# quark_foc_driver.net
KiCad netlist of a schematic drawn in Altium Designer
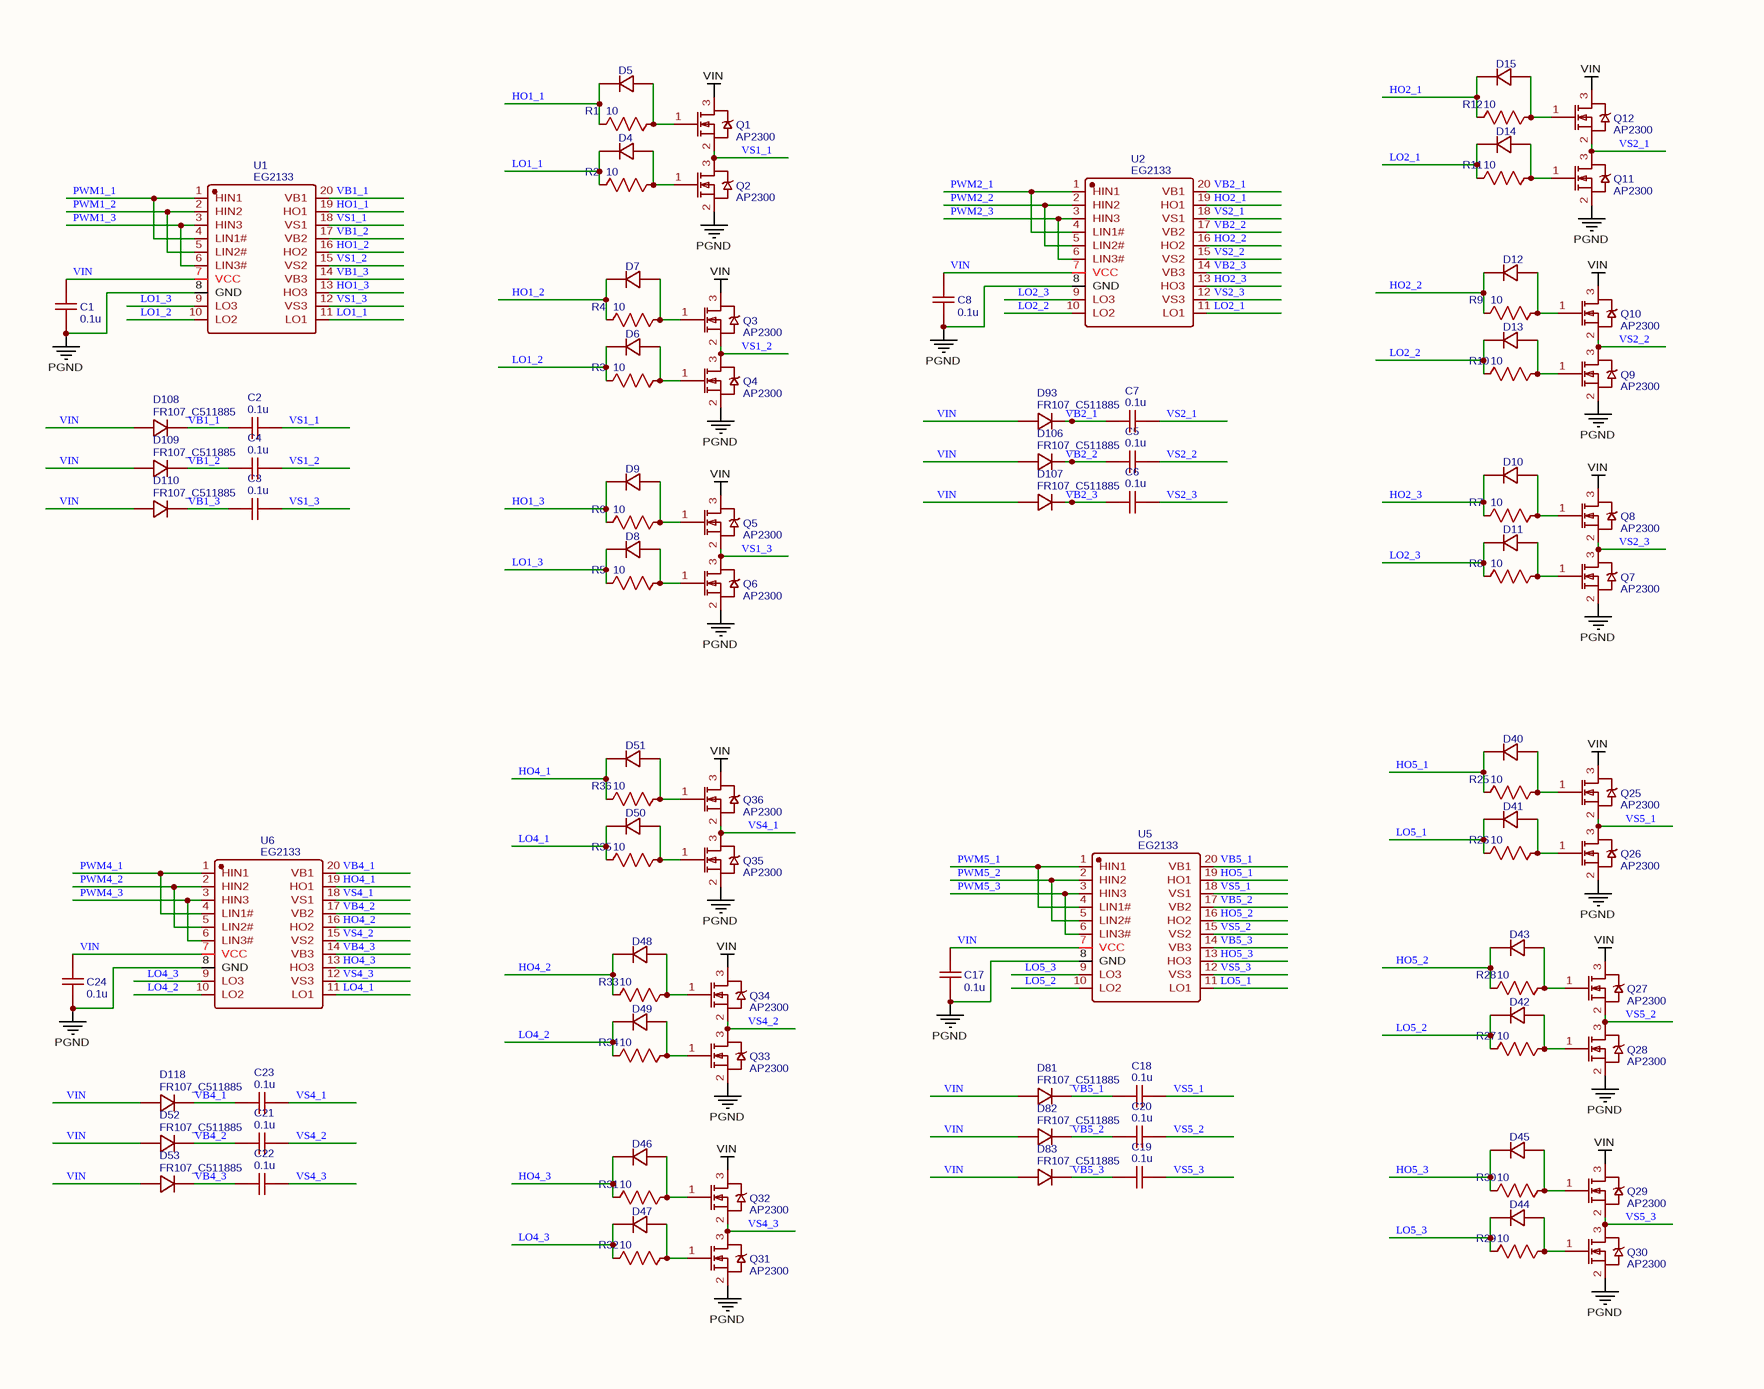
[diagram p0: quark_foc_driver.schdoc, top left]
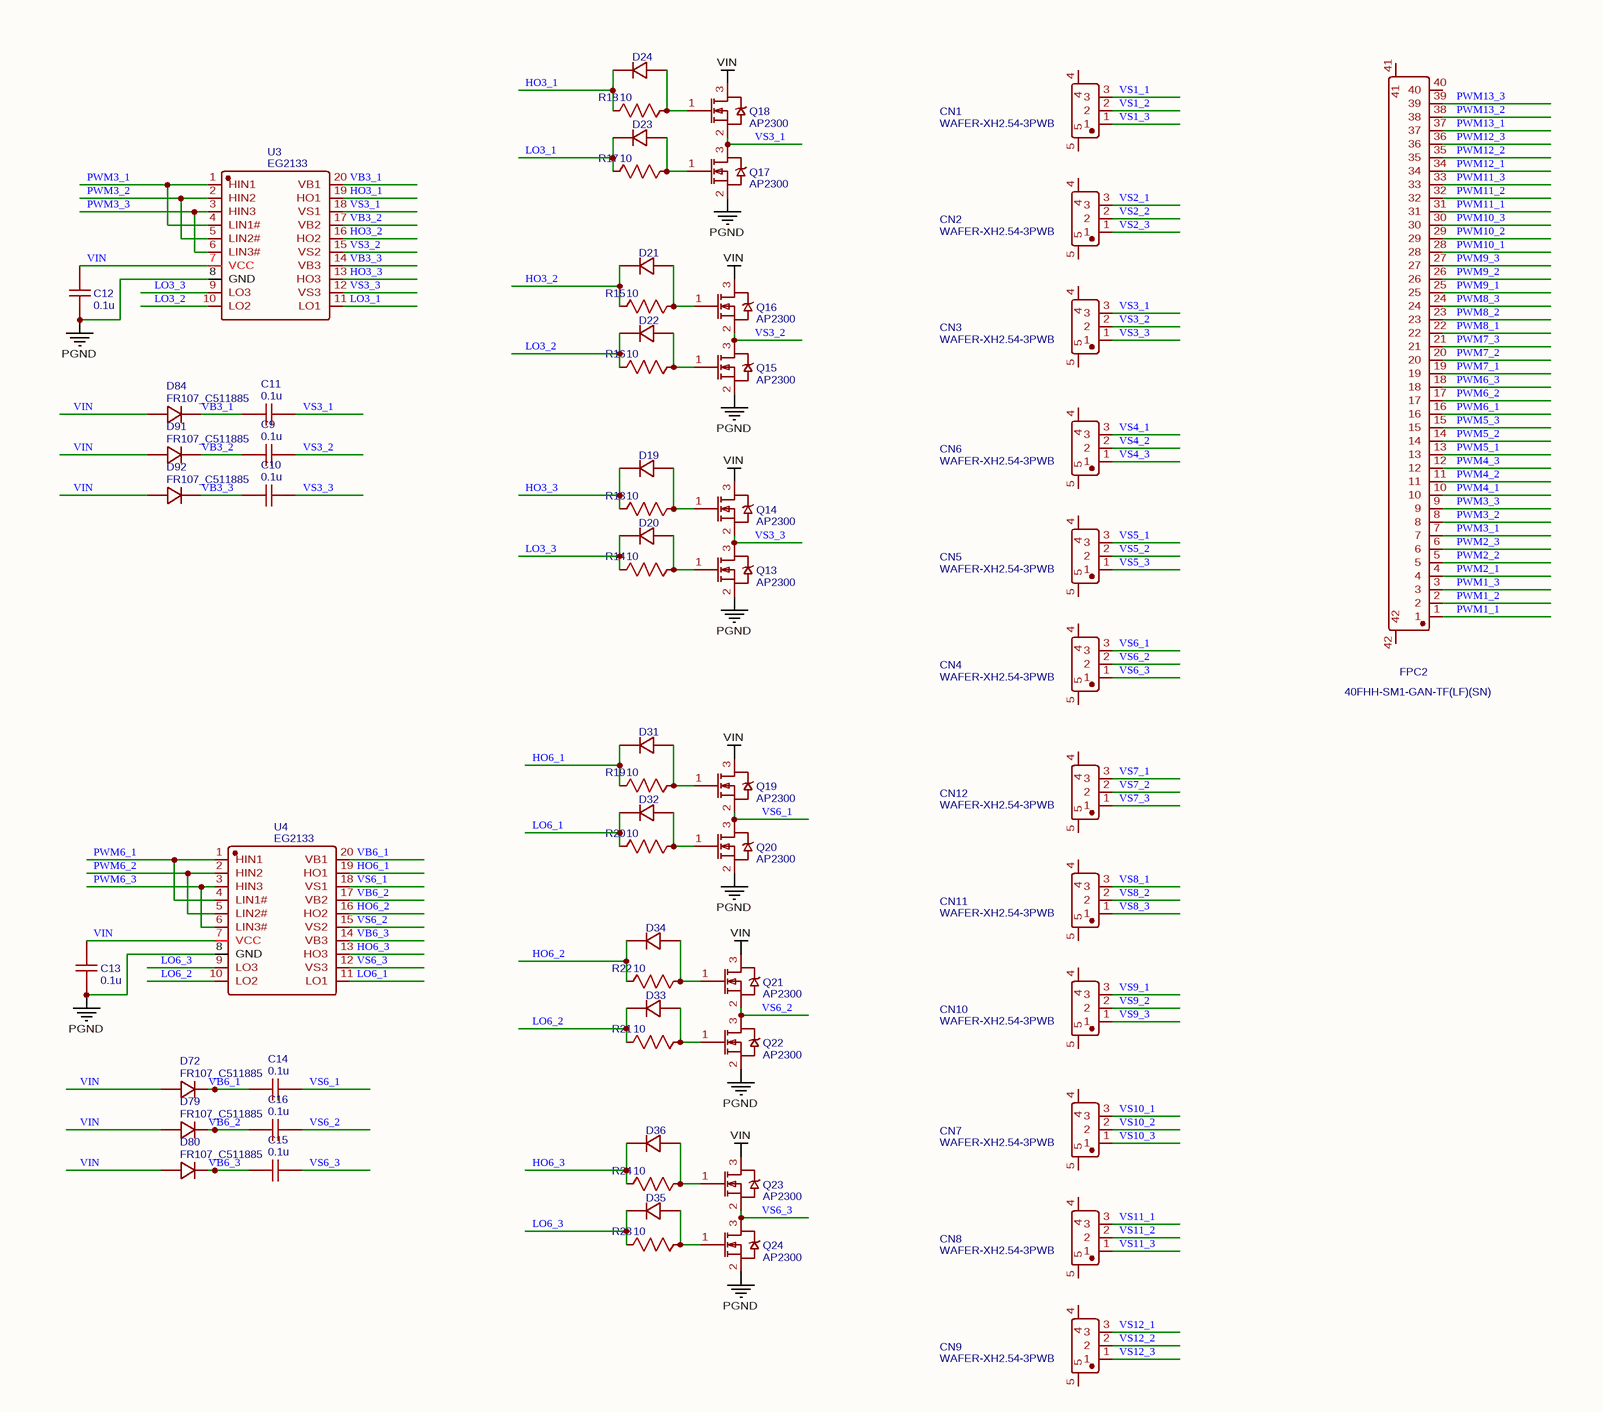
[diagram p1: quark_foc_driver.schdoc, top right]
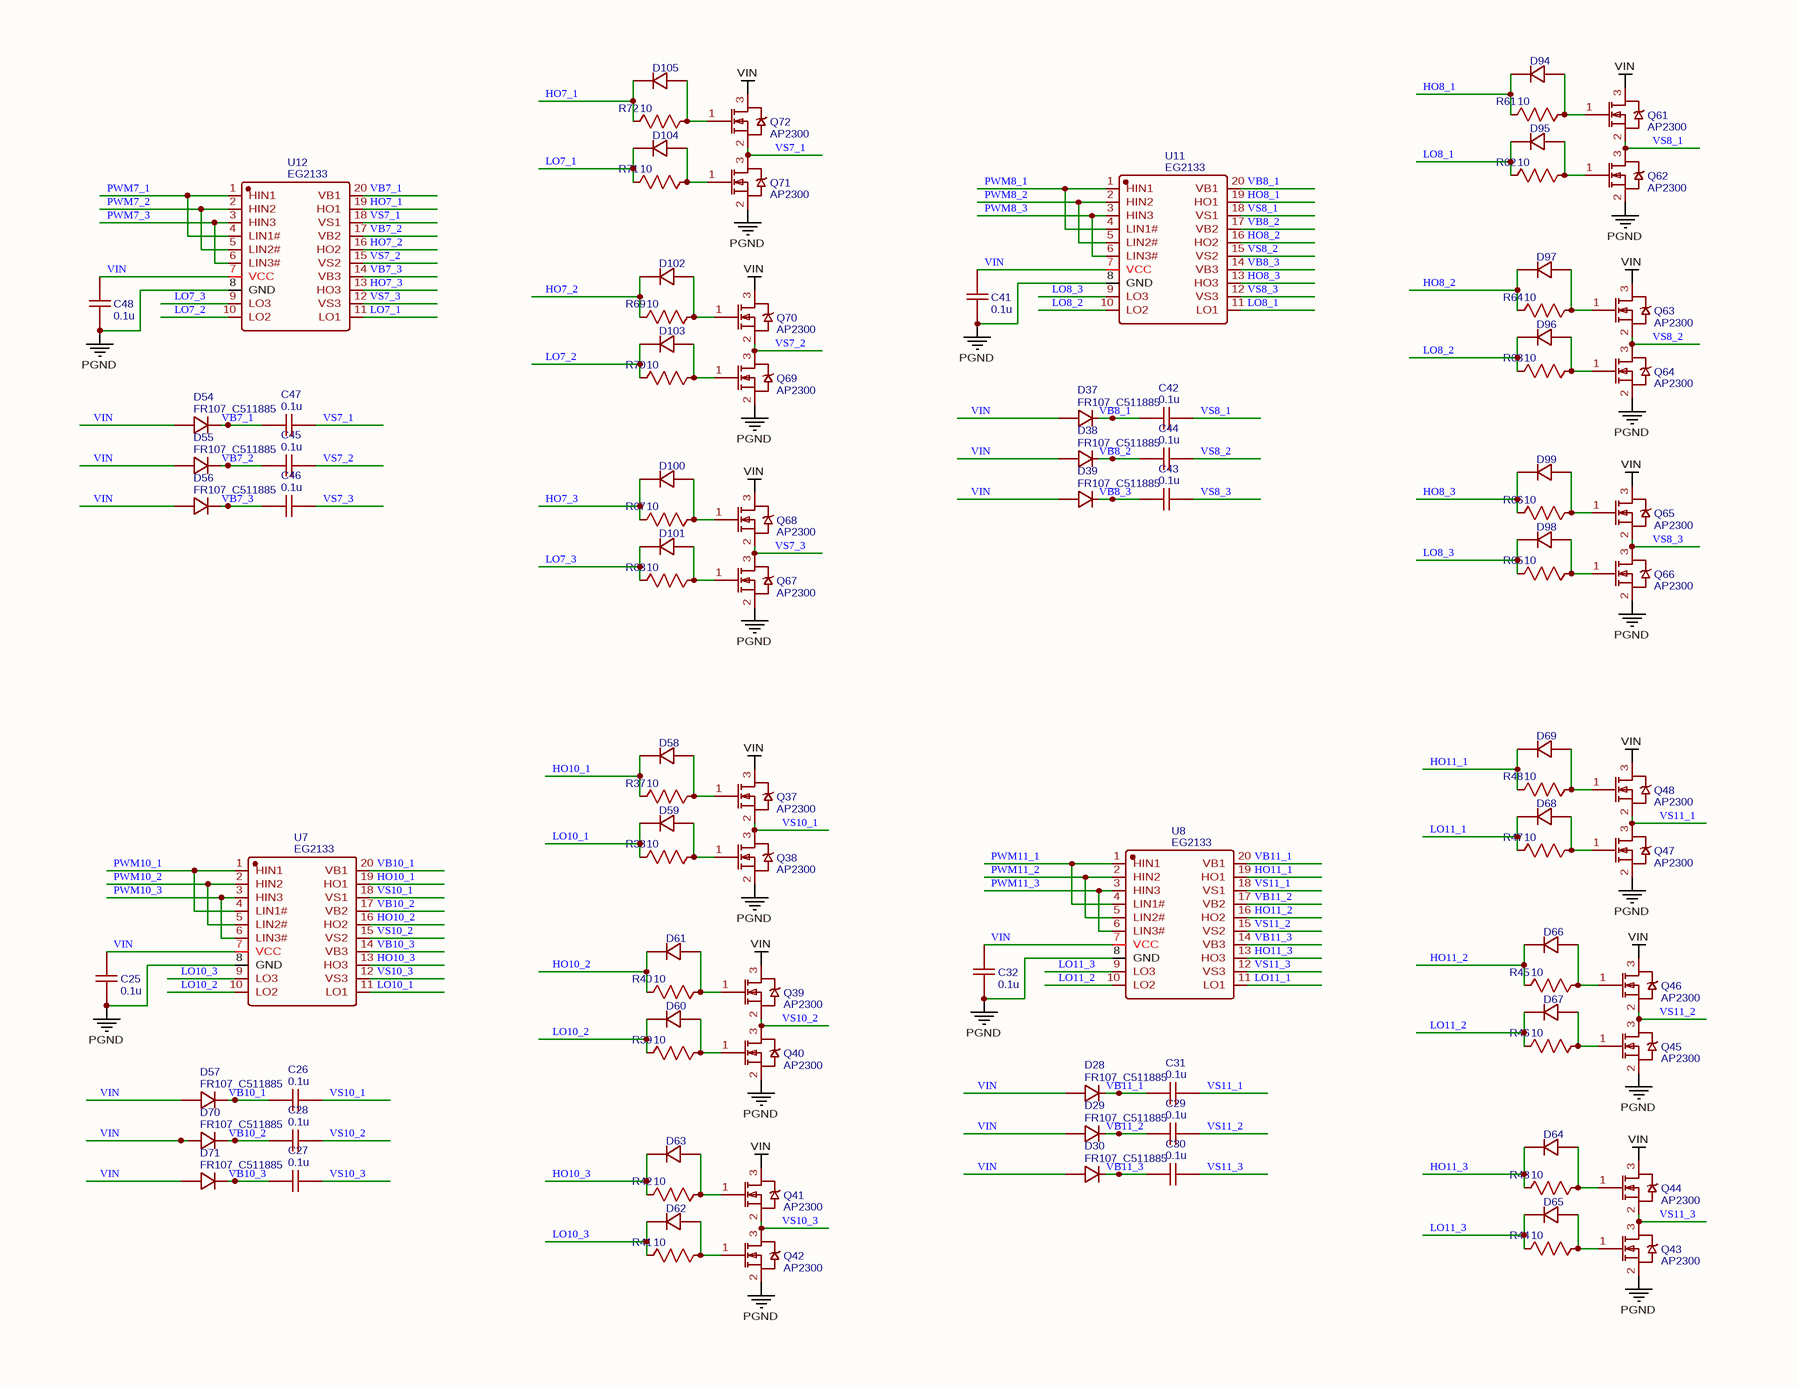
[diagram p2: quark_foc_driver.schdoc, bottom left]
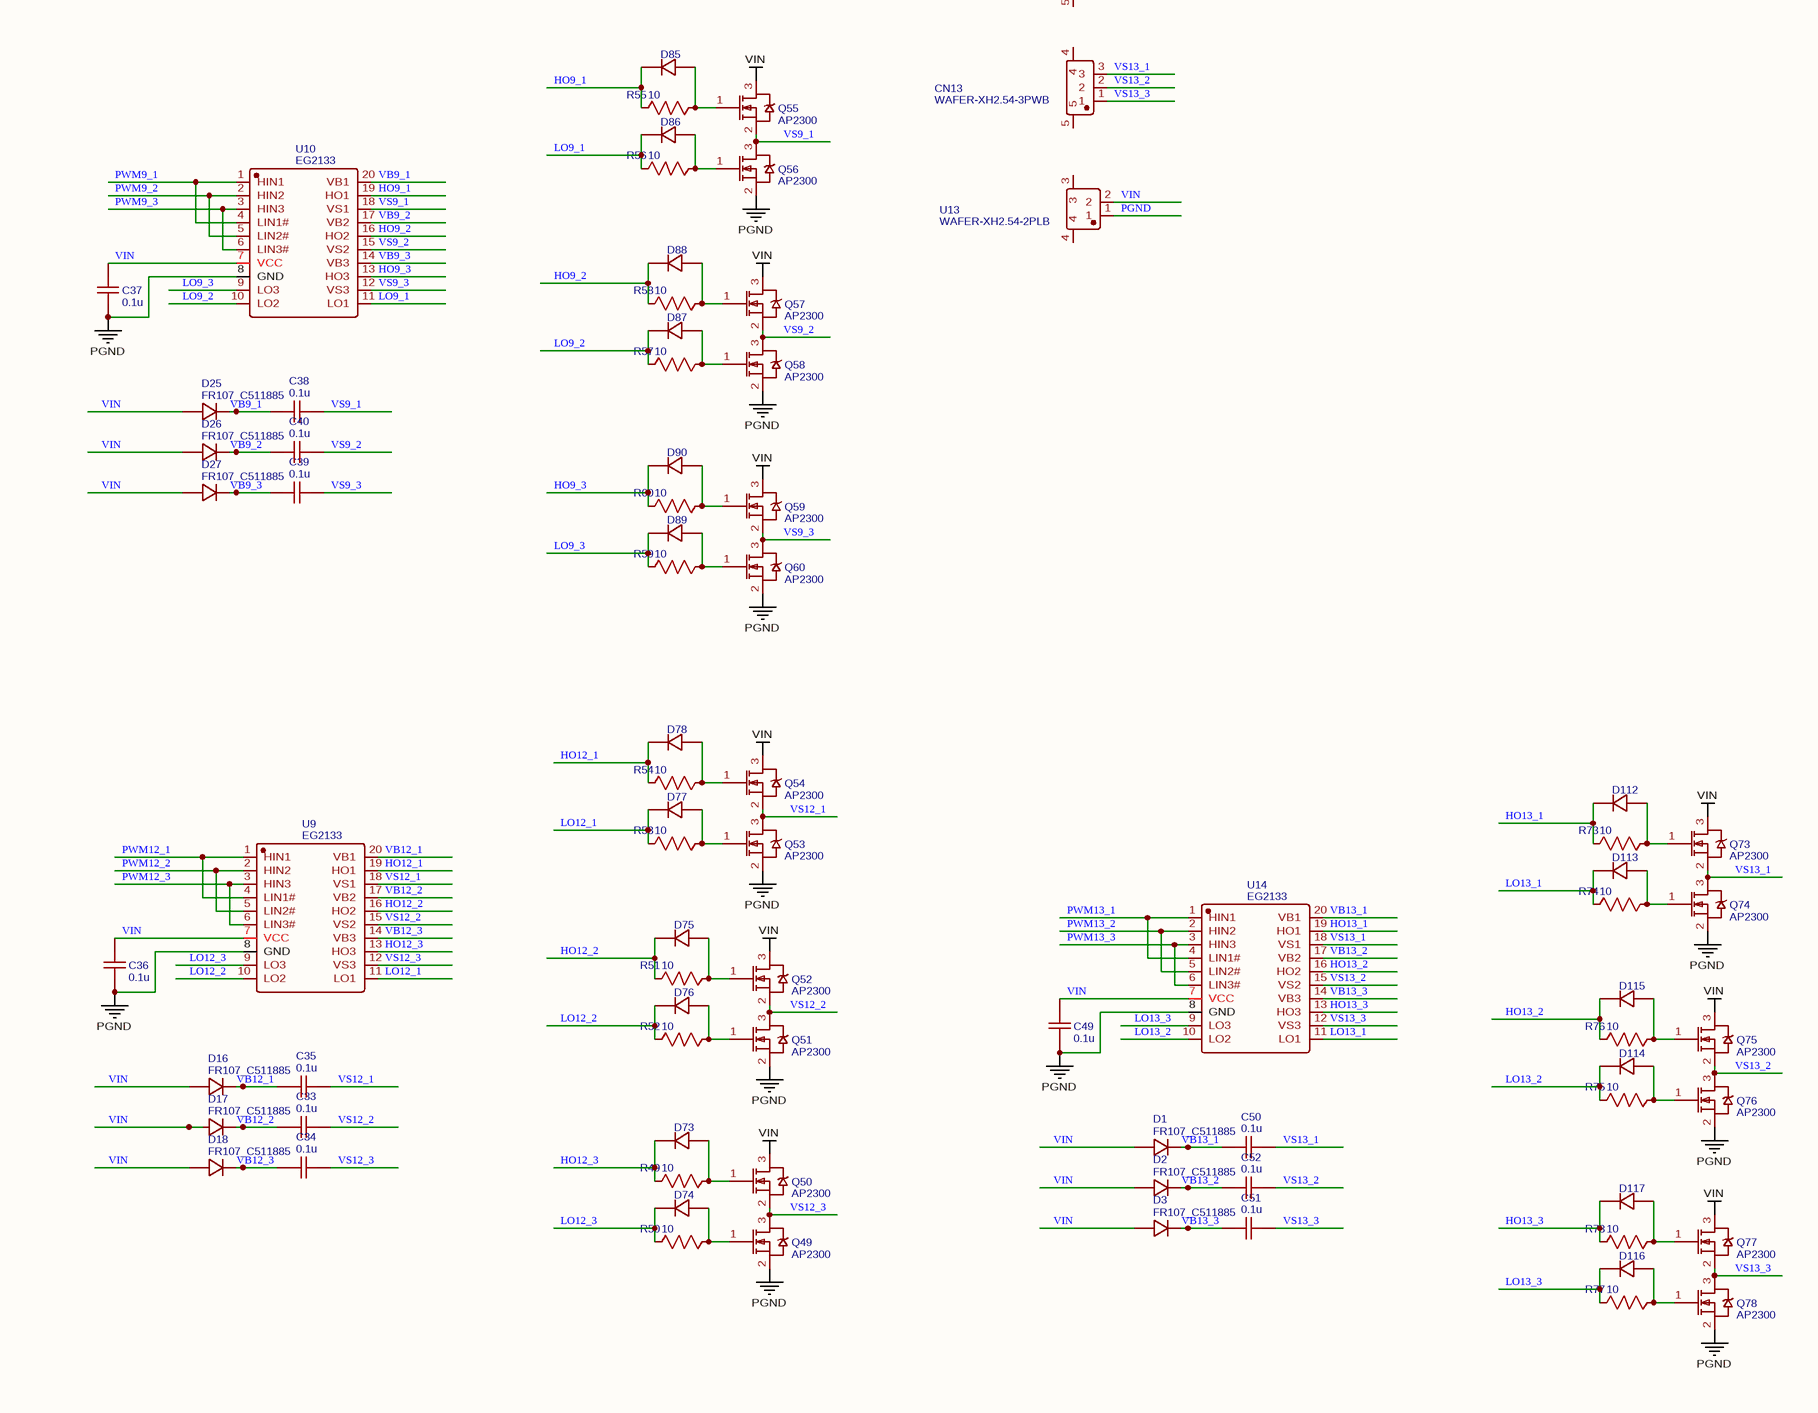
[diagram p3: quark_foc_driver.schdoc, bottom right]

(export (version "E")
  (design (tool "Eeschema 10.0.6"))
  (components
    (comp (ref "C1")
      (value "0.1u")
      (footprint "C0603")
      (fields (field (name "CONTRIBUTOR") "LCEDA_Lib"))
      (libsource (lib "altium-import") (part "root_1_0.1u_"))
    )
    (comp (ref "C2")
      (value "0.1u")
      (footprint "C0603")
      (fields (field (name "CONTRIBUTOR") "LCEDA_Lib"))
      (libsource (lib "altium-import") (part "root_0_0.1u_"))
    )
    (comp (ref "C3")
      (value "0.1u")
      (footprint "C0603")
      (fields (field (name "CONTRIBUTOR") "LCEDA_Lib"))
      (libsource (lib "altium-import") (part "root_0_0.1u_"))
    )
    (comp (ref "C4")
      (value "0.1u")
      (footprint "C0603")
      (fields (field (name "CONTRIBUTOR") "LCEDA_Lib"))
      (libsource (lib "altium-import") (part "root_2_0.1u_"))
    )
    (comp (ref "C5")
      (value "0.1u")
      (footprint "C0603")
      (fields (field (name "CONTRIBUTOR") "LCEDA_Lib"))
      (libsource (lib "altium-import") (part "root_2_0.1u_"))
    )
    (comp (ref "C6")
      (value "0.1u")
      (footprint "C0603")
      (fields (field (name "CONTRIBUTOR") "LCEDA_Lib"))
      (libsource (lib "altium-import") (part "root_0_0.1u_"))
    )
    (comp (ref "C7")
      (value "0.1u")
      (footprint "C0603")
      (fields (field (name "CONTRIBUTOR") "LCEDA_Lib"))
      (libsource (lib "altium-import") (part "root_0_0.1u_"))
    )
    (comp (ref "C8")
      (value "0.1u")
      (footprint "C0603")
      (fields (field (name "CONTRIBUTOR") "LCEDA_Lib"))
      (libsource (lib "altium-import") (part "root_1_0.1u_"))
    )
    (comp (ref "C9")
      (value "0.1u")
      (footprint "C0603")
      (fields (field (name "CONTRIBUTOR") "LCEDA_Lib"))
      (libsource (lib "altium-import") (part "root_2_0.1u_"))
    )
    (comp (ref "C10")
      (value "0.1u")
      (footprint "C0603")
      (fields (field (name "CONTRIBUTOR") "LCEDA_Lib"))
      (libsource (lib "altium-import") (part "root_0_0.1u_"))
    )
    (comp (ref "C11")
      (value "0.1u")
      (footprint "C0603")
      (fields (field (name "CONTRIBUTOR") "LCEDA_Lib"))
      (libsource (lib "altium-import") (part "root_0_0.1u_"))
    )
    (comp (ref "C12")
      (value "0.1u")
      (footprint "C0603")
      (fields (field (name "CONTRIBUTOR") "LCEDA_Lib"))
      (libsource (lib "altium-import") (part "root_1_0.1u_"))
    )
    (comp (ref "C13")
      (value "0.1u")
      (footprint "C0603")
      (fields (field (name "CONTRIBUTOR") "LCEDA_Lib"))
      (libsource (lib "altium-import") (part "root_1_0.1u_"))
    )
    (comp (ref "C14")
      (value "0.1u")
      (footprint "C0603")
      (fields (field (name "CONTRIBUTOR") "LCEDA_Lib"))
      (libsource (lib "altium-import") (part "root_0_0.1u_"))
    )
    (comp (ref "C15")
      (value "0.1u")
      (footprint "C0603")
      (fields (field (name "CONTRIBUTOR") "LCEDA_Lib"))
      (libsource (lib "altium-import") (part "root_0_0.1u_"))
    )
    (comp (ref "C16")
      (value "0.1u")
      (footprint "C0603")
      (fields (field (name "CONTRIBUTOR") "LCEDA_Lib"))
      (libsource (lib "altium-import") (part "root_2_0.1u_"))
    )
    (comp (ref "C17")
      (value "0.1u")
      (footprint "C0603")
      (fields (field (name "CONTRIBUTOR") "LCEDA_Lib"))
      (libsource (lib "altium-import") (part "root_1_0.1u_"))
    )
    (comp (ref "C18")
      (value "0.1u")
      (footprint "C0603")
      (fields (field (name "CONTRIBUTOR") "LCEDA_Lib"))
      (libsource (lib "altium-import") (part "root_0_0.1u_"))
    )
    (comp (ref "C19")
      (value "0.1u")
      (footprint "C0603")
      (fields (field (name "CONTRIBUTOR") "LCEDA_Lib"))
      (libsource (lib "altium-import") (part "root_0_0.1u_"))
    )
    (comp (ref "C20")
      (value "0.1u")
      (footprint "C0603")
      (fields (field (name "CONTRIBUTOR") "LCEDA_Lib"))
      (libsource (lib "altium-import") (part "root_2_0.1u_"))
    )
    (comp (ref "C21")
      (value "0.1u")
      (footprint "C0603")
      (fields (field (name "CONTRIBUTOR") "LCEDA_Lib"))
      (libsource (lib "altium-import") (part "root_2_0.1u_"))
    )
    (comp (ref "C22")
      (value "0.1u")
      (footprint "C0603")
      (fields (field (name "CONTRIBUTOR") "LCEDA_Lib"))
      (libsource (lib "altium-import") (part "root_0_0.1u_"))
    )
    (comp (ref "C23")
      (value "0.1u")
      (footprint "C0603")
      (fields (field (name "CONTRIBUTOR") "LCEDA_Lib"))
      (libsource (lib "altium-import") (part "root_0_0.1u_"))
    )
    (comp (ref "C24")
      (value "0.1u")
      (footprint "C0603")
      (fields (field (name "CONTRIBUTOR") "LCEDA_Lib"))
      (libsource (lib "altium-import") (part "root_1_0.1u_"))
    )
    (comp (ref "C25")
      (value "0.1u")
      (footprint "C0603")
      (fields (field (name "CONTRIBUTOR") "LCEDA_Lib"))
      (libsource (lib "altium-import") (part "root_1_0.1u_"))
    )
    (comp (ref "C26")
      (value "0.1u")
      (footprint "C0603")
      (fields (field (name "CONTRIBUTOR") "LCEDA_Lib"))
      (libsource (lib "altium-import") (part "root_0_0.1u_"))
    )
    (comp (ref "C27")
      (value "0.1u")
      (footprint "C0603")
      (fields (field (name "CONTRIBUTOR") "LCEDA_Lib"))
      (libsource (lib "altium-import") (part "root_0_0.1u_"))
    )
    (comp (ref "C28")
      (value "0.1u")
      (footprint "C0603")
      (fields (field (name "CONTRIBUTOR") "LCEDA_Lib"))
      (libsource (lib "altium-import") (part "root_2_0.1u_"))
    )
    (comp (ref "C29")
      (value "0.1u")
      (footprint "C0603")
      (fields (field (name "CONTRIBUTOR") "LCEDA_Lib"))
      (libsource (lib "altium-import") (part "root_2_0.1u_"))
    )
    (comp (ref "C30")
      (value "0.1u")
      (footprint "C0603")
      (fields (field (name "CONTRIBUTOR") "LCEDA_Lib"))
      (libsource (lib "altium-import") (part "root_0_0.1u_"))
    )
    (comp (ref "C31")
      (value "0.1u")
      (footprint "C0603")
      (fields (field (name "CONTRIBUTOR") "LCEDA_Lib"))
      (libsource (lib "altium-import") (part "root_0_0.1u_"))
    )
    (comp (ref "C32")
      (value "0.1u")
      (footprint "C0603")
      (fields (field (name "CONTRIBUTOR") "LCEDA_Lib"))
      (libsource (lib "altium-import") (part "root_1_0.1u_"))
    )
    (comp (ref "C33")
      (value "0.1u")
      (footprint "C0603")
      (fields (field (name "CONTRIBUTOR") "LCEDA_Lib"))
      (libsource (lib "altium-import") (part "root_2_0.1u_"))
    )
    (comp (ref "C34")
      (value "0.1u")
      (footprint "C0603")
      (fields (field (name "CONTRIBUTOR") "LCEDA_Lib"))
      (libsource (lib "altium-import") (part "root_0_0.1u_"))
    )
    (comp (ref "C35")
      (value "0.1u")
      (footprint "C0603")
      (fields (field (name "CONTRIBUTOR") "LCEDA_Lib"))
      (libsource (lib "altium-import") (part "root_0_0.1u_"))
    )
    (comp (ref "C36")
      (value "0.1u")
      (footprint "C0603")
      (fields (field (name "CONTRIBUTOR") "LCEDA_Lib"))
      (libsource (lib "altium-import") (part "root_1_0.1u_"))
    )
    (comp (ref "C37")
      (value "0.1u")
      (footprint "C0603")
      (fields (field (name "CONTRIBUTOR") "LCEDA_Lib"))
      (libsource (lib "altium-import") (part "root_1_0.1u_"))
    )
    (comp (ref "C38")
      (value "0.1u")
      (footprint "C0603")
      (fields (field (name "CONTRIBUTOR") "LCEDA_Lib"))
      (libsource (lib "altium-import") (part "root_0_0.1u_"))
    )
    (comp (ref "C39")
      (value "0.1u")
      (footprint "C0603")
      (fields (field (name "CONTRIBUTOR") "LCEDA_Lib"))
      (libsource (lib "altium-import") (part "root_0_0.1u_"))
    )
    (comp (ref "C40")
      (value "0.1u")
      (footprint "C0603")
      (fields (field (name "CONTRIBUTOR") "LCEDA_Lib"))
      (libsource (lib "altium-import") (part "root_2_0.1u_"))
    )
    (comp (ref "C41")
      (value "0.1u")
      (footprint "C0603")
      (fields (field (name "CONTRIBUTOR") "LCEDA_Lib"))
      (libsource (lib "altium-import") (part "root_1_0.1u_"))
    )
    (comp (ref "C42")
      (value "0.1u")
      (footprint "C0603")
      (fields (field (name "CONTRIBUTOR") "LCEDA_Lib"))
      (libsource (lib "altium-import") (part "root_0_0.1u_"))
    )
    (comp (ref "C43")
      (value "0.1u")
      (footprint "C0603")
      (fields (field (name "CONTRIBUTOR") "LCEDA_Lib"))
      (libsource (lib "altium-import") (part "root_0_0.1u_"))
    )
    (comp (ref "C44")
      (value "0.1u")
      (footprint "C0603")
      (fields (field (name "CONTRIBUTOR") "LCEDA_Lib"))
      (libsource (lib "altium-import") (part "root_2_0.1u_"))
    )
    (comp (ref "C45")
      (value "0.1u")
      (footprint "C0603")
      (fields (field (name "CONTRIBUTOR") "LCEDA_Lib"))
      (libsource (lib "altium-import") (part "root_2_0.1u_"))
    )
    (comp (ref "C46")
      (value "0.1u")
      (footprint "C0603")
      (fields (field (name "CONTRIBUTOR") "LCEDA_Lib"))
      (libsource (lib "altium-import") (part "root_0_0.1u_"))
    )
    (comp (ref "C47")
      (value "0.1u")
      (footprint "C0603")
      (fields (field (name "CONTRIBUTOR") "LCEDA_Lib"))
      (libsource (lib "altium-import") (part "root_0_0.1u_"))
    )
    (comp (ref "C48")
      (value "0.1u")
      (footprint "C0603")
      (fields (field (name "CONTRIBUTOR") "LCEDA_Lib"))
      (libsource (lib "altium-import") (part "root_1_0.1u_"))
    )
    (comp (ref "C49")
      (value "0.1u")
      (footprint "C0603")
      (fields (field (name "CONTRIBUTOR") "LCEDA_Lib"))
      (libsource (lib "altium-import") (part "root_1_0.1u_"))
    )
    (comp (ref "C50")
      (value "0.1u")
      (footprint "C0603")
      (fields (field (name "CONTRIBUTOR") "LCEDA_Lib"))
      (libsource (lib "altium-import") (part "root_0_0.1u_"))
    )
    (comp (ref "C51")
      (value "0.1u")
      (footprint "C0603")
      (fields (field (name "CONTRIBUTOR") "LCEDA_Lib"))
      (libsource (lib "altium-import") (part "root_0_0.1u_"))
    )
    (comp (ref "C52")
      (value "0.1u")
      (footprint "C0603")
      (fields (field (name "CONTRIBUTOR") "LCEDA_Lib"))
      (libsource (lib "altium-import") (part "root_2_0.1u_"))
    )
    (comp (ref "CN1")
      (value "WAFER-XH2.54-3PWB")
      (footprint "CONN-SMD_3P-P2.50_XUNPU_WAFER-XH2.54-3PWB")
      (fields (field (name "BOM_SUPPLIER PART") "C3029477") (field (name "CONTRIBUTOR") "lcsc"))
      (libsource (lib "altium-import") (part "root_2_WAFER-XH2.54-3PWB_"))
    )
    (comp (ref "CN2")
      (value "WAFER-XH2.54-3PWB")
      (footprint "CONN-SMD_3P-P2.50_XUNPU_WAFER-XH2.54-3PWB")
      (fields (field (name "BOM_SUPPLIER PART") "C3029477") (field (name "CONTRIBUTOR") "lcsc"))
      (libsource (lib "altium-import") (part "root_2_WAFER-XH2.54-3PWB_"))
    )
    (comp (ref "CN3")
      (value "WAFER-XH2.54-3PWB")
      (footprint "CONN-SMD_3P-P2.50_XUNPU_WAFER-XH2.54-3PWB")
      (fields (field (name "BOM_SUPPLIER PART") "C3029477") (field (name "CONTRIBUTOR") "lcsc"))
      (libsource (lib "altium-import") (part "root_2_WAFER-XH2.54-3PWB_"))
    )
    (comp (ref "CN4")
      (value "WAFER-XH2.54-3PWB")
      (footprint "CONN-SMD_3P-P2.50_XUNPU_WAFER-XH2.54-3PWB")
      (fields (field (name "BOM_SUPPLIER PART") "C3029477") (field (name "CONTRIBUTOR") "lcsc"))
      (libsource (lib "altium-import") (part "root_2_WAFER-XH2.54-3PWB_"))
    )
    (comp (ref "CN5")
      (value "WAFER-XH2.54-3PWB")
      (footprint "CONN-SMD_3P-P2.50_XUNPU_WAFER-XH2.54-3PWB")
      (fields (field (name "BOM_SUPPLIER PART") "C3029477") (field (name "CONTRIBUTOR") "lcsc"))
      (libsource (lib "altium-import") (part "root_2_WAFER-XH2.54-3PWB_"))
    )
    (comp (ref "CN6")
      (value "WAFER-XH2.54-3PWB")
      (footprint "CONN-SMD_3P-P2.50_XUNPU_WAFER-XH2.54-3PWB")
      (fields (field (name "BOM_SUPPLIER PART") "C3029477") (field (name "CONTRIBUTOR") "lcsc"))
      (libsource (lib "altium-import") (part "root_2_WAFER-XH2.54-3PWB_"))
    )
    (comp (ref "CN7")
      (value "WAFER-XH2.54-3PWB")
      (footprint "CONN-SMD_3P-P2.50_XUNPU_WAFER-XH2.54-3PWB")
      (fields (field (name "BOM_SUPPLIER PART") "C3029477") (field (name "CONTRIBUTOR") "lcsc"))
      (libsource (lib "altium-import") (part "root_2_WAFER-XH2.54-3PWB_"))
    )
    (comp (ref "CN8")
      (value "WAFER-XH2.54-3PWB")
      (footprint "CONN-SMD_3P-P2.50_XUNPU_WAFER-XH2.54-3PWB")
      (fields (field (name "BOM_SUPPLIER PART") "C3029477") (field (name "CONTRIBUTOR") "lcsc"))
      (libsource (lib "altium-import") (part "root_2_WAFER-XH2.54-3PWB_"))
    )
    (comp (ref "CN9")
      (value "WAFER-XH2.54-3PWB")
      (footprint "CONN-SMD_3P-P2.50_XUNPU_WAFER-XH2.54-3PWB")
      (fields (field (name "BOM_SUPPLIER PART") "C3029477") (field (name "CONTRIBUTOR") "lcsc"))
      (libsource (lib "altium-import") (part "root_2_WAFER-XH2.54-3PWB_"))
    )
    (comp (ref "CN10")
      (value "WAFER-XH2.54-3PWB")
      (footprint "CONN-SMD_3P-P2.50_XUNPU_WAFER-XH2.54-3PWB")
      (fields (field (name "BOM_SUPPLIER PART") "C3029477") (field (name "CONTRIBUTOR") "lcsc"))
      (libsource (lib "altium-import") (part "root_2_WAFER-XH2.54-3PWB_"))
    )
    (comp (ref "CN11")
      (value "WAFER-XH2.54-3PWB")
      (footprint "CONN-SMD_3P-P2.50_XUNPU_WAFER-XH2.54-3PWB")
      (fields (field (name "BOM_SUPPLIER PART") "C3029477") (field (name "CONTRIBUTOR") "lcsc"))
      (libsource (lib "altium-import") (part "root_2_WAFER-XH2.54-3PWB_"))
    )
    (comp (ref "CN12")
      (value "WAFER-XH2.54-3PWB")
      (footprint "CONN-SMD_3P-P2.50_XUNPU_WAFER-XH2.54-3PWB")
      (fields (field (name "BOM_SUPPLIER PART") "C3029477") (field (name "CONTRIBUTOR") "lcsc"))
      (libsource (lib "altium-import") (part "root_2_WAFER-XH2.54-3PWB_"))
    )
    (comp (ref "CN13")
      (value "WAFER-XH2.54-3PWB")
      (footprint "CONN-SMD_3P-P2.50_XUNPU_WAFER-XH2.54-3PWB")
      (fields (field (name "BOM_SUPPLIER PART") "C3029477") (field (name "CONTRIBUTOR") "lcsc"))
      (libsource (lib "altium-import") (part "root_2_WAFER-XH2.54-3PWB_"))
    )
    (comp (ref "D1")
      (value "FR107_C511885")
      (footprint "SOD-123_L2.8-W1.8-LS3.7-RD")
      (fields
        (field (name "BOM_SUPPLIER PART") "C511885")
        (field (name "BOM_MANUFACTURER PART") "FR107")
        (field (name "CONTRIBUTOR") "LCSC")
      )
      (libsource (lib "altium-import") (part "root_2_FR107_C511885_"))
    )
    (comp (ref "D2")
      (value "FR107_C511885")
      (footprint "SOD-123_L2.8-W1.8-LS3.7-RD")
      (fields
        (field (name "BOM_SUPPLIER PART") "C511885")
        (field (name "BOM_MANUFACTURER PART") "FR107")
        (field (name "CONTRIBUTOR") "LCSC")
      )
      (libsource (lib "altium-import") (part "root_2_FR107_C511885_"))
    )
    (comp (ref "D3")
      (value "FR107_C511885")
      (footprint "SOD-123_L2.8-W1.8-LS3.7-RD")
      (fields
        (field (name "BOM_SUPPLIER PART") "C511885")
        (field (name "BOM_MANUFACTURER PART") "FR107")
        (field (name "CONTRIBUTOR") "LCSC")
      )
      (libsource (lib "altium-import") (part "root_2_FR107_C511885_"))
    )
    (comp (ref "D4")
      (value "1N4148W_C176288")
      (footprint "SOD-123_L2.8-W1.8-LS3.7-RD")
      (fields
        (field (name "BOM_SUPPLIER PART") "C176288")
        (field (name "BOM_MANUFACTURER PART") "1N4148W")
        (field (name "CONTRIBUTOR") "LCSC")
      )
      (libsource (lib "altium-import") (part "root_0_1N4148W_C176288_"))
    )
    (comp (ref "D5")
      (value "1N4148W_C176288")
      (footprint "SOD-123_L2.8-W1.8-LS3.7-RD")
      (fields
        (field (name "BOM_SUPPLIER PART") "C176288")
        (field (name "BOM_MANUFACTURER PART") "1N4148W")
        (field (name "CONTRIBUTOR") "LCSC")
      )
      (libsource (lib "altium-import") (part "root_0_1N4148W_C176288_"))
    )
    (comp (ref "D6")
      (value "1N4148W_C176288")
      (footprint "SOD-123_L2.8-W1.8-LS3.7-RD")
      (fields
        (field (name "BOM_SUPPLIER PART") "C176288")
        (field (name "BOM_MANUFACTURER PART") "1N4148W")
        (field (name "CONTRIBUTOR") "LCSC")
      )
      (libsource (lib "altium-import") (part "root_0_1N4148W_C176288_"))
    )
    (comp (ref "D7")
      (value "1N4148W_C176288")
      (footprint "SOD-123_L2.8-W1.8-LS3.7-RD")
      (fields
        (field (name "BOM_SUPPLIER PART") "C176288")
        (field (name "BOM_MANUFACTURER PART") "1N4148W")
        (field (name "CONTRIBUTOR") "LCSC")
      )
      (libsource (lib "altium-import") (part "root_0_1N4148W_C176288_"))
    )
    (comp (ref "D8")
      (value "1N4148W_C176288")
      (footprint "SOD-123_L2.8-W1.8-LS3.7-RD")
      (fields
        (field (name "BOM_SUPPLIER PART") "C176288")
        (field (name "BOM_MANUFACTURER PART") "1N4148W")
        (field (name "CONTRIBUTOR") "LCSC")
      )
      (libsource (lib "altium-import") (part "root_0_1N4148W_C176288_"))
    )
    (comp (ref "D9")
      (value "1N4148W_C176288")
      (footprint "SOD-123_L2.8-W1.8-LS3.7-RD")
      (fields
        (field (name "BOM_SUPPLIER PART") "C176288")
        (field (name "BOM_MANUFACTURER PART") "1N4148W")
        (field (name "CONTRIBUTOR") "LCSC")
      )
      (libsource (lib "altium-import") (part "root_0_1N4148W_C176288_"))
    )
    (comp (ref "D10")
      (value "1N4148W_C176288")
      (footprint "SOD-123_L2.8-W1.8-LS3.7-RD")
      (fields
        (field (name "BOM_SUPPLIER PART") "C176288")
        (field (name "BOM_MANUFACTURER PART") "1N4148W")
        (field (name "CONTRIBUTOR") "LCSC")
      )
      (libsource (lib "altium-import") (part "root_0_1N4148W_C176288_"))
    )
    (comp (ref "D11")
      (value "1N4148W_C176288")
      (footprint "SOD-123_L2.8-W1.8-LS3.7-RD")
      (fields
        (field (name "BOM_SUPPLIER PART") "C176288")
        (field (name "BOM_MANUFACTURER PART") "1N4148W")
        (field (name "CONTRIBUTOR") "LCSC")
      )
      (libsource (lib "altium-import") (part "root_0_1N4148W_C176288_"))
    )
    (comp (ref "D12")
      (value "1N4148W_C176288")
      (footprint "SOD-123_L2.8-W1.8-LS3.7-RD")
      (fields
        (field (name "BOM_SUPPLIER PART") "C176288")
        (field (name "BOM_MANUFACTURER PART") "1N4148W")
        (field (name "CONTRIBUTOR") "LCSC")
      )
      (libsource (lib "altium-import") (part "root_0_1N4148W_C176288_"))
    )
    (comp (ref "D13")
      (value "1N4148W_C176288")
      (footprint "SOD-123_L2.8-W1.8-LS3.7-RD")
      (fields
        (field (name "BOM_SUPPLIER PART") "C176288")
        (field (name "BOM_MANUFACTURER PART") "1N4148W")
        (field (name "CONTRIBUTOR") "LCSC")
      )
      (libsource (lib "altium-import") (part "root_0_1N4148W_C176288_"))
    )
    (comp (ref "D14")
      (value "1N4148W_C176288")
      (footprint "SOD-123_L2.8-W1.8-LS3.7-RD")
      (fields
        (field (name "BOM_SUPPLIER PART") "C176288")
        (field (name "BOM_MANUFACTURER PART") "1N4148W")
        (field (name "CONTRIBUTOR") "LCSC")
      )
      (libsource (lib "altium-import") (part "root_0_1N4148W_C176288_"))
    )
    (comp (ref "D15")
      (value "1N4148W_C176288")
      (footprint "SOD-123_L2.8-W1.8-LS3.7-RD")
      (fields
        (field (name "BOM_SUPPLIER PART") "C176288")
        (field (name "BOM_MANUFACTURER PART") "1N4148W")
        (field (name "CONTRIBUTOR") "LCSC")
      )
      (libsource (lib "altium-import") (part "root_0_1N4148W_C176288_"))
    )
    (comp (ref "D16")
      (value "FR107_C511885")
      (footprint "SOD-123_L2.8-W1.8-LS3.7-RD")
      (fields
        (field (name "BOM_SUPPLIER PART") "C511885")
        (field (name "BOM_MANUFACTURER PART") "FR107")
        (field (name "CONTRIBUTOR") "LCSC")
      )
      (libsource (lib "altium-import") (part "root_2_FR107_C511885_"))
    )
    (comp (ref "D17")
      (value "FR107_C511885")
      (footprint "SOD-123_L2.8-W1.8-LS3.7-RD")
      (fields
        (field (name "BOM_SUPPLIER PART") "C511885")
        (field (name "BOM_MANUFACTURER PART") "FR107")
        (field (name "CONTRIBUTOR") "LCSC")
      )
      (libsource (lib "altium-import") (part "root_2_FR107_C511885_"))
    )
    (comp (ref "D18")
      (value "FR107_C511885")
      (footprint "SOD-123_L2.8-W1.8-LS3.7-RD")
      (fields
        (field (name "BOM_SUPPLIER PART") "C511885")
        (field (name "BOM_MANUFACTURER PART") "FR107")
        (field (name "CONTRIBUTOR") "LCSC")
      )
      (libsource (lib "altium-import") (part "root_2_FR107_C511885_"))
    )
    (comp (ref "D19")
      (value "1N4148W_C176288")
      (footprint "SOD-123_L2.8-W1.8-LS3.7-RD")
      (fields
        (field (name "BOM_SUPPLIER PART") "C176288")
        (field (name "BOM_MANUFACTURER PART") "1N4148W")
        (field (name "CONTRIBUTOR") "LCSC")
      )
      (libsource (lib "altium-import") (part "root_0_1N4148W_C176288_"))
    )
    (comp (ref "D20")
      (value "1N4148W_C176288")
      (footprint "SOD-123_L2.8-W1.8-LS3.7-RD")
      (fields
        (field (name "BOM_SUPPLIER PART") "C176288")
        (field (name "BOM_MANUFACTURER PART") "1N4148W")
        (field (name "CONTRIBUTOR") "LCSC")
      )
      (libsource (lib "altium-import") (part "root_0_1N4148W_C176288_"))
    )
    (comp (ref "D21")
      (value "1N4148W_C176288")
      (footprint "SOD-123_L2.8-W1.8-LS3.7-RD")
      (fields
        (field (name "BOM_SUPPLIER PART") "C176288")
        (field (name "BOM_MANUFACTURER PART") "1N4148W")
        (field (name "CONTRIBUTOR") "LCSC")
      )
      (libsource (lib "altium-import") (part "root_0_1N4148W_C176288_"))
    )
    (comp (ref "D22")
      (value "1N4148W_C176288")
      (footprint "SOD-123_L2.8-W1.8-LS3.7-RD")
      (fields
        (field (name "BOM_SUPPLIER PART") "C176288")
        (field (name "BOM_MANUFACTURER PART") "1N4148W")
        (field (name "CONTRIBUTOR") "LCSC")
      )
      (libsource (lib "altium-import") (part "root_0_1N4148W_C176288_"))
    )
    (comp (ref "D23")
      (value "1N4148W_C176288")
      (footprint "SOD-123_L2.8-W1.8-LS3.7-RD")
      (fields
        (field (name "BOM_SUPPLIER PART") "C176288")
        (field (name "BOM_MANUFACTURER PART") "1N4148W")
        (field (name "CONTRIBUTOR") "LCSC")
      )
      (libsource (lib "altium-import") (part "root_0_1N4148W_C176288_"))
    )
    (comp (ref "D24")
      (value "1N4148W_C176288")
      (footprint "SOD-123_L2.8-W1.8-LS3.7-RD")
      (fields
        (field (name "BOM_SUPPLIER PART") "C176288")
        (field (name "BOM_MANUFACTURER PART") "1N4148W")
        (field (name "CONTRIBUTOR") "LCSC")
      )
      (libsource (lib "altium-import") (part "root_0_1N4148W_C176288_"))
    )
    (comp (ref "D25")
      (value "FR107_C511885")
      (footprint "SOD-123_L2.8-W1.8-LS3.7-RD")
      (fields
        (field (name "BOM_SUPPLIER PART") "C511885")
        (field (name "BOM_MANUFACTURER PART") "FR107")
        (field (name "CONTRIBUTOR") "LCSC")
      )
      (libsource (lib "altium-import") (part "root_2_FR107_C511885_"))
    )
    (comp (ref "D26")
      (value "FR107_C511885")
      (footprint "SOD-123_L2.8-W1.8-LS3.7-RD")
      (fields
        (field (name "BOM_SUPPLIER PART") "C511885")
        (field (name "BOM_MANUFACTURER PART") "FR107")
        (field (name "CONTRIBUTOR") "LCSC")
      )
      (libsource (lib "altium-import") (part "root_2_FR107_C511885_"))
    )
    (comp (ref "D27")
      (value "FR107_C511885")
      (footprint "SOD-123_L2.8-W1.8-LS3.7-RD")
      (fields
        (field (name "BOM_SUPPLIER PART") "C511885")
        (field (name "BOM_MANUFACTURER PART") "FR107")
        (field (name "CONTRIBUTOR") "LCSC")
      )
      (libsource (lib "altium-import") (part "root_2_FR107_C511885_"))
    )
    (comp (ref "D28")
      (value "FR107_C511885")
      (footprint "SOD-123_L2.8-W1.8-LS3.7-RD")
      (fields
        (field (name "BOM_SUPPLIER PART") "C511885")
        (field (name "BOM_MANUFACTURER PART") "FR107")
        (field (name "CONTRIBUTOR") "LCSC")
      )
      (libsource (lib "altium-import") (part "root_2_FR107_C511885_"))
    )
    (comp (ref "D29")
      (value "FR107_C511885")
      (footprint "SOD-123_L2.8-W1.8-LS3.7-RD")
      (fields
        (field (name "BOM_SUPPLIER PART") "C511885")
        (field (name "BOM_MANUFACTURER PART") "FR107")
        (field (name "CONTRIBUTOR") "LCSC")
      )
      (libsource (lib "altium-import") (part "root_2_FR107_C511885_"))
    )
    (comp (ref "D30")
      (value "FR107_C511885")
      (footprint "SOD-123_L2.8-W1.8-LS3.7-RD")
      (fields
        (field (name "BOM_SUPPLIER PART") "C511885")
        (field (name "BOM_MANUFACTURER PART") "FR107")
        (field (name "CONTRIBUTOR") "LCSC")
      )
      (libsource (lib "altium-import") (part "root_2_FR107_C511885_"))
    )
    (comp (ref "D31")
      (value "1N4148W_C176288")
      (footprint "SOD-123_L2.8-W1.8-LS3.7-RD")
      (fields
        (field (name "BOM_SUPPLIER PART") "C176288")
        (field (name "BOM_MANUFACTURER PART") "1N4148W")
        (field (name "CONTRIBUTOR") "LCSC")
      )
      (libsource (lib "altium-import") (part "root_0_1N4148W_C176288_"))
    )
    (comp (ref "D32")
      (value "1N4148W_C176288")
      (footprint "SOD-123_L2.8-W1.8-LS3.7-RD")
      (fields
        (field (name "BOM_SUPPLIER PART") "C176288")
        (field (name "BOM_MANUFACTURER PART") "1N4148W")
        (field (name "CONTRIBUTOR") "LCSC")
      )
      (libsource (lib "altium-import") (part "root_0_1N4148W_C176288_"))
    )
    (comp (ref "D33")
      (value "1N4148W_C176288")
      (footprint "SOD-123_L2.8-W1.8-LS3.7-RD")
      (fields
        (field (name "BOM_SUPPLIER PART") "C176288")
        (field (name "BOM_MANUFACTURER PART") "1N4148W")
        (field (name "CONTRIBUTOR") "LCSC")
      )
      (libsource (lib "altium-import") (part "root_0_1N4148W_C176288_"))
    )
    (comp (ref "D34")
      (value "1N4148W_C176288")
      (footprint "SOD-123_L2.8-W1.8-LS3.7-RD")
      (fields
        (field (name "BOM_SUPPLIER PART") "C176288")
        (field (name "BOM_MANUFACTURER PART") "1N4148W")
        (field (name "CONTRIBUTOR") "LCSC")
      )
      (libsource (lib "altium-import") (part "root_0_1N4148W_C176288_"))
    )
    (comp (ref "D35")
      (value "1N4148W_C176288")
      (footprint "SOD-123_L2.8-W1.8-LS3.7-RD")
      (fields
        (field (name "BOM_SUPPLIER PART") "C176288")
        (field (name "BOM_MANUFACTURER PART") "1N4148W")
        (field (name "CONTRIBUTOR") "LCSC")
      )
      (libsource (lib "altium-import") (part "root_0_1N4148W_C176288_"))
    )
    (comp (ref "D36")
      (value "1N4148W_C176288")
      (footprint "SOD-123_L2.8-W1.8-LS3.7-RD")
      (fields
        (field (name "BOM_SUPPLIER PART") "C176288")
        (field (name "BOM_MANUFACTURER PART") "1N4148W")
        (field (name "CONTRIBUTOR") "LCSC")
      )
      (libsource (lib "altium-import") (part "root_0_1N4148W_C176288_"))
    )
    (comp (ref "D37")
      (value "FR107_C511885")
      (footprint "SOD-123_L2.8-W1.8-LS3.7-RD")
      (fields
        (field (name "BOM_SUPPLIER PART") "C511885")
        (field (name "BOM_MANUFACTURER PART") "FR107")
        (field (name "CONTRIBUTOR") "LCSC")
      )
      (libsource (lib "altium-import") (part "root_2_FR107_C511885_"))
    )
    (comp (ref "D38")
      (value "FR107_C511885")
      (footprint "SOD-123_L2.8-W1.8-LS3.7-RD")
      (fields
        (field (name "BOM_SUPPLIER PART") "C511885")
        (field (name "BOM_MANUFACTURER PART") "FR107")
        (field (name "CONTRIBUTOR") "LCSC")
      )
      (libsource (lib "altium-import") (part "root_2_FR107_C511885_"))
    )
    (comp (ref "D39")
      (value "FR107_C511885")
      (footprint "SOD-123_L2.8-W1.8-LS3.7-RD")
      (fields
        (field (name "BOM_SUPPLIER PART") "C511885")
        (field (name "BOM_MANUFACTURER PART") "FR107")
        (field (name "CONTRIBUTOR") "LCSC")
      )
      (libsource (lib "altium-import") (part "root_2_FR107_C511885_"))
    )
    (comp (ref "D40")
      (value "1N4148W_C176288")
      (footprint "SOD-123_L2.8-W1.8-LS3.7-RD")
      (fields
        (field (name "BOM_SUPPLIER PART") "C176288")
        (field (name "BOM_MANUFACTURER PART") "1N4148W")
        (field (name "CONTRIBUTOR") "LCSC")
      )
      (libsource (lib "altium-import") (part "root_0_1N4148W_C176288_"))
    )
    (comp (ref "D41")
      (value "1N4148W_C176288")
      (footprint "SOD-123_L2.8-W1.8-LS3.7-RD")
      (fields
        (field (name "BOM_SUPPLIER PART") "C176288")
        (field (name "BOM_MANUFACTURER PART") "1N4148W")
        (field (name "CONTRIBUTOR") "LCSC")
      )
      (libsource (lib "altium-import") (part "root_0_1N4148W_C176288_"))
    )
    (comp (ref "D42")
      (value "1N4148W_C176288")
      (footprint "SOD-123_L2.8-W1.8-LS3.7-RD")
      (fields
        (field (name "BOM_SUPPLIER PART") "C176288")
        (field (name "BOM_MANUFACTURER PART") "1N4148W")
        (field (name "CONTRIBUTOR") "LCSC")
      )
      (libsource (lib "altium-import") (part "root_0_1N4148W_C176288_"))
    )
    (comp (ref "D43")
      (value "1N4148W_C176288")
      (footprint "SOD-123_L2.8-W1.8-LS3.7-RD")
      (fields
        (field (name "BOM_SUPPLIER PART") "C176288")
        (field (name "BOM_MANUFACTURER PART") "1N4148W")
        (field (name "CONTRIBUTOR") "LCSC")
      )
      (libsource (lib "altium-import") (part "root_0_1N4148W_C176288_"))
    )
    (comp (ref "D44")
      (value "1N4148W_C176288")
      (footprint "SOD-123_L2.8-W1.8-LS3.7-RD")
      (fields
        (field (name "BOM_SUPPLIER PART") "C176288")
        (field (name "BOM_MANUFACTURER PART") "1N4148W")
        (field (name "CONTRIBUTOR") "LCSC")
      )
      (libsource (lib "altium-import") (part "root_0_1N4148W_C176288_"))
    )
    (comp (ref "D45")
      (value "1N4148W_C176288")
      (footprint "SOD-123_L2.8-W1.8-LS3.7-RD")
      (fields
        (field (name "BOM_SUPPLIER PART") "C176288")
        (field (name "BOM_MANUFACTURER PART") "1N4148W")
        (field (name "CONTRIBUTOR") "LCSC")
      )
      (libsource (lib "altium-import") (part "root_0_1N4148W_C176288_"))
    )
    (comp (ref "D46")
      (value "1N4148W_C176288")
      (footprint "SOD-123_L2.8-W1.8-LS3.7-RD")
      (fields
        (field (name "BOM_SUPPLIER PART") "C176288")
        (field (name "BOM_MANUFACTURER PART") "1N4148W")
        (field (name "CONTRIBUTOR") "LCSC")
      )
      (libsource (lib "altium-import") (part "root_0_1N4148W_C176288_"))
    )
    (comp (ref "D47")
      (value "1N4148W_C176288")
      (footprint "SOD-123_L2.8-W1.8-LS3.7-RD")
      (fields
        (field (name "BOM_SUPPLIER PART") "C176288")
        (field (name "BOM_MANUFACTURER PART") "1N4148W")
        (field (name "CONTRIBUTOR") "LCSC")
      )
      (libsource (lib "altium-import") (part "root_0_1N4148W_C176288_"))
    )
    (comp (ref "D48")
      (value "1N4148W_C176288")
      (footprint "SOD-123_L2.8-W1.8-LS3.7-RD")
      (fields
        (field (name "BOM_SUPPLIER PART") "C176288")
        (field (name "BOM_MANUFACTURER PART") "1N4148W")
        (field (name "CONTRIBUTOR") "LCSC")
      )
      (libsource (lib "altium-import") (part "root_0_1N4148W_C176288_"))
    )
    (comp (ref "D49")
      (value "1N4148W_C176288")
      (footprint "SOD-123_L2.8-W1.8-LS3.7-RD")
      (fields
        (field (name "BOM_SUPPLIER PART") "C176288")
        (field (name "BOM_MANUFACTURER PART") "1N4148W")
        (field (name "CONTRIBUTOR") "LCSC")
      )
      (libsource (lib "altium-import") (part "root_0_1N4148W_C176288_"))
    )
    (comp (ref "D50")
      (value "1N4148W_C176288")
      (footprint "SOD-123_L2.8-W1.8-LS3.7-RD")
      (fields
        (field (name "BOM_SUPPLIER PART") "C176288")
        (field (name "BOM_MANUFACTURER PART") "1N4148W")
        (field (name "CONTRIBUTOR") "LCSC")
      )
      (libsource (lib "altium-import") (part "root_0_1N4148W_C176288_"))
    )
    (comp (ref "D51")
      (value "1N4148W_C176288")
      (footprint "SOD-123_L2.8-W1.8-LS3.7-RD")
      (fields
        (field (name "BOM_SUPPLIER PART") "C176288")
        (field (name "BOM_MANUFACTURER PART") "1N4148W")
        (field (name "CONTRIBUTOR") "LCSC")
      )
      (libsource (lib "altium-import") (part "root_0_1N4148W_C176288_"))
    )
    (comp (ref "D52")
      (value "FR107_C511885")
      (footprint "SOD-123_L2.8-W1.8-LS3.7-RD")
      (fields
        (field (name "BOM_SUPPLIER PART") "C511885")
        (field (name "BOM_MANUFACTURER PART") "FR107")
        (field (name "CONTRIBUTOR") "LCSC")
      )
      (libsource (lib "altium-import") (part "root_2_FR107_C511885_"))
    )
    (comp (ref "D53")
      (value "FR107_C511885")
      (footprint "SOD-123_L2.8-W1.8-LS3.7-RD")
      (fields
        (field (name "BOM_SUPPLIER PART") "C511885")
        (field (name "BOM_MANUFACTURER PART") "FR107")
        (field (name "CONTRIBUTOR") "LCSC")
      )
      (libsource (lib "altium-import") (part "root_2_FR107_C511885_"))
    )
    (comp (ref "D54")
      (value "FR107_C511885")
      (footprint "SOD-123_L2.8-W1.8-LS3.7-RD")
      (fields
        (field (name "BOM_SUPPLIER PART") "C511885")
        (field (name "BOM_MANUFACTURER PART") "FR107")
        (field (name "CONTRIBUTOR") "LCSC")
      )
      (libsource (lib "altium-import") (part "root_2_FR107_C511885_"))
    )
    (comp (ref "D55")
      (value "FR107_C511885")
      (footprint "SOD-123_L2.8-W1.8-LS3.7-RD")
      (fields
        (field (name "BOM_SUPPLIER PART") "C511885")
        (field (name "BOM_MANUFACTURER PART") "FR107")
        (field (name "CONTRIBUTOR") "LCSC")
      )
      (libsource (lib "altium-import") (part "root_2_FR107_C511885_"))
    )
    (comp (ref "D56")
      (value "FR107_C511885")
      (footprint "SOD-123_L2.8-W1.8-LS3.7-RD")
      (fields
        (field (name "BOM_SUPPLIER PART") "C511885")
        (field (name "BOM_MANUFACTURER PART") "FR107")
        (field (name "CONTRIBUTOR") "LCSC")
      )
      (libsource (lib "altium-import") (part "root_2_FR107_C511885_"))
    )
    (comp (ref "D57")
      (value "FR107_C511885")
      (footprint "SOD-123_L2.8-W1.8-LS3.7-RD")
      (fields
        (field (name "BOM_SUPPLIER PART") "C511885")
        (field (name "BOM_MANUFACTURER PART") "FR107")
        (field (name "CONTRIBUTOR") "LCSC")
      )
      (libsource (lib "altium-import") (part "root_2_FR107_C511885_"))
    )
    (comp (ref "D58")
      (value "1N4148W_C176288")
      (footprint "SOD-123_L2.8-W1.8-LS3.7-RD")
      (fields
        (field (name "BOM_SUPPLIER PART") "C176288")
        (field (name "BOM_MANUFACTURER PART") "1N4148W")
        (field (name "CONTRIBUTOR") "LCSC")
      )
      (libsource (lib "altium-import") (part "root_0_1N4148W_C176288_"))
    )
    (comp (ref "D59")
      (value "1N4148W_C176288")
      (footprint "SOD-123_L2.8-W1.8-LS3.7-RD")
      (fields
        (field (name "BOM_SUPPLIER PART") "C176288")
        (field (name "BOM_MANUFACTURER PART") "1N4148W")
        (field (name "CONTRIBUTOR") "LCSC")
      )
      (libsource (lib "altium-import") (part "root_0_1N4148W_C176288_"))
    )
    (comp (ref "D60")
      (value "1N4148W_C176288")
      (footprint "SOD-123_L2.8-W1.8-LS3.7-RD")
      (fields
        (field (name "BOM_SUPPLIER PART") "C176288")
        (field (name "BOM_MANUFACTURER PART") "1N4148W")
        (field (name "CONTRIBUTOR") "LCSC")
      )
      (libsource (lib "altium-import") (part "root_0_1N4148W_C176288_"))
    )
    (comp (ref "D61")
      (value "1N4148W_C176288")
      (footprint "SOD-123_L2.8-W1.8-LS3.7-RD")
      (fields
        (field (name "BOM_SUPPLIER PART") "C176288")
        (field (name "BOM_MANUFACTURER PART") "1N4148W")
        (field (name "CONTRIBUTOR") "LCSC")
      )
      (libsource (lib "altium-import") (part "root_0_1N4148W_C176288_"))
    )
    (comp (ref "D62")
      (value "1N4148W_C176288")
      (footprint "SOD-123_L2.8-W1.8-LS3.7-RD")
      (fields
        (field (name "BOM_SUPPLIER PART") "C176288")
        (field (name "BOM_MANUFACTURER PART") "1N4148W")
        (field (name "CONTRIBUTOR") "LCSC")
      )
      (libsource (lib "altium-import") (part "root_0_1N4148W_C176288_"))
    )
    (comp (ref "D63")
      (value "1N4148W_C176288")
      (footprint "SOD-123_L2.8-W1.8-LS3.7-RD")
      (fields
        (field (name "BOM_SUPPLIER PART") "C176288")
        (field (name "BOM_MANUFACTURER PART") "1N4148W")
        (field (name "CONTRIBUTOR") "LCSC")
      )
      (libsource (lib "altium-import") (part "root_0_1N4148W_C176288_"))
    )
    (comp (ref "D64")
      (value "1N4148W_C176288")
      (footprint "SOD-123_L2.8-W1.8-LS3.7-RD")
      (fields
        (field (name "BOM_SUPPLIER PART") "C176288")
        (field (name "BOM_MANUFACTURER PART") "1N4148W")
        (field (name "CONTRIBUTOR") "LCSC")
      )
      (libsource (lib "altium-import") (part "root_0_1N4148W_C176288_"))
    )
    (comp (ref "D65")
      (value "1N4148W_C176288")
      (footprint "SOD-123_L2.8-W1.8-LS3.7-RD")
      (fields
        (field (name "BOM_SUPPLIER PART") "C176288")
        (field (name "BOM_MANUFACTURER PART") "1N4148W")
        (field (name "CONTRIBUTOR") "LCSC")
      )
      (libsource (lib "altium-import") (part "root_0_1N4148W_C176288_"))
    )
    (comp (ref "D66")
      (value "1N4148W_C176288")
      (footprint "SOD-123_L2.8-W1.8-LS3.7-RD")
      (fields
        (field (name "BOM_SUPPLIER PART") "C176288")
        (field (name "BOM_MANUFACTURER PART") "1N4148W")
        (field (name "CONTRIBUTOR") "LCSC")
      )
      (libsource (lib "altium-import") (part "root_0_1N4148W_C176288_"))
    )
    (comp (ref "D67")
      (value "1N4148W_C176288")
      (footprint "SOD-123_L2.8-W1.8-LS3.7-RD")
      (fields
        (field (name "BOM_SUPPLIER PART") "C176288")
        (field (name "BOM_MANUFACTURER PART") "1N4148W")
        (field (name "CONTRIBUTOR") "LCSC")
      )
      (libsource (lib "altium-import") (part "root_0_1N4148W_C176288_"))
    )
    (comp (ref "D68")
      (value "1N4148W_C176288")
      (footprint "SOD-123_L2.8-W1.8-LS3.7-RD")
      (fields
        (field (name "BOM_SUPPLIER PART") "C176288")
        (field (name "BOM_MANUFACTURER PART") "1N4148W")
        (field (name "CONTRIBUTOR") "LCSC")
      )
      (libsource (lib "altium-import") (part "root_0_1N4148W_C176288_"))
    )
    (comp (ref "D69")
      (value "1N4148W_C176288")
      (footprint "SOD-123_L2.8-W1.8-LS3.7-RD")
      (fields
        (field (name "BOM_SUPPLIER PART") "C176288")
        (field (name "BOM_MANUFACTURER PART") "1N4148W")
        (field (name "CONTRIBUTOR") "LCSC")
      )
      (libsource (lib "altium-import") (part "root_0_1N4148W_C176288_"))
    )
    (comp (ref "D70")
      (value "FR107_C511885")
      (footprint "SOD-123_L2.8-W1.8-LS3.7-RD")
      (fields
        (field (name "BOM_SUPPLIER PART") "C511885")
        (field (name "BOM_MANUFACTURER PART") "FR107")
        (field (name "CONTRIBUTOR") "LCSC")
      )
      (libsource (lib "altium-import") (part "root_2_FR107_C511885_"))
    )
    (comp (ref "D71")
      (value "FR107_C511885")
      (footprint "SOD-123_L2.8-W1.8-LS3.7-RD")
      (fields
        (field (name "BOM_SUPPLIER PART") "C511885")
        (field (name "BOM_MANUFACTURER PART") "FR107")
        (field (name "CONTRIBUTOR") "LCSC")
      )
      (libsource (lib "altium-import") (part "root_2_FR107_C511885_"))
    )
    (comp (ref "D72")
      (value "FR107_C511885")
      (footprint "SOD-123_L2.8-W1.8-LS3.7-RD")
      (fields
        (field (name "BOM_SUPPLIER PART") "C511885")
        (field (name "BOM_MANUFACTURER PART") "FR107")
        (field (name "CONTRIBUTOR") "LCSC")
      )
      (libsource (lib "altium-import") (part "root_2_FR107_C511885_"))
    )
    (comp (ref "D73")
      (value "1N4148W_C176288")
      (footprint "SOD-123_L2.8-W1.8-LS3.7-RD")
      (fields
        (field (name "BOM_SUPPLIER PART") "C176288")
        (field (name "BOM_MANUFACTURER PART") "1N4148W")
        (field (name "CONTRIBUTOR") "LCSC")
      )
      (libsource (lib "altium-import") (part "root_0_1N4148W_C176288_"))
    )
    (comp (ref "D74")
      (value "1N4148W_C176288")
      (footprint "SOD-123_L2.8-W1.8-LS3.7-RD")
      (fields
        (field (name "BOM_SUPPLIER PART") "C176288")
        (field (name "BOM_MANUFACTURER PART") "1N4148W")
        (field (name "CONTRIBUTOR") "LCSC")
      )
      (libsource (lib "altium-import") (part "root_0_1N4148W_C176288_"))
    )
    (comp (ref "D75")
      (value "1N4148W_C176288")
      (footprint "SOD-123_L2.8-W1.8-LS3.7-RD")
      (fields
        (field (name "BOM_SUPPLIER PART") "C176288")
        (field (name "BOM_MANUFACTURER PART") "1N4148W")
        (field (name "CONTRIBUTOR") "LCSC")
      )
      (libsource (lib "altium-import") (part "root_0_1N4148W_C176288_"))
    )
    (comp (ref "D76")
      (value "1N4148W_C176288")
      (footprint "SOD-123_L2.8-W1.8-LS3.7-RD")
      (fields
        (field (name "BOM_SUPPLIER PART") "C176288")
        (field (name "BOM_MANUFACTURER PART") "1N4148W")
        (field (name "CONTRIBUTOR") "LCSC")
      )
      (libsource (lib "altium-import") (part "root_0_1N4148W_C176288_"))
    )
    (comp (ref "D77")
      (value "1N4148W_C176288")
      (footprint "SOD-123_L2.8-W1.8-LS3.7-RD")
      (fields
        (field (name "BOM_SUPPLIER PART") "C176288")
        (field (name "BOM_MANUFACTURER PART") "1N4148W")
        (field (name "CONTRIBUTOR") "LCSC")
      )
      (libsource (lib "altium-import") (part "root_0_1N4148W_C176288_"))
    )
    (comp (ref "D78")
      (value "1N4148W_C176288")
      (footprint "SOD-123_L2.8-W1.8-LS3.7-RD")
      (fields
        (field (name "BOM_SUPPLIER PART") "C176288")
        (field (name "BOM_MANUFACTURER PART") "1N4148W")
        (field (name "CONTRIBUTOR") "LCSC")
      )
      (libsource (lib "altium-import") (part "root_0_1N4148W_C176288_"))
    )
    (comp (ref "D79")
      (value "FR107_C511885")
      (footprint "SOD-123_L2.8-W1.8-LS3.7-RD")
      (fields
        (field (name "BOM_SUPPLIER PART") "C511885")
        (field (name "BOM_MANUFACTURER PART") "FR107")
        (field (name "CONTRIBUTOR") "LCSC")
      )
      (libsource (lib "altium-import") (part "root_2_FR107_C511885_"))
    )
    (comp (ref "D80")
      (value "FR107_C511885")
      (footprint "SOD-123_L2.8-W1.8-LS3.7-RD")
      (fields
        (field (name "BOM_SUPPLIER PART") "C511885")
        (field (name "BOM_MANUFACTURER PART") "FR107")
        (field (name "CONTRIBUTOR") "LCSC")
      )
      (libsource (lib "altium-import") (part "root_2_FR107_C511885_"))
    )
    (comp (ref "D81")
      (value "FR107_C511885")
      (footprint "SOD-123_L2.8-W1.8-LS3.7-RD")
      (fields
        (field (name "BOM_SUPPLIER PART") "C511885")
        (field (name "BOM_MANUFACTURER PART") "FR107")
        (field (name "CONTRIBUTOR") "LCSC")
      )
      (libsource (lib "altium-import") (part "root_2_FR107_C511885_"))
    )
    (comp (ref "D82")
      (value "FR107_C511885")
      (footprint "SOD-123_L2.8-W1.8-LS3.7-RD")
      (fields
        (field (name "BOM_SUPPLIER PART") "C511885")
        (field (name "BOM_MANUFACTURER PART") "FR107")
        (field (name "CONTRIBUTOR") "LCSC")
      )
      (libsource (lib "altium-import") (part "root_2_FR107_C511885_"))
    )
    (comp (ref "D83")
      (value "FR107_C511885")
      (footprint "SOD-123_L2.8-W1.8-LS3.7-RD")
      (fields
        (field (name "BOM_SUPPLIER PART") "C511885")
        (field (name "BOM_MANUFACTURER PART") "FR107")
        (field (name "CONTRIBUTOR") "LCSC")
      )
      (libsource (lib "altium-import") (part "root_2_FR107_C511885_"))
    )
    (comp (ref "D84")
      (value "FR107_C511885")
      (footprint "SOD-123_L2.8-W1.8-LS3.7-RD")
      (fields
        (field (name "BOM_SUPPLIER PART") "C511885")
        (field (name "BOM_MANUFACTURER PART") "FR107")
        (field (name "CONTRIBUTOR") "LCSC")
      )
      (libsource (lib "altium-import") (part "root_2_FR107_C511885_"))
    )
    (comp (ref "D85")
      (value "1N4148W_C176288")
      (footprint "SOD-123_L2.8-W1.8-LS3.7-RD")
      (fields
        (field (name "BOM_SUPPLIER PART") "C176288")
        (field (name "BOM_MANUFACTURER PART") "1N4148W")
        (field (name "CONTRIBUTOR") "LCSC")
      )
      (libsource (lib "altium-import") (part "root_0_1N4148W_C176288_"))
    )
    (comp (ref "D86")
      (value "1N4148W_C176288")
      (footprint "SOD-123_L2.8-W1.8-LS3.7-RD")
      (fields
        (field (name "BOM_SUPPLIER PART") "C176288")
        (field (name "BOM_MANUFACTURER PART") "1N4148W")
        (field (name "CONTRIBUTOR") "LCSC")
      )
      (libsource (lib "altium-import") (part "root_0_1N4148W_C176288_"))
    )
    (comp (ref "D87")
      (value "1N4148W_C176288")
      (footprint "SOD-123_L2.8-W1.8-LS3.7-RD")
      (fields
        (field (name "BOM_SUPPLIER PART") "C176288")
        (field (name "BOM_MANUFACTURER PART") "1N4148W")
        (field (name "CONTRIBUTOR") "LCSC")
      )
      (libsource (lib "altium-import") (part "root_0_1N4148W_C176288_"))
    )
    (comp (ref "D88")
      (value "1N4148W_C176288")
      (footprint "SOD-123_L2.8-W1.8-LS3.7-RD")
      (fields
        (field (name "BOM_SUPPLIER PART") "C176288")
        (field (name "BOM_MANUFACTURER PART") "1N4148W")
        (field (name "CONTRIBUTOR") "LCSC")
      )
      (libsource (lib "altium-import") (part "root_0_1N4148W_C176288_"))
    )
    (comp (ref "D89")
      (value "1N4148W_C176288")
      (footprint "SOD-123_L2.8-W1.8-LS3.7-RD")
      (fields
        (field (name "BOM_SUPPLIER PART") "C176288")
        (field (name "BOM_MANUFACTURER PART") "1N4148W")
        (field (name "CONTRIBUTOR") "LCSC")
      )
      (libsource (lib "altium-import") (part "root_0_1N4148W_C176288_"))
    )
    (comp (ref "D90")
      (value "1N4148W_C176288")
      (footprint "SOD-123_L2.8-W1.8-LS3.7-RD")
      (fields
        (field (name "BOM_SUPPLIER PART") "C176288")
        (field (name "BOM_MANUFACTURER PART") "1N4148W")
        (field (name "CONTRIBUTOR") "LCSC")
      )
      (libsource (lib "altium-import") (part "root_0_1N4148W_C176288_"))
    )
    (comp (ref "D91")
      (value "FR107_C511885")
      (footprint "SOD-123_L2.8-W1.8-LS3.7-RD")
      (fields
        (field (name "BOM_SUPPLIER PART") "C511885")
        (field (name "BOM_MANUFACTURER PART") "FR107")
        (field (name "CONTRIBUTOR") "LCSC")
      )
      (libsource (lib "altium-import") (part "root_2_FR107_C511885_"))
    )
    (comp (ref "D92")
      (value "FR107_C511885")
      (footprint "SOD-123_L2.8-W1.8-LS3.7-RD")
      (fields
        (field (name "BOM_SUPPLIER PART") "C511885")
        (field (name "BOM_MANUFACTURER PART") "FR107")
        (field (name "CONTRIBUTOR") "LCSC")
      )
      (libsource (lib "altium-import") (part "root_2_FR107_C511885_"))
    )
    (comp (ref "D93")
      (value "FR107_C511885")
      (footprint "SOD-123_L2.8-W1.8-LS3.7-RD")
      (fields
        (field (name "BOM_SUPPLIER PART") "C511885")
        (field (name "BOM_MANUFACTURER PART") "FR107")
        (field (name "CONTRIBUTOR") "LCSC")
      )
      (libsource (lib "altium-import") (part "root_2_FR107_C511885_"))
    )
    (comp (ref "D94")
      (value "1N4148W_C176288")
      (footprint "SOD-123_L2.8-W1.8-LS3.7-RD")
      (fields
        (field (name "BOM_SUPPLIER PART") "C176288")
        (field (name "BOM_MANUFACTURER PART") "1N4148W")
        (field (name "CONTRIBUTOR") "LCSC")
      )
      (libsource (lib "altium-import") (part "root_0_1N4148W_C176288_"))
    )
    (comp (ref "D95")
      (value "1N4148W_C176288")
      (footprint "SOD-123_L2.8-W1.8-LS3.7-RD")
      (fields
        (field (name "BOM_SUPPLIER PART") "C176288")
        (field (name "BOM_MANUFACTURER PART") "1N4148W")
        (field (name "CONTRIBUTOR") "LCSC")
      )
      (libsource (lib "altium-import") (part "root_0_1N4148W_C176288_"))
    )
    (comp (ref "D96")
      (value "1N4148W_C176288")
      (footprint "SOD-123_L2.8-W1.8-LS3.7-RD")
      (fields
        (field (name "BOM_SUPPLIER PART") "C176288")
        (field (name "BOM_MANUFACTURER PART") "1N4148W")
        (field (name "CONTRIBUTOR") "LCSC")
      )
      (libsource (lib "altium-import") (part "root_0_1N4148W_C176288_"))
    )
    (comp (ref "D97")
      (value "1N4148W_C176288")
      (footprint "SOD-123_L2.8-W1.8-LS3.7-RD")
      (fields
        (field (name "BOM_SUPPLIER PART") "C176288")
        (field (name "BOM_MANUFACTURER PART") "1N4148W")
        (field (name "CONTRIBUTOR") "LCSC")
      )
      (libsource (lib "altium-import") (part "root_0_1N4148W_C176288_"))
    )
    (comp (ref "D98")
      (value "1N4148W_C176288")
      (footprint "SOD-123_L2.8-W1.8-LS3.7-RD")
      (fields
        (field (name "BOM_SUPPLIER PART") "C176288")
        (field (name "BOM_MANUFACTURER PART") "1N4148W")
        (field (name "CONTRIBUTOR") "LCSC")
      )
      (libsource (lib "altium-import") (part "root_0_1N4148W_C176288_"))
    )
    (comp (ref "D99")
      (value "1N4148W_C176288")
      (footprint "SOD-123_L2.8-W1.8-LS3.7-RD")
      (fields
        (field (name "BOM_SUPPLIER PART") "C176288")
        (field (name "BOM_MANUFACTURER PART") "1N4148W")
        (field (name "CONTRIBUTOR") "LCSC")
      )
      (libsource (lib "altium-import") (part "root_0_1N4148W_C176288_"))
    )
    (comp (ref "D100")
      (value "1N4148W_C176288")
      (footprint "SOD-123_L2.8-W1.8-LS3.7-RD")
      (fields
        (field (name "BOM_SUPPLIER PART") "C176288")
        (field (name "BOM_MANUFACTURER PART") "1N4148W")
        (field (name "CONTRIBUTOR") "LCSC")
      )
      (libsource (lib "altium-import") (part "root_0_1N4148W_C176288_"))
    )
    (comp (ref "D101")
      (value "1N4148W_C176288")
      (footprint "SOD-123_L2.8-W1.8-LS3.7-RD")
      (fields
        (field (name "BOM_SUPPLIER PART") "C176288")
        (field (name "BOM_MANUFACTURER PART") "1N4148W")
        (field (name "CONTRIBUTOR") "LCSC")
      )
      (libsource (lib "altium-import") (part "root_0_1N4148W_C176288_"))
    )
    (comp (ref "D102")
      (value "1N4148W_C176288")
      (footprint "SOD-123_L2.8-W1.8-LS3.7-RD")
      (fields
        (field (name "BOM_SUPPLIER PART") "C176288")
        (field (name "BOM_MANUFACTURER PART") "1N4148W")
        (field (name "CONTRIBUTOR") "LCSC")
      )
      (libsource (lib "altium-import") (part "root_0_1N4148W_C176288_"))
    )
    (comp (ref "D103")
      (value "1N4148W_C176288")
      (footprint "SOD-123_L2.8-W1.8-LS3.7-RD")
      (fields
        (field (name "BOM_SUPPLIER PART") "C176288")
        (field (name "BOM_MANUFACTURER PART") "1N4148W")
        (field (name "CONTRIBUTOR") "LCSC")
      )
      (libsource (lib "altium-import") (part "root_0_1N4148W_C176288_"))
    )
    (comp (ref "D104")
      (value "1N4148W_C176288")
      (footprint "SOD-123_L2.8-W1.8-LS3.7-RD")
      (fields
        (field (name "BOM_SUPPLIER PART") "C176288")
        (field (name "BOM_MANUFACTURER PART") "1N4148W")
        (field (name "CONTRIBUTOR") "LCSC")
      )
      (libsource (lib "altium-import") (part "root_0_1N4148W_C176288_"))
    )
    (comp (ref "D105")
      (value "1N4148W_C176288")
      (footprint "SOD-123_L2.8-W1.8-LS3.7-RD")
      (fields
        (field (name "BOM_SUPPLIER PART") "C176288")
        (field (name "BOM_MANUFACTURER PART") "1N4148W")
        (field (name "CONTRIBUTOR") "LCSC")
      )
      (libsource (lib "altium-import") (part "root_0_1N4148W_C176288_"))
    )
    (comp (ref "D106")
      (value "FR107_C511885")
      (footprint "SOD-123_L2.8-W1.8-LS3.7-RD")
      (fields
        (field (name "BOM_SUPPLIER PART") "C511885")
        (field (name "BOM_MANUFACTURER PART") "FR107")
        (field (name "CONTRIBUTOR") "LCSC")
      )
      (libsource (lib "altium-import") (part "root_2_FR107_C511885_"))
    )
    (comp (ref "D107")
      (value "FR107_C511885")
      (footprint "SOD-123_L2.8-W1.8-LS3.7-RD")
      (fields
        (field (name "BOM_SUPPLIER PART") "C511885")
        (field (name "BOM_MANUFACTURER PART") "FR107")
        (field (name "CONTRIBUTOR") "LCSC")
      )
      (libsource (lib "altium-import") (part "root_2_FR107_C511885_"))
    )
    (comp (ref "D108")
      (value "FR107_C511885")
      (footprint "SOD-123_L2.8-W1.8-LS3.7-RD")
      (fields
        (field (name "BOM_SUPPLIER PART") "C511885")
        (field (name "BOM_MANUFACTURER PART") "FR107")
        (field (name "CONTRIBUTOR") "LCSC")
      )
      (libsource (lib "altium-import") (part "root_2_FR107_C511885_"))
    )
    (comp (ref "D109")
      (value "FR107_C511885")
      (footprint "SOD-123_L2.8-W1.8-LS3.7-RD")
      (fields
        (field (name "BOM_SUPPLIER PART") "C511885")
        (field (name "BOM_MANUFACTURER PART") "FR107")
        (field (name "CONTRIBUTOR") "LCSC")
      )
      (libsource (lib "altium-import") (part "root_2_FR107_C511885_"))
    )
    (comp (ref "D110")
      (value "FR107_C511885")
      (footprint "SOD-123_L2.8-W1.8-LS3.7-RD")
      (fields
        (field (name "BOM_SUPPLIER PART") "C511885")
        (field (name "BOM_MANUFACTURER PART") "FR107")
        (field (name "CONTRIBUTOR") "LCSC")
      )
      (libsource (lib "altium-import") (part "root_2_FR107_C511885_"))
    )
    (comp (ref "D112")
      (value "1N4148W_C176288")
      (footprint "SOD-123_L2.8-W1.8-LS3.7-RD")
      (fields
        (field (name "BOM_SUPPLIER PART") "C176288")
        (field (name "BOM_MANUFACTURER PART") "1N4148W")
        (field (name "CONTRIBUTOR") "LCSC")
      )
      (libsource (lib "altium-import") (part "root_0_1N4148W_C176288_"))
    )
    (comp (ref "D113")
      (value "1N4148W_C176288")
      (footprint "SOD-123_L2.8-W1.8-LS3.7-RD")
      (fields
        (field (name "BOM_SUPPLIER PART") "C176288")
        (field (name "BOM_MANUFACTURER PART") "1N4148W")
        (field (name "CONTRIBUTOR") "LCSC")
      )
      (libsource (lib "altium-import") (part "root_0_1N4148W_C176288_"))
    )
    (comp (ref "D114")
      (value "1N4148W_C176288")
      (footprint "SOD-123_L2.8-W1.8-LS3.7-RD")
      (fields
        (field (name "BOM_SUPPLIER PART") "C176288")
        (field (name "BOM_MANUFACTURER PART") "1N4148W")
        (field (name "CONTRIBUTOR") "LCSC")
      )
      (libsource (lib "altium-import") (part "root_0_1N4148W_C176288_"))
    )
    (comp (ref "D115")
      (value "1N4148W_C176288")
      (footprint "SOD-123_L2.8-W1.8-LS3.7-RD")
      (fields
        (field (name "BOM_SUPPLIER PART") "C176288")
        (field (name "BOM_MANUFACTURER PART") "1N4148W")
        (field (name "CONTRIBUTOR") "LCSC")
      )
      (libsource (lib "altium-import") (part "root_0_1N4148W_C176288_"))
    )
    (comp (ref "D116")
      (value "1N4148W_C176288")
      (footprint "SOD-123_L2.8-W1.8-LS3.7-RD")
      (fields
        (field (name "BOM_SUPPLIER PART") "C176288")
        (field (name "BOM_MANUFACTURER PART") "1N4148W")
        (field (name "CONTRIBUTOR") "LCSC")
      )
      (libsource (lib "altium-import") (part "root_0_1N4148W_C176288_"))
    )
    (comp (ref "D117")
      (value "1N4148W_C176288")
      (footprint "SOD-123_L2.8-W1.8-LS3.7-RD")
      (fields
        (field (name "BOM_SUPPLIER PART") "C176288")
        (field (name "BOM_MANUFACTURER PART") "1N4148W")
        (field (name "CONTRIBUTOR") "LCSC")
      )
      (libsource (lib "altium-import") (part "root_0_1N4148W_C176288_"))
    )
    (comp (ref "D118")
      (value "FR107_C511885")
      (footprint "SOD-123_L2.8-W1.8-LS3.7-RD")
      (fields
        (field (name "BOM_SUPPLIER PART") "C511885")
        (field (name "BOM_MANUFACTURER PART") "FR107")
        (field (name "CONTRIBUTOR") "LCSC")
      )
      (libsource (lib "altium-import") (part "root_2_FR107_C511885_"))
    )
    (comp (ref "FPC2")
      (value "40FHH-SM1-GAN-TF(LF)(SN)")
      (footprint "FPC-SMD_JST_40FHH-SM1-GAN-TF")
      (fields (field (name "BOM_SUPPLIER PART") "C593938") (field (name "CONTRIBUTOR") "LCSC"))
      (libsource (lib "altium-import") (part "root_2_40FHH-SM1-GAN-TF(LF)(SN)_"))
    )
    (comp (ref "Q1")
      (value "AP2300")
      (footprint "SOT-23-3_L2.9-W1.3-P0.95-LS2.4-BR")
      (fields (field (name "BOM_SUPPLIER PART") "C360338") (field (name "CONTRIBUTOR") "LCSC"))
      (libsource (lib "altium-import") (part "root_0_AP2300_"))
    )
    (comp (ref "Q2")
      (value "AP2300")
      (footprint "SOT-23-3_L2.9-W1.3-P0.95-LS2.4-BR")
      (fields (field (name "BOM_SUPPLIER PART") "C360338") (field (name "CONTRIBUTOR") "LCSC"))
      (libsource (lib "altium-import") (part "root_0_AP2300_"))
    )
    (comp (ref "Q3")
      (value "AP2300")
      (footprint "SOT-23-3_L2.9-W1.3-P0.95-LS2.4-BR")
      (fields (field (name "BOM_SUPPLIER PART") "C360338") (field (name "CONTRIBUTOR") "LCSC"))
      (libsource (lib "altium-import") (part "root_0_AP2300_"))
    )
    (comp (ref "Q4")
      (value "AP2300")
      (footprint "SOT-23-3_L2.9-W1.3-P0.95-LS2.4-BR")
      (fields (field (name "BOM_SUPPLIER PART") "C360338") (field (name "CONTRIBUTOR") "LCSC"))
      (libsource (lib "altium-import") (part "root_0_AP2300_"))
    )
    (comp (ref "Q5")
      (value "AP2300")
      (footprint "SOT-23-3_L2.9-W1.3-P0.95-LS2.4-BR")
      (fields (field (name "BOM_SUPPLIER PART") "C360338") (field (name "CONTRIBUTOR") "LCSC"))
      (libsource (lib "altium-import") (part "root_0_AP2300_"))
    )
    (comp (ref "Q6")
      (value "AP2300")
      (footprint "SOT-23-3_L2.9-W1.3-P0.95-LS2.4-BR")
      (fields (field (name "BOM_SUPPLIER PART") "C360338") (field (name "CONTRIBUTOR") "LCSC"))
      (libsource (lib "altium-import") (part "root_0_AP2300_"))
    )
    (comp (ref "Q7")
      (value "AP2300")
      (footprint "SOT-23-3_L2.9-W1.3-P0.95-LS2.4-BR")
      (fields (field (name "BOM_SUPPLIER PART") "C360338") (field (name "CONTRIBUTOR") "LCSC"))
      (libsource (lib "altium-import") (part "root_0_AP2300_"))
    )
    (comp (ref "Q8")
      (value "AP2300")
      (footprint "SOT-23-3_L2.9-W1.3-P0.95-LS2.4-BR")
      (fields (field (name "BOM_SUPPLIER PART") "C360338") (field (name "CONTRIBUTOR") "LCSC"))
      (libsource (lib "altium-import") (part "root_0_AP2300_"))
    )
    (comp (ref "Q9")
      (value "AP2300")
      (footprint "SOT-23-3_L2.9-W1.3-P0.95-LS2.4-BR")
      (fields (field (name "BOM_SUPPLIER PART") "C360338") (field (name "CONTRIBUTOR") "LCSC"))
      (libsource (lib "altium-import") (part "root_0_AP2300_"))
    )
    (comp (ref "Q10")
      (value "AP2300")
      (footprint "SOT-23-3_L2.9-W1.3-P0.95-LS2.4-BR")
      (fields (field (name "BOM_SUPPLIER PART") "C360338") (field (name "CONTRIBUTOR") "LCSC"))
      (libsource (lib "altium-import") (part "root_0_AP2300_"))
    )
    (comp (ref "Q11")
      (value "AP2300")
      (footprint "SOT-23-3_L2.9-W1.3-P0.95-LS2.4-BR")
      (fields (field (name "BOM_SUPPLIER PART") "C360338") (field (name "CONTRIBUTOR") "LCSC"))
      (libsource (lib "altium-import") (part "root_0_AP2300_"))
    )
    (comp (ref "Q12")
      (value "AP2300")
      (footprint "SOT-23-3_L2.9-W1.3-P0.95-LS2.4-BR")
      (fields (field (name "BOM_SUPPLIER PART") "C360338") (field (name "CONTRIBUTOR") "LCSC"))
      (libsource (lib "altium-import") (part "root_0_AP2300_"))
    )
    (comp (ref "Q13")
      (value "AP2300")
      (footprint "SOT-23-3_L2.9-W1.3-P0.95-LS2.4-BR")
      (fields (field (name "BOM_SUPPLIER PART") "C360338") (field (name "CONTRIBUTOR") "LCSC"))
      (libsource (lib "altium-import") (part "root_0_AP2300_"))
    )
    (comp (ref "Q14")
      (value "AP2300")
      (footprint "SOT-23-3_L2.9-W1.3-P0.95-LS2.4-BR")
      (fields (field (name "BOM_SUPPLIER PART") "C360338") (field (name "CONTRIBUTOR") "LCSC"))
      (libsource (lib "altium-import") (part "root_0_AP2300_"))
    )
    (comp (ref "Q15")
      (value "AP2300")
      (footprint "SOT-23-3_L2.9-W1.3-P0.95-LS2.4-BR")
      (fields (field (name "BOM_SUPPLIER PART") "C360338") (field (name "CONTRIBUTOR") "LCSC"))
      (libsource (lib "altium-import") (part "root_0_AP2300_"))
    )
    (comp (ref "Q16")
      (value "AP2300")
      (footprint "SOT-23-3_L2.9-W1.3-P0.95-LS2.4-BR")
      (fields (field (name "BOM_SUPPLIER PART") "C360338") (field (name "CONTRIBUTOR") "LCSC"))
      (libsource (lib "altium-import") (part "root_0_AP2300_"))
    )
    (comp (ref "Q17")
      (value "AP2300")
      (footprint "SOT-23-3_L2.9-W1.3-P0.95-LS2.4-BR")
      (fields (field (name "BOM_SUPPLIER PART") "C360338") (field (name "CONTRIBUTOR") "LCSC"))
      (libsource (lib "altium-import") (part "root_0_AP2300_"))
    )
    (comp (ref "Q18")
      (value "AP2300")
      (footprint "SOT-23-3_L2.9-W1.3-P0.95-LS2.4-BR")
      (fields (field (name "BOM_SUPPLIER PART") "C360338") (field (name "CONTRIBUTOR") "LCSC"))
      (libsource (lib "altium-import") (part "root_0_AP2300_"))
    )
    (comp (ref "Q19")
      (value "AP2300")
      (footprint "SOT-23-3_L2.9-W1.3-P0.95-LS2.4-BR")
      (fields (field (name "BOM_SUPPLIER PART") "C360338") (field (name "CONTRIBUTOR") "LCSC"))
      (libsource (lib "altium-import") (part "root_0_AP2300_"))
    )
    (comp (ref "Q20")
      (value "AP2300")
      (footprint "SOT-23-3_L2.9-W1.3-P0.95-LS2.4-BR")
      (fields (field (name "BOM_SUPPLIER PART") "C360338") (field (name "CONTRIBUTOR") "LCSC"))
      (libsource (lib "altium-import") (part "root_0_AP2300_"))
    )
    (comp (ref "Q21")
      (value "AP2300")
      (footprint "SOT-23-3_L2.9-W1.3-P0.95-LS2.4-BR")
      (fields (field (name "BOM_SUPPLIER PART") "C360338") (field (name "CONTRIBUTOR") "LCSC"))
      (libsource (lib "altium-import") (part "root_0_AP2300_"))
    )
    (comp (ref "Q22")
      (value "AP2300")
      (footprint "SOT-23-3_L2.9-W1.3-P0.95-LS2.4-BR")
      (fields (field (name "BOM_SUPPLIER PART") "C360338") (field (name "CONTRIBUTOR") "LCSC"))
      (libsource (lib "altium-import") (part "root_0_AP2300_"))
    )
    (comp (ref "Q23")
      (value "AP2300")
      (footprint "SOT-23-3_L2.9-W1.3-P0.95-LS2.4-BR")
      (fields (field (name "BOM_SUPPLIER PART") "C360338") (field (name "CONTRIBUTOR") "LCSC"))
      (libsource (lib "altium-import") (part "root_0_AP2300_"))
    )
    (comp (ref "Q24")
      (value "AP2300")
      (footprint "SOT-23-3_L2.9-W1.3-P0.95-LS2.4-BR")
      (fields (field (name "BOM_SUPPLIER PART") "C360338") (field (name "CONTRIBUTOR") "LCSC"))
      (libsource (lib "altium-import") (part "root_0_AP2300_"))
    )
    (comp (ref "Q25")
      (value "AP2300")
      (footprint "SOT-23-3_L2.9-W1.3-P0.95-LS2.4-BR")
      (fields (field (name "BOM_SUPPLIER PART") "C360338") (field (name "CONTRIBUTOR") "LCSC"))
      (libsource (lib "altium-import") (part "root_0_AP2300_"))
    )
    (comp (ref "Q26")
      (value "AP2300")
      (footprint "SOT-23-3_L2.9-W1.3-P0.95-LS2.4-BR")
      (fields (field (name "BOM_SUPPLIER PART") "C360338") (field (name "CONTRIBUTOR") "LCSC"))
      (libsource (lib "altium-import") (part "root_0_AP2300_"))
    )
    (comp (ref "Q27")
      (value "AP2300")
      (footprint "SOT-23-3_L2.9-W1.3-P0.95-LS2.4-BR")
      (fields (field (name "BOM_SUPPLIER PART") "C360338") (field (name "CONTRIBUTOR") "LCSC"))
      (libsource (lib "altium-import") (part "root_0_AP2300_"))
    )
    (comp (ref "Q28")
      (value "AP2300")
      (footprint "SOT-23-3_L2.9-W1.3-P0.95-LS2.4-BR")
      (fields (field (name "BOM_SUPPLIER PART") "C360338") (field (name "CONTRIBUTOR") "LCSC"))
      (libsource (lib "altium-import") (part "root_0_AP2300_"))
    )
    (comp (ref "Q29")
      (value "AP2300")
      (footprint "SOT-23-3_L2.9-W1.3-P0.95-LS2.4-BR")
      (fields (field (name "BOM_SUPPLIER PART") "C360338") (field (name "CONTRIBUTOR") "LCSC"))
      (libsource (lib "altium-import") (part "root_0_AP2300_"))
    )
    (comp (ref "Q30")
      (value "AP2300")
      (footprint "SOT-23-3_L2.9-W1.3-P0.95-LS2.4-BR")
      (fields (field (name "BOM_SUPPLIER PART") "C360338") (field (name "CONTRIBUTOR") "LCSC"))
      (libsource (lib "altium-import") (part "root_0_AP2300_"))
    )
    (comp (ref "Q31")
      (value "AP2300")
      (footprint "SOT-23-3_L2.9-W1.3-P0.95-LS2.4-BR")
      (fields (field (name "BOM_SUPPLIER PART") "C360338") (field (name "CONTRIBUTOR") "LCSC"))
      (libsource (lib "altium-import") (part "root_0_AP2300_"))
    )
    (comp (ref "Q32")
      (value "AP2300")
      (footprint "SOT-23-3_L2.9-W1.3-P0.95-LS2.4-BR")
      (fields (field (name "BOM_SUPPLIER PART") "C360338") (field (name "CONTRIBUTOR") "LCSC"))
      (libsource (lib "altium-import") (part "root_0_AP2300_"))
    )
    (comp (ref "Q33")
      (value "AP2300")
      (footprint "SOT-23-3_L2.9-W1.3-P0.95-LS2.4-BR")
      (fields (field (name "BOM_SUPPLIER PART") "C360338") (field (name "CONTRIBUTOR") "LCSC"))
      (libsource (lib "altium-import") (part "root_0_AP2300_"))
    )
    (comp (ref "Q34")
      (value "AP2300")
      (footprint "SOT-23-3_L2.9-W1.3-P0.95-LS2.4-BR")
      (fields (field (name "BOM_SUPPLIER PART") "C360338") (field (name "CONTRIBUTOR") "LCSC"))
      (libsource (lib "altium-import") (part "root_0_AP2300_"))
    )
    (comp (ref "Q35")
      (value "AP2300")
      (footprint "SOT-23-3_L2.9-W1.3-P0.95-LS2.4-BR")
      (fields (field (name "BOM_SUPPLIER PART") "C360338") (field (name "CONTRIBUTOR") "LCSC"))
      (libsource (lib "altium-import") (part "root_0_AP2300_"))
    )
    (comp (ref "Q36")
      (value "AP2300")
      (footprint "SOT-23-3_L2.9-W1.3-P0.95-LS2.4-BR")
      (fields (field (name "BOM_SUPPLIER PART") "C360338") (field (name "CONTRIBUTOR") "LCSC"))
      (libsource (lib "altium-import") (part "root_0_AP2300_"))
    )
    (comp (ref "Q37")
      (value "AP2300")
      (footprint "SOT-23-3_L2.9-W1.3-P0.95-LS2.4-BR")
      (fields (field (name "BOM_SUPPLIER PART") "C360338") (field (name "CONTRIBUTOR") "LCSC"))
      (libsource (lib "altium-import") (part "root_0_AP2300_"))
    )
    (comp (ref "Q38")
      (value "AP2300")
      (footprint "SOT-23-3_L2.9-W1.3-P0.95-LS2.4-BR")
      (fields (field (name "BOM_SUPPLIER PART") "C360338") (field (name "CONTRIBUTOR") "LCSC"))
      (libsource (lib "altium-import") (part "root_0_AP2300_"))
    )
    (comp (ref "Q39")
      (value "AP2300")
      (footprint "SOT-23-3_L2.9-W1.3-P0.95-LS2.4-BR")
      (fields (field (name "BOM_SUPPLIER PART") "C360338") (field (name "CONTRIBUTOR") "LCSC"))
      (libsource (lib "altium-import") (part "root_0_AP2300_"))
    )
    (comp (ref "Q40")
      (value "AP2300")
      (footprint "SOT-23-3_L2.9-W1.3-P0.95-LS2.4-BR")
      (fields (field (name "BOM_SUPPLIER PART") "C360338") (field (name "CONTRIBUTOR") "LCSC"))
      (libsource (lib "altium-import") (part "root_0_AP2300_"))
    )
    (comp (ref "Q41")
      (value "AP2300")
      (footprint "SOT-23-3_L2.9-W1.3-P0.95-LS2.4-BR")
      (fields (field (name "BOM_SUPPLIER PART") "C360338") (field (name "CONTRIBUTOR") "LCSC"))
      (libsource (lib "altium-import") (part "root_0_AP2300_"))
    )
    (comp (ref "Q42")
      (value "AP2300")
      (footprint "SOT-23-3_L2.9-W1.3-P0.95-LS2.4-BR")
      (fields (field (name "BOM_SUPPLIER PART") "C360338") (field (name "CONTRIBUTOR") "LCSC"))
      (libsource (lib "altium-import") (part "root_0_AP2300_"))
    )
    (comp (ref "Q43")
      (value "AP2300")
      (footprint "SOT-23-3_L2.9-W1.3-P0.95-LS2.4-BR")
      (fields (field (name "BOM_SUPPLIER PART") "C360338") (field (name "CONTRIBUTOR") "LCSC"))
      (libsource (lib "altium-import") (part "root_0_AP2300_"))
    )
    (comp (ref "Q44")
      (value "AP2300")
      (footprint "SOT-23-3_L2.9-W1.3-P0.95-LS2.4-BR")
      (fields (field (name "BOM_SUPPLIER PART") "C360338") (field (name "CONTRIBUTOR") "LCSC"))
      (libsource (lib "altium-import") (part "root_0_AP2300_"))
    )
    (comp (ref "Q45")
      (value "AP2300")
      (footprint "SOT-23-3_L2.9-W1.3-P0.95-LS2.4-BR")
      (fields (field (name "BOM_SUPPLIER PART") "C360338") (field (name "CONTRIBUTOR") "LCSC"))
      (libsource (lib "altium-import") (part "root_0_AP2300_"))
    )
    (comp (ref "Q46")
      (value "AP2300")
      (footprint "SOT-23-3_L2.9-W1.3-P0.95-LS2.4-BR")
      (fields (field (name "BOM_SUPPLIER PART") "C360338") (field (name "CONTRIBUTOR") "LCSC"))
      (libsource (lib "altium-import") (part "root_0_AP2300_"))
    )
    (comp (ref "Q47")
      (value "AP2300")
      (footprint "SOT-23-3_L2.9-W1.3-P0.95-LS2.4-BR")
      (fields (field (name "BOM_SUPPLIER PART") "C360338") (field (name "CONTRIBUTOR") "LCSC"))
      (libsource (lib "altium-import") (part "root_0_AP2300_"))
    )
    (comp (ref "Q48")
      (value "AP2300")
      (footprint "SOT-23-3_L2.9-W1.3-P0.95-LS2.4-BR")
      (fields (field (name "BOM_SUPPLIER PART") "C360338") (field (name "CONTRIBUTOR") "LCSC"))
      (libsource (lib "altium-import") (part "root_0_AP2300_"))
    )
    (comp (ref "Q49")
      (value "AP2300")
      (footprint "SOT-23-3_L2.9-W1.3-P0.95-LS2.4-BR")
      (fields (field (name "BOM_SUPPLIER PART") "C360338") (field (name "CONTRIBUTOR") "LCSC"))
      (libsource (lib "altium-import") (part "root_0_AP2300_"))
    )
    (comp (ref "Q50")
      (value "AP2300")
      (footprint "SOT-23-3_L2.9-W1.3-P0.95-LS2.4-BR")
      (fields (field (name "BOM_SUPPLIER PART") "C360338") (field (name "CONTRIBUTOR") "LCSC"))
      (libsource (lib "altium-import") (part "root_0_AP2300_"))
    )
    (comp (ref "Q51")
      (value "AP2300")
      (footprint "SOT-23-3_L2.9-W1.3-P0.95-LS2.4-BR")
      (fields (field (name "BOM_SUPPLIER PART") "C360338") (field (name "CONTRIBUTOR") "LCSC"))
      (libsource (lib "altium-import") (part "root_0_AP2300_"))
    )
    (comp (ref "Q52")
      (value "AP2300")
      (footprint "SOT-23-3_L2.9-W1.3-P0.95-LS2.4-BR")
      (fields (field (name "BOM_SUPPLIER PART") "C360338") (field (name "CONTRIBUTOR") "LCSC"))
      (libsource (lib "altium-import") (part "root_0_AP2300_"))
    )
    (comp (ref "Q53")
      (value "AP2300")
      (footprint "SOT-23-3_L2.9-W1.3-P0.95-LS2.4-BR")
      (fields (field (name "BOM_SUPPLIER PART") "C360338") (field (name "CONTRIBUTOR") "LCSC"))
      (libsource (lib "altium-import") (part "root_0_AP2300_"))
    )
    (comp (ref "Q54")
      (value "AP2300")
      (footprint "SOT-23-3_L2.9-W1.3-P0.95-LS2.4-BR")
      (fields (field (name "BOM_SUPPLIER PART") "C360338") (field (name "CONTRIBUTOR") "LCSC"))
      (libsource (lib "altium-import") (part "root_0_AP2300_"))
    )
    (comp (ref "Q55")
      (value "AP2300")
      (footprint "SOT-23-3_L2.9-W1.3-P0.95-LS2.4-BR")
      (fields (field (name "BOM_SUPPLIER PART") "C360338") (field (name "CONTRIBUTOR") "LCSC"))
      (libsource (lib "altium-import") (part "root_0_AP2300_"))
    )
    (comp (ref "Q56")
      (value "AP2300")
      (footprint "SOT-23-3_L2.9-W1.3-P0.95-LS2.4-BR")
      (fields (field (name "BOM_SUPPLIER PART") "C360338") (field (name "CONTRIBUTOR") "LCSC"))
      (libsource (lib "altium-import") (part "root_0_AP2300_"))
    )
    (comp (ref "Q57")
      (value "AP2300")
      (footprint "SOT-23-3_L2.9-W1.3-P0.95-LS2.4-BR")
      (fields (field (name "BOM_SUPPLIER PART") "C360338") (field (name "CONTRIBUTOR") "LCSC"))
      (libsource (lib "altium-import") (part "root_0_AP2300_"))
    )
    (comp (ref "Q58")
      (value "AP2300")
      (footprint "SOT-23-3_L2.9-W1.3-P0.95-LS2.4-BR")
      (fields (field (name "BOM_SUPPLIER PART") "C360338") (field (name "CONTRIBUTOR") "LCSC"))
      (libsource (lib "altium-import") (part "root_0_AP2300_"))
    )
    (comp (ref "Q59")
      (value "AP2300")
      (footprint "SOT-23-3_L2.9-W1.3-P0.95-LS2.4-BR")
      (fields (field (name "BOM_SUPPLIER PART") "C360338") (field (name "CONTRIBUTOR") "LCSC"))
      (libsource (lib "altium-import") (part "root_0_AP2300_"))
    )
    (comp (ref "Q60")
      (value "AP2300")
      (footprint "SOT-23-3_L2.9-W1.3-P0.95-LS2.4-BR")
      (fields (field (name "BOM_SUPPLIER PART") "C360338") (field (name "CONTRIBUTOR") "LCSC"))
      (libsource (lib "altium-import") (part "root_0_AP2300_"))
    )
    (comp (ref "Q61")
      (value "AP2300")
      (footprint "SOT-23-3_L2.9-W1.3-P0.95-LS2.4-BR")
      (fields (field (name "BOM_SUPPLIER PART") "C360338") (field (name "CONTRIBUTOR") "LCSC"))
      (libsource (lib "altium-import") (part "root_0_AP2300_"))
    )
    (comp (ref "Q62")
      (value "AP2300")
      (footprint "SOT-23-3_L2.9-W1.3-P0.95-LS2.4-BR")
      (fields (field (name "BOM_SUPPLIER PART") "C360338") (field (name "CONTRIBUTOR") "LCSC"))
      (libsource (lib "altium-import") (part "root_0_AP2300_"))
    )
    (comp (ref "Q63")
      (value "AP2300")
      (footprint "SOT-23-3_L2.9-W1.3-P0.95-LS2.4-BR")
      (fields (field (name "BOM_SUPPLIER PART") "C360338") (field (name "CONTRIBUTOR") "LCSC"))
      (libsource (lib "altium-import") (part "root_0_AP2300_"))
    )
    (comp (ref "Q64")
      (value "AP2300")
      (footprint "SOT-23-3_L2.9-W1.3-P0.95-LS2.4-BR")
      (fields (field (name "BOM_SUPPLIER PART") "C360338") (field (name "CONTRIBUTOR") "LCSC"))
      (libsource (lib "altium-import") (part "root_0_AP2300_"))
    )
    (comp (ref "Q65")
      (value "AP2300")
      (footprint "SOT-23-3_L2.9-W1.3-P0.95-LS2.4-BR")
      (fields (field (name "BOM_SUPPLIER PART") "C360338") (field (name "CONTRIBUTOR") "LCSC"))
      (libsource (lib "altium-import") (part "root_0_AP2300_"))
    )
    (comp (ref "Q66")
      (value "AP2300")
      (footprint "SOT-23-3_L2.9-W1.3-P0.95-LS2.4-BR")
      (fields (field (name "BOM_SUPPLIER PART") "C360338") (field (name "CONTRIBUTOR") "LCSC"))
      (libsource (lib "altium-import") (part "root_0_AP2300_"))
    )
    (comp (ref "Q67")
      (value "AP2300")
      (footprint "SOT-23-3_L2.9-W1.3-P0.95-LS2.4-BR")
      (fields (field (name "BOM_SUPPLIER PART") "C360338") (field (name "CONTRIBUTOR") "LCSC"))
      (libsource (lib "altium-import") (part "root_0_AP2300_"))
    )
    (comp (ref "Q68")
      (value "AP2300")
      (footprint "SOT-23-3_L2.9-W1.3-P0.95-LS2.4-BR")
      (fields (field (name "BOM_SUPPLIER PART") "C360338") (field (name "CONTRIBUTOR") "LCSC"))
      (libsource (lib "altium-import") (part "root_0_AP2300_"))
    )
    (comp (ref "Q69")
      (value "AP2300")
      (footprint "SOT-23-3_L2.9-W1.3-P0.95-LS2.4-BR")
      (fields (field (name "BOM_SUPPLIER PART") "C360338") (field (name "CONTRIBUTOR") "LCSC"))
      (libsource (lib "altium-import") (part "root_0_AP2300_"))
    )
    (comp (ref "Q70")
      (value "AP2300")
      (footprint "SOT-23-3_L2.9-W1.3-P0.95-LS2.4-BR")
      (fields (field (name "BOM_SUPPLIER PART") "C360338") (field (name "CONTRIBUTOR") "LCSC"))
      (libsource (lib "altium-import") (part "root_0_AP2300_"))
    )
    (comp (ref "Q71")
      (value "AP2300")
      (footprint "SOT-23-3_L2.9-W1.3-P0.95-LS2.4-BR")
      (fields (field (name "BOM_SUPPLIER PART") "C360338") (field (name "CONTRIBUTOR") "LCSC"))
      (libsource (lib "altium-import") (part "root_0_AP2300_"))
    )
    (comp (ref "Q72")
      (value "AP2300")
      (footprint "SOT-23-3_L2.9-W1.3-P0.95-LS2.4-BR")
      (fields (field (name "BOM_SUPPLIER PART") "C360338") (field (name "CONTRIBUTOR") "LCSC"))
      (libsource (lib "altium-import") (part "root_0_AP2300_"))
    )
    (comp (ref "Q73")
      (value "AP2300")
      (footprint "SOT-23-3_L2.9-W1.3-P0.95-LS2.4-BR")
      (fields (field (name "BOM_SUPPLIER PART") "C360338") (field (name "CONTRIBUTOR") "LCSC"))
      (libsource (lib "altium-import") (part "root_0_AP2300_"))
    )
    (comp (ref "Q74")
      (value "AP2300")
      (footprint "SOT-23-3_L2.9-W1.3-P0.95-LS2.4-BR")
      (fields (field (name "BOM_SUPPLIER PART") "C360338") (field (name "CONTRIBUTOR") "LCSC"))
      (libsource (lib "altium-import") (part "root_0_AP2300_"))
    )
    (comp (ref "Q75")
      (value "AP2300")
      (footprint "SOT-23-3_L2.9-W1.3-P0.95-LS2.4-BR")
      (fields (field (name "BOM_SUPPLIER PART") "C360338") (field (name "CONTRIBUTOR") "LCSC"))
      (libsource (lib "altium-import") (part "root_0_AP2300_"))
    )
    (comp (ref "Q76")
      (value "AP2300")
      (footprint "SOT-23-3_L2.9-W1.3-P0.95-LS2.4-BR")
      (fields (field (name "BOM_SUPPLIER PART") "C360338") (field (name "CONTRIBUTOR") "LCSC"))
      (libsource (lib "altium-import") (part "root_0_AP2300_"))
    )
    (comp (ref "Q77")
      (value "AP2300")
      (footprint "SOT-23-3_L2.9-W1.3-P0.95-LS2.4-BR")
      (fields (field (name "BOM_SUPPLIER PART") "C360338") (field (name "CONTRIBUTOR") "LCSC"))
      (libsource (lib "altium-import") (part "root_0_AP2300_"))
    )
    (comp (ref "Q78")
      (value "AP2300")
      (footprint "SOT-23-3_L2.9-W1.3-P0.95-LS2.4-BR")
      (fields (field (name "BOM_SUPPLIER PART") "C360338") (field (name "CONTRIBUTOR") "LCSC"))
      (libsource (lib "altium-import") (part "root_0_AP2300_"))
    )
    (comp (ref "R1")
      (value "10")
      (footprint "R0402")
      (fields (field (name "CONTRIBUTOR") "LCEDA_Lib"))
      (libsource (lib "altium-import") (part "root_0_10_"))
    )
    (comp (ref "R2")
      (value "10")
      (footprint "R0402")
      (fields (field (name "CONTRIBUTOR") "LCEDA_Lib"))
      (libsource (lib "altium-import") (part "root_0_10_"))
    )
    (comp (ref "R3")
      (value "10")
      (footprint "R0402")
      (fields (field (name "CONTRIBUTOR") "LCEDA_Lib"))
      (libsource (lib "altium-import") (part "root_0_10_"))
    )
    (comp (ref "R4")
      (value "10")
      (footprint "R0402")
      (fields (field (name "CONTRIBUTOR") "LCEDA_Lib"))
      (libsource (lib "altium-import") (part "root_0_10_"))
    )
    (comp (ref "R5")
      (value "10")
      (footprint "R0402")
      (fields (field (name "CONTRIBUTOR") "LCEDA_Lib"))
      (libsource (lib "altium-import") (part "root_0_10_"))
    )
    (comp (ref "R6")
      (value "10")
      (footprint "R0402")
      (fields (field (name "CONTRIBUTOR") "LCEDA_Lib"))
      (libsource (lib "altium-import") (part "root_0_10_"))
    )
    (comp (ref "R7")
      (value "10")
      (footprint "R0402")
      (fields (field (name "CONTRIBUTOR") "LCEDA_Lib"))
      (libsource (lib "altium-import") (part "root_0_10_"))
    )
    (comp (ref "R8")
      (value "10")
      (footprint "R0402")
      (fields (field (name "CONTRIBUTOR") "LCEDA_Lib"))
      (libsource (lib "altium-import") (part "root_0_10_"))
    )
    (comp (ref "R9")
      (value "10")
      (footprint "R0402")
      (fields (field (name "CONTRIBUTOR") "LCEDA_Lib"))
      (libsource (lib "altium-import") (part "root_0_10_"))
    )
    (comp (ref "R10")
      (value "10")
      (footprint "R0402")
      (fields (field (name "CONTRIBUTOR") "LCEDA_Lib"))
      (libsource (lib "altium-import") (part "root_0_10_"))
    )
    (comp (ref "R11")
      (value "10")
      (footprint "R0402")
      (fields (field (name "CONTRIBUTOR") "LCEDA_Lib"))
      (libsource (lib "altium-import") (part "root_0_10_"))
    )
    (comp (ref "R12")
      (value "10")
      (footprint "R0402")
      (fields (field (name "CONTRIBUTOR") "LCEDA_Lib"))
      (libsource (lib "altium-import") (part "root_0_10_"))
    )
    (comp (ref "R13")
      (value "10")
      (footprint "R0402")
      (fields (field (name "CONTRIBUTOR") "LCEDA_Lib"))
      (libsource (lib "altium-import") (part "root_0_10_"))
    )
    (comp (ref "R14")
      (value "10")
      (footprint "R0402")
      (fields (field (name "CONTRIBUTOR") "LCEDA_Lib"))
      (libsource (lib "altium-import") (part "root_0_10_"))
    )
    (comp (ref "R15")
      (value "10")
      (footprint "R0402")
      (fields (field (name "CONTRIBUTOR") "LCEDA_Lib"))
      (libsource (lib "altium-import") (part "root_0_10_"))
    )
    (comp (ref "R16")
      (value "10")
      (footprint "R0402")
      (fields (field (name "CONTRIBUTOR") "LCEDA_Lib"))
      (libsource (lib "altium-import") (part "root_0_10_"))
    )
    (comp (ref "R17")
      (value "10")
      (footprint "R0402")
      (fields (field (name "CONTRIBUTOR") "LCEDA_Lib"))
      (libsource (lib "altium-import") (part "root_0_10_"))
    )
    (comp (ref "R18")
      (value "10")
      (footprint "R0402")
      (fields (field (name "CONTRIBUTOR") "LCEDA_Lib"))
      (libsource (lib "altium-import") (part "root_0_10_"))
    )
    (comp (ref "R19")
      (value "10")
      (footprint "R0402")
      (fields (field (name "CONTRIBUTOR") "LCEDA_Lib"))
      (libsource (lib "altium-import") (part "root_0_10_"))
    )
    (comp (ref "R20")
      (value "10")
      (footprint "R0402")
      (fields (field (name "CONTRIBUTOR") "LCEDA_Lib"))
      (libsource (lib "altium-import") (part "root_0_10_"))
    )
    (comp (ref "R21")
      (value "10")
      (footprint "R0402")
      (fields (field (name "CONTRIBUTOR") "LCEDA_Lib"))
      (libsource (lib "altium-import") (part "root_0_10_"))
    )
    (comp (ref "R22")
      (value "10")
      (footprint "R0402")
      (fields (field (name "CONTRIBUTOR") "LCEDA_Lib"))
      (libsource (lib "altium-import") (part "root_0_10_"))
    )
    (comp (ref "R23")
      (value "10")
      (footprint "R0402")
      (fields (field (name "CONTRIBUTOR") "LCEDA_Lib"))
      (libsource (lib "altium-import") (part "root_0_10_"))
    )
    (comp (ref "R24")
      (value "10")
      (footprint "R0402")
      (fields (field (name "CONTRIBUTOR") "LCEDA_Lib"))
      (libsource (lib "altium-import") (part "root_0_10_"))
    )
    (comp (ref "R25")
      (value "10")
      (footprint "R0402")
      (fields (field (name "CONTRIBUTOR") "LCEDA_Lib"))
      (libsource (lib "altium-import") (part "root_0_10_"))
    )
    (comp (ref "R26")
      (value "10")
      (footprint "R0402")
      (fields (field (name "CONTRIBUTOR") "LCEDA_Lib"))
      (libsource (lib "altium-import") (part "root_0_10_"))
    )
    (comp (ref "R27")
      (value "10")
      (footprint "R0402")
      (fields (field (name "CONTRIBUTOR") "LCEDA_Lib"))
      (libsource (lib "altium-import") (part "root_0_10_"))
    )
    (comp (ref "R28")
      (value "10")
      (footprint "R0402")
      (fields (field (name "CONTRIBUTOR") "LCEDA_Lib"))
      (libsource (lib "altium-import") (part "root_0_10_"))
    )
    (comp (ref "R29")
      (value "10")
      (footprint "R0402")
      (fields (field (name "CONTRIBUTOR") "LCEDA_Lib"))
      (libsource (lib "altium-import") (part "root_0_10_"))
    )
    (comp (ref "R30")
      (value "10")
      (footprint "R0402")
      (fields (field (name "CONTRIBUTOR") "LCEDA_Lib"))
      (libsource (lib "altium-import") (part "root_0_10_"))
    )
    (comp (ref "R31")
      (value "10")
      (footprint "R0402")
      (fields (field (name "CONTRIBUTOR") "LCEDA_Lib"))
      (libsource (lib "altium-import") (part "root_0_10_"))
    )
    (comp (ref "R32")
      (value "10")
      (footprint "R0402")
      (fields (field (name "CONTRIBUTOR") "LCEDA_Lib"))
      (libsource (lib "altium-import") (part "root_0_10_"))
    )
    (comp (ref "R33")
      (value "10")
      (footprint "R0402")
      (fields (field (name "CONTRIBUTOR") "LCEDA_Lib"))
      (libsource (lib "altium-import") (part "root_0_10_"))
    )
    (comp (ref "R34")
      (value "10")
      (footprint "R0402")
      (fields (field (name "CONTRIBUTOR") "LCEDA_Lib"))
      (libsource (lib "altium-import") (part "root_0_10_"))
    )
    (comp (ref "R35")
      (value "10")
      (footprint "R0402")
      (fields (field (name "CONTRIBUTOR") "LCEDA_Lib"))
      (libsource (lib "altium-import") (part "root_0_10_"))
    )
    (comp (ref "R36")
      (value "10")
      (footprint "R0402")
      (fields (field (name "CONTRIBUTOR") "LCEDA_Lib"))
      (libsource (lib "altium-import") (part "root_0_10_"))
    )
    (comp (ref "R37")
      (value "10")
      (footprint "R0402")
      (fields (field (name "CONTRIBUTOR") "LCEDA_Lib"))
      (libsource (lib "altium-import") (part "root_0_10_"))
    )
    (comp (ref "R38")
      (value "10")
      (footprint "R0402")
      (fields (field (name "CONTRIBUTOR") "LCEDA_Lib"))
      (libsource (lib "altium-import") (part "root_0_10_"))
    )
    (comp (ref "R39")
      (value "10")
      (footprint "R0402")
      (fields (field (name "CONTRIBUTOR") "LCEDA_Lib"))
      (libsource (lib "altium-import") (part "root_0_10_"))
    )
    (comp (ref "R40")
      (value "10")
      (footprint "R0402")
      (fields (field (name "CONTRIBUTOR") "LCEDA_Lib"))
      (libsource (lib "altium-import") (part "root_0_10_"))
    )
    (comp (ref "R41")
      (value "10")
      (footprint "R0402")
      (fields (field (name "CONTRIBUTOR") "LCEDA_Lib"))
      (libsource (lib "altium-import") (part "root_0_10_"))
    )
    (comp (ref "R42")
      (value "10")
      (footprint "R0402")
      (fields (field (name "CONTRIBUTOR") "LCEDA_Lib"))
      (libsource (lib "altium-import") (part "root_0_10_"))
    )
    (comp (ref "R43")
      (value "10")
      (footprint "R0402")
      (fields (field (name "CONTRIBUTOR") "LCEDA_Lib"))
      (libsource (lib "altium-import") (part "root_0_10_"))
    )
    (comp (ref "R44")
      (value "10")
      (footprint "R0402")
      (fields (field (name "CONTRIBUTOR") "LCEDA_Lib"))
      (libsource (lib "altium-import") (part "root_0_10_"))
    )
    (comp (ref "R45")
      (value "10")
      (footprint "R0402")
      (fields (field (name "CONTRIBUTOR") "LCEDA_Lib"))
      (libsource (lib "altium-import") (part "root_0_10_"))
    )
    (comp (ref "R46")
      (value "10")
      (footprint "R0402")
      (fields (field (name "CONTRIBUTOR") "LCEDA_Lib"))
      (libsource (lib "altium-import") (part "root_0_10_"))
    )
    (comp (ref "R47")
      (value "10")
      (footprint "R0402")
      (fields (field (name "CONTRIBUTOR") "LCEDA_Lib"))
      (libsource (lib "altium-import") (part "root_0_10_"))
    )
    (comp (ref "R48")
      (value "10")
      (footprint "R0402")
      (fields (field (name "CONTRIBUTOR") "LCEDA_Lib"))
      (libsource (lib "altium-import") (part "root_0_10_"))
    )
    (comp (ref "R49")
      (value "10")
      (footprint "R0402")
      (fields (field (name "CONTRIBUTOR") "LCEDA_Lib"))
      (libsource (lib "altium-import") (part "root_0_10_"))
    )
    (comp (ref "R50")
      (value "10")
      (footprint "R0402")
      (fields (field (name "CONTRIBUTOR") "LCEDA_Lib"))
      (libsource (lib "altium-import") (part "root_0_10_"))
    )
    (comp (ref "R51")
      (value "10")
      (footprint "R0402")
      (fields (field (name "CONTRIBUTOR") "LCEDA_Lib"))
      (libsource (lib "altium-import") (part "root_0_10_"))
    )
    (comp (ref "R52")
      (value "10")
      (footprint "R0402")
      (fields (field (name "CONTRIBUTOR") "LCEDA_Lib"))
      (libsource (lib "altium-import") (part "root_0_10_"))
    )
    (comp (ref "R53")
      (value "10")
      (footprint "R0402")
      (fields (field (name "CONTRIBUTOR") "LCEDA_Lib"))
      (libsource (lib "altium-import") (part "root_0_10_"))
    )
    (comp (ref "R54")
      (value "10")
      (footprint "R0402")
      (fields (field (name "CONTRIBUTOR") "LCEDA_Lib"))
      (libsource (lib "altium-import") (part "root_0_10_"))
    )
    (comp (ref "R55")
      (value "10")
      (footprint "R0402")
      (fields (field (name "CONTRIBUTOR") "LCEDA_Lib"))
      (libsource (lib "altium-import") (part "root_0_10_"))
    )
    (comp (ref "R56")
      (value "10")
      (footprint "R0402")
      (fields (field (name "CONTRIBUTOR") "LCEDA_Lib"))
      (libsource (lib "altium-import") (part "root_0_10_"))
    )
    (comp (ref "R57")
      (value "10")
      (footprint "R0402")
      (fields (field (name "CONTRIBUTOR") "LCEDA_Lib"))
      (libsource (lib "altium-import") (part "root_0_10_"))
    )
    (comp (ref "R58")
      (value "10")
      (footprint "R0402")
      (fields (field (name "CONTRIBUTOR") "LCEDA_Lib"))
      (libsource (lib "altium-import") (part "root_0_10_"))
    )
    (comp (ref "R59")
      (value "10")
      (footprint "R0402")
      (fields (field (name "CONTRIBUTOR") "LCEDA_Lib"))
      (libsource (lib "altium-import") (part "root_0_10_"))
    )
    (comp (ref "R60")
      (value "10")
      (footprint "R0402")
      (fields (field (name "CONTRIBUTOR") "LCEDA_Lib"))
      (libsource (lib "altium-import") (part "root_0_10_"))
    )
    (comp (ref "R61")
      (value "10")
      (footprint "R0402")
      (fields (field (name "CONTRIBUTOR") "LCEDA_Lib"))
      (libsource (lib "altium-import") (part "root_0_10_"))
    )
    (comp (ref "R62")
      (value "10")
      (footprint "R0402")
      (fields (field (name "CONTRIBUTOR") "LCEDA_Lib"))
      (libsource (lib "altium-import") (part "root_0_10_"))
    )
    (comp (ref "R63")
      (value "10")
      (footprint "R0402")
      (fields (field (name "CONTRIBUTOR") "LCEDA_Lib"))
      (libsource (lib "altium-import") (part "root_0_10_"))
    )
    (comp (ref "R64")
      (value "10")
      (footprint "R0402")
      (fields (field (name "CONTRIBUTOR") "LCEDA_Lib"))
      (libsource (lib "altium-import") (part "root_0_10_"))
    )
    (comp (ref "R65")
      (value "10")
      (footprint "R0402")
      (fields (field (name "CONTRIBUTOR") "LCEDA_Lib"))
      (libsource (lib "altium-import") (part "root_0_10_"))
    )
    (comp (ref "R66")
      (value "10")
      (footprint "R0402")
      (fields (field (name "CONTRIBUTOR") "LCEDA_Lib"))
      (libsource (lib "altium-import") (part "root_0_10_"))
    )
    (comp (ref "R67")
      (value "10")
      (footprint "R0402")
      (fields (field (name "CONTRIBUTOR") "LCEDA_Lib"))
      (libsource (lib "altium-import") (part "root_0_10_"))
    )
    (comp (ref "R68")
      (value "10")
      (footprint "R0402")
      (fields (field (name "CONTRIBUTOR") "LCEDA_Lib"))
      (libsource (lib "altium-import") (part "root_0_10_"))
    )
    (comp (ref "R69")
      (value "10")
      (footprint "R0402")
      (fields (field (name "CONTRIBUTOR") "LCEDA_Lib"))
      (libsource (lib "altium-import") (part "root_0_10_"))
    )
    (comp (ref "R70")
      (value "10")
      (footprint "R0402")
      (fields (field (name "CONTRIBUTOR") "LCEDA_Lib"))
      (libsource (lib "altium-import") (part "root_0_10_"))
    )
    (comp (ref "R71")
      (value "10")
      (footprint "R0402")
      (fields (field (name "CONTRIBUTOR") "LCEDA_Lib"))
      (libsource (lib "altium-import") (part "root_0_10_"))
    )
    (comp (ref "R72")
      (value "10")
      (footprint "R0402")
      (fields (field (name "CONTRIBUTOR") "LCEDA_Lib"))
      (libsource (lib "altium-import") (part "root_0_10_"))
    )
    (comp (ref "R73")
      (value "10")
      (footprint "R0402")
      (fields (field (name "CONTRIBUTOR") "LCEDA_Lib"))
      (libsource (lib "altium-import") (part "root_0_10_"))
    )
    (comp (ref "R74")
      (value "10")
      (footprint "R0402")
      (fields (field (name "CONTRIBUTOR") "LCEDA_Lib"))
      (libsource (lib "altium-import") (part "root_0_10_"))
    )
    (comp (ref "R75")
      (value "10")
      (footprint "R0402")
      (fields (field (name "CONTRIBUTOR") "LCEDA_Lib"))
      (libsource (lib "altium-import") (part "root_0_10_"))
    )
    (comp (ref "R76")
      (value "10")
      (footprint "R0402")
      (fields (field (name "CONTRIBUTOR") "LCEDA_Lib"))
      (libsource (lib "altium-import") (part "root_0_10_"))
    )
    (comp (ref "R77")
      (value "10")
      (footprint "R0402")
      (fields (field (name "CONTRIBUTOR") "LCEDA_Lib"))
      (libsource (lib "altium-import") (part "root_0_10_"))
    )
    (comp (ref "R78")
      (value "10")
      (footprint "R0402")
      (fields (field (name "CONTRIBUTOR") "LCEDA_Lib"))
      (libsource (lib "altium-import") (part "root_0_10_"))
    )
    (comp (ref "U1")
      (value "EG2133")
      (footprint "TSSOP-20_L6.5-W4.4-P0.65-LS6.4-BL")
      (fields (field (name "BOM_SUPPLIER PART") "C190343") (field (name "CONTRIBUTOR") "LCSC"))
      (libsource (lib "altium-import") (part "root_0_EG2133_"))
    )
    (comp (ref "U2")
      (value "EG2133")
      (footprint "TSSOP-20_L6.5-W4.4-P0.65-LS6.4-BL")
      (fields (field (name "BOM_SUPPLIER PART") "C190343") (field (name "CONTRIBUTOR") "LCSC"))
      (libsource (lib "altium-import") (part "root_0_EG2133_"))
    )
    (comp (ref "U3")
      (value "EG2133")
      (footprint "TSSOP-20_L6.5-W4.4-P0.65-LS6.4-BL")
      (fields (field (name "BOM_SUPPLIER PART") "C190343") (field (name "CONTRIBUTOR") "LCSC"))
      (libsource (lib "altium-import") (part "root_0_EG2133_"))
    )
    (comp (ref "U4")
      (value "EG2133")
      (footprint "TSSOP-20_L6.5-W4.4-P0.65-LS6.4-BL")
      (fields (field (name "BOM_SUPPLIER PART") "C190343") (field (name "CONTRIBUTOR") "LCSC"))
      (libsource (lib "altium-import") (part "root_0_EG2133_"))
    )
    (comp (ref "U5")
      (value "EG2133")
      (footprint "TSSOP-20_L6.5-W4.4-P0.65-LS6.4-BL")
      (fields (field (name "BOM_SUPPLIER PART") "C190343") (field (name "CONTRIBUTOR") "LCSC"))
      (libsource (lib "altium-import") (part "root_0_EG2133_"))
    )
    (comp (ref "U6")
      (value "EG2133")
      (footprint "TSSOP-20_L6.5-W4.4-P0.65-LS6.4-BL")
      (fields (field (name "BOM_SUPPLIER PART") "C190343") (field (name "CONTRIBUTOR") "LCSC"))
      (libsource (lib "altium-import") (part "root_0_EG2133_"))
    )
    (comp (ref "U7")
      (value "EG2133")
      (footprint "TSSOP-20_L6.5-W4.4-P0.65-LS6.4-BL")
      (fields (field (name "BOM_SUPPLIER PART") "C190343") (field (name "CONTRIBUTOR") "LCSC"))
      (libsource (lib "altium-import") (part "root_0_EG2133_"))
    )
    (comp (ref "U8")
      (value "EG2133")
      (footprint "TSSOP-20_L6.5-W4.4-P0.65-LS6.4-BL")
      (fields (field (name "BOM_SUPPLIER PART") "C190343") (field (name "CONTRIBUTOR") "LCSC"))
      (libsource (lib "altium-import") (part "root_0_EG2133_"))
    )
    (comp (ref "U9")
      (value "EG2133")
      (footprint "TSSOP-20_L6.5-W4.4-P0.65-LS6.4-BL")
      (fields (field (name "BOM_SUPPLIER PART") "C190343") (field (name "CONTRIBUTOR") "LCSC"))
      (libsource (lib "altium-import") (part "root_0_EG2133_"))
    )
    (comp (ref "U10")
      (value "EG2133")
      (footprint "TSSOP-20_L6.5-W4.4-P0.65-LS6.4-BL")
      (fields (field (name "BOM_SUPPLIER PART") "C190343") (field (name "CONTRIBUTOR") "LCSC"))
      (libsource (lib "altium-import") (part "root_0_EG2133_"))
    )
    (comp (ref "U11")
      (value "EG2133")
      (footprint "TSSOP-20_L6.5-W4.4-P0.65-LS6.4-BL")
      (fields (field (name "BOM_SUPPLIER PART") "C190343") (field (name "CONTRIBUTOR") "LCSC"))
      (libsource (lib "altium-import") (part "root_0_EG2133_"))
    )
    (comp (ref "U12")
      (value "EG2133")
      (footprint "TSSOP-20_L6.5-W4.4-P0.65-LS6.4-BL")
      (fields (field (name "BOM_SUPPLIER PART") "C190343") (field (name "CONTRIBUTOR") "LCSC"))
      (libsource (lib "altium-import") (part "root_0_EG2133_"))
    )
    (comp (ref "U13")
      (value "WAFER-XH2.54-2PLB")
      (footprint "CONN-SMD_2P-P2.50_XUNPU_WAFER-XH2.54-2PLB")
      (fields (field (name "BOM_SUPPLIER PART") "C3029467") (field (name "CONTRIBUTOR") "lcsc"))
      (libsource (lib "altium-import") (part "root_2_WAFER-XH2.54-2PLB_"))
    )
    (comp (ref "U14")
      (value "EG2133")
      (footprint "TSSOP-20_L6.5-W4.4-P0.65-LS6.4-BL")
      (fields (field (name "BOM_SUPPLIER PART") "C190343") (field (name "CONTRIBUTOR") "LCSC"))
      (libsource (lib "altium-import") (part "root_0_EG2133_"))
    )
  )
  (nets
    (net (code "1") (name "/HO1_1") (class "Default")
      (node (ref "D5") (pin "1") (pinfunction "C_1") (pintype "passive"))
      (node (ref "R1") (pin "1") (pinfunction "1_1") (pintype "passive"))
      (node (ref "U1") (pin "19") (pinfunction "HO1_19") (pintype "passive"))
    )
    (net (code "2") (name "/HO1_2") (class "Default")
      (node (ref "D7") (pin "1") (pinfunction "C_1") (pintype "passive"))
      (node (ref "R4") (pin "1") (pinfunction "1_1") (pintype "passive"))
      (node (ref "U1") (pin "16") (pinfunction "HO2_16") (pintype "passive"))
    )
    (net (code "3") (name "/HO1_3") (class "Default")
      (node (ref "D9") (pin "1") (pinfunction "C_1") (pintype "passive"))
      (node (ref "R6") (pin "1") (pinfunction "1_1") (pintype "passive"))
      (node (ref "U1") (pin "13") (pinfunction "HO3_13") (pintype "passive"))
    )
    (net (code "4") (name "/HO2_1") (class "Default")
      (node (ref "D15") (pin "1") (pinfunction "C_1") (pintype "passive"))
      (node (ref "R12") (pin "1") (pinfunction "1_1") (pintype "passive"))
      (node (ref "U2") (pin "19") (pinfunction "HO1_19") (pintype "passive"))
    )
    (net (code "5") (name "/HO2_2") (class "Default")
      (node (ref "D12") (pin "1") (pinfunction "C_1") (pintype "passive"))
      (node (ref "R9") (pin "1") (pinfunction "1_1") (pintype "passive"))
      (node (ref "U2") (pin "16") (pinfunction "HO2_16") (pintype "passive"))
    )
    (net (code "6") (name "/HO2_3") (class "Default")
      (node (ref "D10") (pin "1") (pinfunction "C_1") (pintype "passive"))
      (node (ref "R7") (pin "1") (pinfunction "1_1") (pintype "passive"))
      (node (ref "U2") (pin "13") (pinfunction "HO3_13") (pintype "passive"))
    )
    (net (code "7") (name "/HO3_1") (class "Default")
      (node (ref "D24") (pin "1") (pinfunction "C_1") (pintype "passive"))
      (node (ref "R18") (pin "1") (pinfunction "1_1") (pintype "passive"))
      (node (ref "U3") (pin "19") (pinfunction "HO1_19") (pintype "passive"))
    )
    (net (code "8") (name "/HO3_2") (class "Default")
      (node (ref "D21") (pin "1") (pinfunction "C_1") (pintype "passive"))
      (node (ref "R15") (pin "1") (pinfunction "1_1") (pintype "passive"))
      (node (ref "U3") (pin "16") (pinfunction "HO2_16") (pintype "passive"))
    )
    (net (code "9") (name "/HO3_3") (class "Default")
      (node (ref "D19") (pin "1") (pinfunction "C_1") (pintype "passive"))
      (node (ref "R13") (pin "1") (pinfunction "1_1") (pintype "passive"))
      (node (ref "U3") (pin "13") (pinfunction "HO3_13") (pintype "passive"))
    )
    (net (code "10") (name "/HO4_1") (class "Default")
      (node (ref "D51") (pin "1") (pinfunction "C_1") (pintype "passive"))
      (node (ref "R36") (pin "1") (pinfunction "1_1") (pintype "passive"))
      (node (ref "U6") (pin "19") (pinfunction "HO1_19") (pintype "passive"))
    )
    (net (code "11") (name "/HO4_2") (class "Default")
      (node (ref "D48") (pin "1") (pinfunction "C_1") (pintype "passive"))
      (node (ref "R33") (pin "1") (pinfunction "1_1") (pintype "passive"))
      (node (ref "U6") (pin "16") (pinfunction "HO2_16") (pintype "passive"))
    )
    (net (code "12") (name "/HO4_3") (class "Default")
      (node (ref "D46") (pin "1") (pinfunction "C_1") (pintype "passive"))
      (node (ref "R31") (pin "1") (pinfunction "1_1") (pintype "passive"))
      (node (ref "U6") (pin "13") (pinfunction "HO3_13") (pintype "passive"))
    )
    (net (code "13") (name "/HO5_1") (class "Default")
      (node (ref "D40") (pin "1") (pinfunction "C_1") (pintype "passive"))
      (node (ref "R25") (pin "1") (pinfunction "1_1") (pintype "passive"))
      (node (ref "U5") (pin "19") (pinfunction "HO1_19") (pintype "passive"))
    )
    (net (code "14") (name "/HO5_2") (class "Default")
      (node (ref "D43") (pin "1") (pinfunction "C_1") (pintype "passive"))
      (node (ref "R28") (pin "1") (pinfunction "1_1") (pintype "passive"))
      (node (ref "U5") (pin "16") (pinfunction "HO2_16") (pintype "passive"))
    )
    (net (code "15") (name "/HO5_3") (class "Default")
      (node (ref "D45") (pin "1") (pinfunction "C_1") (pintype "passive"))
      (node (ref "R30") (pin "1") (pinfunction "1_1") (pintype "passive"))
      (node (ref "U5") (pin "13") (pinfunction "HO3_13") (pintype "passive"))
    )
    (net (code "16") (name "/HO6_1") (class "Default")
      (node (ref "D31") (pin "1") (pinfunction "C_1") (pintype "passive"))
      (node (ref "R19") (pin "1") (pinfunction "1_1") (pintype "passive"))
      (node (ref "U4") (pin "19") (pinfunction "HO1_19") (pintype "passive"))
    )
    (net (code "17") (name "/HO6_2") (class "Default")
      (node (ref "D34") (pin "1") (pinfunction "C_1") (pintype "passive"))
      (node (ref "R22") (pin "1") (pinfunction "1_1") (pintype "passive"))
      (node (ref "U4") (pin "16") (pinfunction "HO2_16") (pintype "passive"))
    )
    (net (code "18") (name "/HO6_3") (class "Default")
      (node (ref "D36") (pin "1") (pinfunction "C_1") (pintype "passive"))
      (node (ref "R24") (pin "1") (pinfunction "1_1") (pintype "passive"))
      (node (ref "U4") (pin "13") (pinfunction "HO3_13") (pintype "passive"))
    )
    (net (code "19") (name "/HO7_1") (class "Default")
      (node (ref "D105") (pin "1") (pinfunction "C_1") (pintype "passive"))
      (node (ref "R72") (pin "1") (pinfunction "1_1") (pintype "passive"))
      (node (ref "U12") (pin "19") (pinfunction "HO1_19") (pintype "passive"))
    )
    (net (code "20") (name "/HO7_2") (class "Default")
      (node (ref "D102") (pin "1") (pinfunction "C_1") (pintype "passive"))
      (node (ref "R69") (pin "1") (pinfunction "1_1") (pintype "passive"))
      (node (ref "U12") (pin "16") (pinfunction "HO2_16") (pintype "passive"))
    )
    (net (code "21") (name "/HO7_3") (class "Default")
      (node (ref "D100") (pin "1") (pinfunction "C_1") (pintype "passive"))
      (node (ref "R67") (pin "1") (pinfunction "1_1") (pintype "passive"))
      (node (ref "U12") (pin "13") (pinfunction "HO3_13") (pintype "passive"))
    )
    (net (code "22") (name "/HO8_1") (class "Default")
      (node (ref "D94") (pin "1") (pinfunction "C_1") (pintype "passive"))
      (node (ref "R61") (pin "1") (pinfunction "1_1") (pintype "passive"))
      (node (ref "U11") (pin "19") (pinfunction "HO1_19") (pintype "passive"))
    )
    (net (code "23") (name "/HO8_2") (class "Default")
      (node (ref "D97") (pin "1") (pinfunction "C_1") (pintype "passive"))
      (node (ref "R64") (pin "1") (pinfunction "1_1") (pintype "passive"))
      (node (ref "U11") (pin "16") (pinfunction "HO2_16") (pintype "passive"))
    )
    (net (code "24") (name "/HO8_3") (class "Default")
      (node (ref "D99") (pin "1") (pinfunction "C_1") (pintype "passive"))
      (node (ref "R66") (pin "1") (pinfunction "1_1") (pintype "passive"))
      (node (ref "U11") (pin "13") (pinfunction "HO3_13") (pintype "passive"))
    )
    (net (code "25") (name "/HO9_1") (class "Default")
      (node (ref "D85") (pin "1") (pinfunction "C_1") (pintype "passive"))
      (node (ref "R55") (pin "1") (pinfunction "1_1") (pintype "passive"))
      (node (ref "U10") (pin "19") (pinfunction "HO1_19") (pintype "passive"))
    )
    (net (code "26") (name "/HO9_2") (class "Default")
      (node (ref "D88") (pin "1") (pinfunction "C_1") (pintype "passive"))
      (node (ref "R58") (pin "1") (pinfunction "1_1") (pintype "passive"))
      (node (ref "U10") (pin "16") (pinfunction "HO2_16") (pintype "passive"))
    )
    (net (code "27") (name "/HO9_3") (class "Default")
      (node (ref "D90") (pin "1") (pinfunction "C_1") (pintype "passive"))
      (node (ref "R60") (pin "1") (pinfunction "1_1") (pintype "passive"))
      (node (ref "U10") (pin "13") (pinfunction "HO3_13") (pintype "passive"))
    )
    (net (code "28") (name "/HO10_1") (class "Default")
      (node (ref "D58") (pin "1") (pinfunction "C_1") (pintype "passive"))
      (node (ref "R37") (pin "1") (pinfunction "1_1") (pintype "passive"))
      (node (ref "U7") (pin "19") (pinfunction "HO1_19") (pintype "passive"))
    )
    (net (code "29") (name "/HO10_2") (class "Default")
      (node (ref "D61") (pin "1") (pinfunction "C_1") (pintype "passive"))
      (node (ref "R40") (pin "1") (pinfunction "1_1") (pintype "passive"))
      (node (ref "U7") (pin "16") (pinfunction "HO2_16") (pintype "passive"))
    )
    (net (code "30") (name "/HO10_3") (class "Default")
      (node (ref "D63") (pin "1") (pinfunction "C_1") (pintype "passive"))
      (node (ref "R42") (pin "1") (pinfunction "1_1") (pintype "passive"))
      (node (ref "U7") (pin "13") (pinfunction "HO3_13") (pintype "passive"))
    )
    (net (code "31") (name "/HO11_1") (class "Default")
      (node (ref "D69") (pin "1") (pinfunction "C_1") (pintype "passive"))
      (node (ref "R48") (pin "1") (pinfunction "1_1") (pintype "passive"))
      (node (ref "U8") (pin "19") (pinfunction "HO1_19") (pintype "passive"))
    )
    (net (code "32") (name "/HO11_2") (class "Default")
      (node (ref "D66") (pin "1") (pinfunction "C_1") (pintype "passive"))
      (node (ref "R45") (pin "1") (pinfunction "1_1") (pintype "passive"))
      (node (ref "U8") (pin "16") (pinfunction "HO2_16") (pintype "passive"))
    )
    (net (code "33") (name "/HO11_3") (class "Default")
      (node (ref "D64") (pin "1") (pinfunction "C_1") (pintype "passive"))
      (node (ref "R43") (pin "1") (pinfunction "1_1") (pintype "passive"))
      (node (ref "U8") (pin "13") (pinfunction "HO3_13") (pintype "passive"))
    )
    (net (code "34") (name "/HO12_1") (class "Default")
      (node (ref "D78") (pin "1") (pinfunction "C_1") (pintype "passive"))
      (node (ref "R54") (pin "1") (pinfunction "1_1") (pintype "passive"))
      (node (ref "U9") (pin "19") (pinfunction "HO1_19") (pintype "passive"))
    )
    (net (code "35") (name "/HO12_2") (class "Default")
      (node (ref "D75") (pin "1") (pinfunction "C_1") (pintype "passive"))
      (node (ref "R51") (pin "1") (pinfunction "1_1") (pintype "passive"))
      (node (ref "U9") (pin "16") (pinfunction "HO2_16") (pintype "passive"))
    )
    (net (code "36") (name "/HO12_3") (class "Default")
      (node (ref "D73") (pin "1") (pinfunction "C_1") (pintype "passive"))
      (node (ref "R49") (pin "1") (pinfunction "1_1") (pintype "passive"))
      (node (ref "U9") (pin "13") (pinfunction "HO3_13") (pintype "passive"))
    )
    (net (code "37") (name "/HO13_1") (class "Default")
      (node (ref "D112") (pin "1") (pinfunction "C_1") (pintype "passive"))
      (node (ref "R73") (pin "1") (pinfunction "1_1") (pintype "passive"))
      (node (ref "U14") (pin "19") (pinfunction "HO1_19") (pintype "passive"))
    )
    (net (code "38") (name "/HO13_2") (class "Default")
      (node (ref "D115") (pin "1") (pinfunction "C_1") (pintype "passive"))
      (node (ref "R76") (pin "1") (pinfunction "1_1") (pintype "passive"))
      (node (ref "U14") (pin "16") (pinfunction "HO2_16") (pintype "passive"))
    )
    (net (code "39") (name "/HO13_3") (class "Default")
      (node (ref "D117") (pin "1") (pinfunction "C_1") (pintype "passive"))
      (node (ref "R78") (pin "1") (pinfunction "1_1") (pintype "passive"))
      (node (ref "U14") (pin "13") (pinfunction "HO3_13") (pintype "passive"))
    )
    (net (code "40") (name "/LO1_1") (class "Default")
      (node (ref "D4") (pin "1") (pinfunction "C_1") (pintype "passive"))
      (node (ref "R2") (pin "1") (pinfunction "1_1") (pintype "passive"))
      (node (ref "U1") (pin "11") (pinfunction "LO1_11") (pintype "passive"))
    )
    (net (code "41") (name "/LO1_2") (class "Default")
      (node (ref "D6") (pin "1") (pinfunction "C_1") (pintype "passive"))
      (node (ref "R3") (pin "1") (pinfunction "1_1") (pintype "passive"))
      (node (ref "U1") (pin "10") (pinfunction "LO2_10") (pintype "passive"))
    )
    (net (code "42") (name "/LO1_3") (class "Default")
      (node (ref "D8") (pin "1") (pinfunction "C_1") (pintype "passive"))
      (node (ref "R5") (pin "1") (pinfunction "1_1") (pintype "passive"))
      (node (ref "U1") (pin "9") (pinfunction "LO3_9") (pintype "passive"))
    )
    (net (code "43") (name "/LO2_1") (class "Default")
      (node (ref "D14") (pin "1") (pinfunction "C_1") (pintype "passive"))
      (node (ref "R11") (pin "1") (pinfunction "1_1") (pintype "passive"))
      (node (ref "U2") (pin "11") (pinfunction "LO1_11") (pintype "passive"))
    )
    (net (code "44") (name "/LO2_2") (class "Default")
      (node (ref "D13") (pin "1") (pinfunction "C_1") (pintype "passive"))
      (node (ref "R10") (pin "1") (pinfunction "1_1") (pintype "passive"))
      (node (ref "U2") (pin "10") (pinfunction "LO2_10") (pintype "passive"))
    )
    (net (code "45") (name "/LO2_3") (class "Default")
      (node (ref "D11") (pin "1") (pinfunction "C_1") (pintype "passive"))
      (node (ref "R8") (pin "1") (pinfunction "1_1") (pintype "passive"))
      (node (ref "U2") (pin "9") (pinfunction "LO3_9") (pintype "passive"))
    )
    (net (code "46") (name "/LO3_1") (class "Default")
      (node (ref "D23") (pin "1") (pinfunction "C_1") (pintype "passive"))
      (node (ref "R17") (pin "1") (pinfunction "1_1") (pintype "passive"))
      (node (ref "U3") (pin "11") (pinfunction "LO1_11") (pintype "passive"))
    )
    (net (code "47") (name "/LO3_2") (class "Default")
      (node (ref "D22") (pin "1") (pinfunction "C_1") (pintype "passive"))
      (node (ref "R16") (pin "1") (pinfunction "1_1") (pintype "passive"))
      (node (ref "U3") (pin "10") (pinfunction "LO2_10") (pintype "passive"))
    )
    (net (code "48") (name "/LO3_3") (class "Default")
      (node (ref "D20") (pin "1") (pinfunction "C_1") (pintype "passive"))
      (node (ref "R14") (pin "1") (pinfunction "1_1") (pintype "passive"))
      (node (ref "U3") (pin "9") (pinfunction "LO3_9") (pintype "passive"))
    )
    (net (code "49") (name "/LO4_1") (class "Default")
      (node (ref "D50") (pin "1") (pinfunction "C_1") (pintype "passive"))
      (node (ref "R35") (pin "1") (pinfunction "1_1") (pintype "passive"))
      (node (ref "U6") (pin "11") (pinfunction "LO1_11") (pintype "passive"))
    )
    (net (code "50") (name "/LO4_2") (class "Default")
      (node (ref "D49") (pin "1") (pinfunction "C_1") (pintype "passive"))
      (node (ref "R34") (pin "1") (pinfunction "1_1") (pintype "passive"))
      (node (ref "U6") (pin "10") (pinfunction "LO2_10") (pintype "passive"))
    )
    (net (code "51") (name "/LO4_3") (class "Default")
      (node (ref "D47") (pin "1") (pinfunction "C_1") (pintype "passive"))
      (node (ref "R32") (pin "1") (pinfunction "1_1") (pintype "passive"))
      (node (ref "U6") (pin "9") (pinfunction "LO3_9") (pintype "passive"))
    )
    (net (code "52") (name "/LO5_1") (class "Default")
      (node (ref "D41") (pin "1") (pinfunction "C_1") (pintype "passive"))
      (node (ref "R26") (pin "1") (pinfunction "1_1") (pintype "passive"))
      (node (ref "U5") (pin "11") (pinfunction "LO1_11") (pintype "passive"))
    )
    (net (code "53") (name "/LO5_2") (class "Default")
      (node (ref "D42") (pin "1") (pinfunction "C_1") (pintype "passive"))
      (node (ref "R27") (pin "1") (pinfunction "1_1") (pintype "passive"))
      (node (ref "U5") (pin "10") (pinfunction "LO2_10") (pintype "passive"))
    )
    (net (code "54") (name "/LO5_3") (class "Default")
      (node (ref "D44") (pin "1") (pinfunction "C_1") (pintype "passive"))
      (node (ref "R29") (pin "1") (pinfunction "1_1") (pintype "passive"))
      (node (ref "U5") (pin "9") (pinfunction "LO3_9") (pintype "passive"))
    )
    (net (code "55") (name "/LO6_1") (class "Default")
      (node (ref "D32") (pin "1") (pinfunction "C_1") (pintype "passive"))
      (node (ref "R20") (pin "1") (pinfunction "1_1") (pintype "passive"))
      (node (ref "U4") (pin "11") (pinfunction "LO1_11") (pintype "passive"))
    )
    (net (code "56") (name "/LO6_2") (class "Default")
      (node (ref "D33") (pin "1") (pinfunction "C_1") (pintype "passive"))
      (node (ref "R21") (pin "1") (pinfunction "1_1") (pintype "passive"))
      (node (ref "U4") (pin "10") (pinfunction "LO2_10") (pintype "passive"))
    )
    (net (code "57") (name "/LO6_3") (class "Default")
      (node (ref "D35") (pin "1") (pinfunction "C_1") (pintype "passive"))
      (node (ref "R23") (pin "1") (pinfunction "1_1") (pintype "passive"))
      (node (ref "U4") (pin "9") (pinfunction "LO3_9") (pintype "passive"))
    )
    (net (code "58") (name "/LO7_1") (class "Default")
      (node (ref "D104") (pin "1") (pinfunction "C_1") (pintype "passive"))
      (node (ref "R71") (pin "1") (pinfunction "1_1") (pintype "passive"))
      (node (ref "U12") (pin "11") (pinfunction "LO1_11") (pintype "passive"))
    )
    (net (code "59") (name "/LO7_2") (class "Default")
      (node (ref "D103") (pin "1") (pinfunction "C_1") (pintype "passive"))
      (node (ref "R70") (pin "1") (pinfunction "1_1") (pintype "passive"))
      (node (ref "U12") (pin "10") (pinfunction "LO2_10") (pintype "passive"))
    )
    (net (code "60") (name "/LO7_3") (class "Default")
      (node (ref "D101") (pin "1") (pinfunction "C_1") (pintype "passive"))
      (node (ref "R68") (pin "1") (pinfunction "1_1") (pintype "passive"))
      (node (ref "U12") (pin "9") (pinfunction "LO3_9") (pintype "passive"))
    )
    (net (code "61") (name "/LO8_1") (class "Default")
      (node (ref "D95") (pin "1") (pinfunction "C_1") (pintype "passive"))
      (node (ref "R62") (pin "1") (pinfunction "1_1") (pintype "passive"))
      (node (ref "U11") (pin "11") (pinfunction "LO1_11") (pintype "passive"))
    )
    (net (code "62") (name "/LO8_2") (class "Default")
      (node (ref "D96") (pin "1") (pinfunction "C_1") (pintype "passive"))
      (node (ref "R63") (pin "1") (pinfunction "1_1") (pintype "passive"))
      (node (ref "U11") (pin "10") (pinfunction "LO2_10") (pintype "passive"))
    )
    (net (code "63") (name "/LO8_3") (class "Default")
      (node (ref "D98") (pin "1") (pinfunction "C_1") (pintype "passive"))
      (node (ref "R65") (pin "1") (pinfunction "1_1") (pintype "passive"))
      (node (ref "U11") (pin "9") (pinfunction "LO3_9") (pintype "passive"))
    )
    (net (code "64") (name "/LO9_1") (class "Default")
      (node (ref "D86") (pin "1") (pinfunction "C_1") (pintype "passive"))
      (node (ref "R56") (pin "1") (pinfunction "1_1") (pintype "passive"))
      (node (ref "U10") (pin "11") (pinfunction "LO1_11") (pintype "passive"))
    )
    (net (code "65") (name "/LO9_2") (class "Default")
      (node (ref "D87") (pin "1") (pinfunction "C_1") (pintype "passive"))
      (node (ref "R57") (pin "1") (pinfunction "1_1") (pintype "passive"))
      (node (ref "U10") (pin "10") (pinfunction "LO2_10") (pintype "passive"))
    )
    (net (code "66") (name "/LO9_3") (class "Default")
      (node (ref "D89") (pin "1") (pinfunction "C_1") (pintype "passive"))
      (node (ref "R59") (pin "1") (pinfunction "1_1") (pintype "passive"))
      (node (ref "U10") (pin "9") (pinfunction "LO3_9") (pintype "passive"))
    )
    (net (code "67") (name "/LO10_1") (class "Default")
      (node (ref "D59") (pin "1") (pinfunction "C_1") (pintype "passive"))
      (node (ref "R38") (pin "1") (pinfunction "1_1") (pintype "passive"))
      (node (ref "U7") (pin "11") (pinfunction "LO1_11") (pintype "passive"))
    )
    (net (code "68") (name "/LO10_2") (class "Default")
      (node (ref "D60") (pin "1") (pinfunction "C_1") (pintype "passive"))
      (node (ref "R39") (pin "1") (pinfunction "1_1") (pintype "passive"))
      (node (ref "U7") (pin "10") (pinfunction "LO2_10") (pintype "passive"))
    )
    (net (code "69") (name "/LO10_3") (class "Default")
      (node (ref "D62") (pin "1") (pinfunction "C_1") (pintype "passive"))
      (node (ref "R41") (pin "1") (pinfunction "1_1") (pintype "passive"))
      (node (ref "U7") (pin "9") (pinfunction "LO3_9") (pintype "passive"))
    )
    (net (code "70") (name "/LO11_1") (class "Default")
      (node (ref "D68") (pin "1") (pinfunction "C_1") (pintype "passive"))
      (node (ref "R47") (pin "1") (pinfunction "1_1") (pintype "passive"))
      (node (ref "U8") (pin "11") (pinfunction "LO1_11") (pintype "passive"))
    )
    (net (code "71") (name "/LO11_2") (class "Default")
      (node (ref "D67") (pin "1") (pinfunction "C_1") (pintype "passive"))
      (node (ref "R46") (pin "1") (pinfunction "1_1") (pintype "passive"))
      (node (ref "U8") (pin "10") (pinfunction "LO2_10") (pintype "passive"))
    )
    (net (code "72") (name "/LO11_3") (class "Default")
      (node (ref "D65") (pin "1") (pinfunction "C_1") (pintype "passive"))
      (node (ref "R44") (pin "1") (pinfunction "1_1") (pintype "passive"))
      (node (ref "U8") (pin "9") (pinfunction "LO3_9") (pintype "passive"))
    )
    (net (code "73") (name "/LO12_1") (class "Default")
      (node (ref "D77") (pin "1") (pinfunction "C_1") (pintype "passive"))
      (node (ref "R53") (pin "1") (pinfunction "1_1") (pintype "passive"))
      (node (ref "U9") (pin "11") (pinfunction "LO1_11") (pintype "passive"))
    )
    (net (code "74") (name "/LO12_2") (class "Default")
      (node (ref "D76") (pin "1") (pinfunction "C_1") (pintype "passive"))
      (node (ref "R52") (pin "1") (pinfunction "1_1") (pintype "passive"))
      (node (ref "U9") (pin "10") (pinfunction "LO2_10") (pintype "passive"))
    )
    (net (code "75") (name "/LO12_3") (class "Default")
      (node (ref "D74") (pin "1") (pinfunction "C_1") (pintype "passive"))
      (node (ref "R50") (pin "1") (pinfunction "1_1") (pintype "passive"))
      (node (ref "U9") (pin "9") (pinfunction "LO3_9") (pintype "passive"))
    )
    (net (code "76") (name "/LO13_1") (class "Default")
      (node (ref "D113") (pin "1") (pinfunction "C_1") (pintype "passive"))
      (node (ref "R74") (pin "1") (pinfunction "1_1") (pintype "passive"))
      (node (ref "U14") (pin "11") (pinfunction "LO1_11") (pintype "passive"))
    )
    (net (code "77") (name "/LO13_2") (class "Default")
      (node (ref "D114") (pin "1") (pinfunction "C_1") (pintype "passive"))
      (node (ref "R75") (pin "1") (pinfunction "1_1") (pintype "passive"))
      (node (ref "U14") (pin "10") (pinfunction "LO2_10") (pintype "passive"))
    )
    (net (code "78") (name "/LO13_3") (class "Default")
      (node (ref "D116") (pin "1") (pinfunction "C_1") (pintype "passive"))
      (node (ref "R77") (pin "1") (pinfunction "1_1") (pintype "passive"))
      (node (ref "U14") (pin "9") (pinfunction "LO3_9") (pintype "passive"))
    )
    (net (code "79") (name "/PWM1_1") (class "Default")
      (node (ref "FPC2") (pin "1") (pinfunction "1_1") (pintype "passive"))
      (node (ref "U1") (pin "1") (pinfunction "HIN1_1") (pintype "passive"))
      (node (ref "U1") (pin "4") (pinfunction "LIN1#_4") (pintype "passive"))
    )
    (net (code "80") (name "/PWM1_2") (class "Default")
      (node (ref "FPC2") (pin "2") (pinfunction "2_2") (pintype "passive"))
      (node (ref "U1") (pin "2") (pinfunction "HIN2_2") (pintype "passive"))
      (node (ref "U1") (pin "5") (pinfunction "LIN2#_5") (pintype "passive"))
    )
    (net (code "81") (name "/PWM1_3") (class "Default")
      (node (ref "FPC2") (pin "3") (pinfunction "3_3") (pintype "passive"))
      (node (ref "U1") (pin "3") (pinfunction "HIN3_3") (pintype "passive"))
      (node (ref "U1") (pin "6") (pinfunction "LIN3#_6") (pintype "passive"))
    )
    (net (code "82") (name "/PWM2_1") (class "Default")
      (node (ref "FPC2") (pin "4") (pinfunction "4_4") (pintype "passive"))
      (node (ref "U2") (pin "1") (pinfunction "HIN1_1") (pintype "passive"))
      (node (ref "U2") (pin "4") (pinfunction "LIN1#_4") (pintype "passive"))
    )
    (net (code "83") (name "/PWM2_2") (class "Default")
      (node (ref "FPC2") (pin "5") (pinfunction "5_5") (pintype "passive"))
      (node (ref "U2") (pin "2") (pinfunction "HIN2_2") (pintype "passive"))
      (node (ref "U2") (pin "5") (pinfunction "LIN2#_5") (pintype "passive"))
    )
    (net (code "84") (name "/PWM2_3") (class "Default")
      (node (ref "FPC2") (pin "6") (pinfunction "6_6") (pintype "passive"))
      (node (ref "U2") (pin "3") (pinfunction "HIN3_3") (pintype "passive"))
      (node (ref "U2") (pin "6") (pinfunction "LIN3#_6") (pintype "passive"))
    )
    (net (code "85") (name "/PWM3_1") (class "Default")
      (node (ref "FPC2") (pin "7") (pinfunction "7_7") (pintype "passive"))
      (node (ref "U3") (pin "1") (pinfunction "HIN1_1") (pintype "passive"))
      (node (ref "U3") (pin "4") (pinfunction "LIN1#_4") (pintype "passive"))
    )
    (net (code "86") (name "/PWM3_2") (class "Default")
      (node (ref "FPC2") (pin "8") (pinfunction "8_8") (pintype "passive"))
      (node (ref "U3") (pin "2") (pinfunction "HIN2_2") (pintype "passive"))
      (node (ref "U3") (pin "5") (pinfunction "LIN2#_5") (pintype "passive"))
    )
    (net (code "87") (name "/PWM3_3") (class "Default")
      (node (ref "FPC2") (pin "9") (pinfunction "9_9") (pintype "passive"))
      (node (ref "U3") (pin "3") (pinfunction "HIN3_3") (pintype "passive"))
      (node (ref "U3") (pin "6") (pinfunction "LIN3#_6") (pintype "passive"))
    )
    (net (code "88") (name "/PWM4_1") (class "Default")
      (node (ref "FPC2") (pin "10") (pinfunction "10_10") (pintype "passive"))
      (node (ref "U6") (pin "1") (pinfunction "HIN1_1") (pintype "passive"))
      (node (ref "U6") (pin "4") (pinfunction "LIN1#_4") (pintype "passive"))
    )
    (net (code "89") (name "/PWM4_2") (class "Default")
      (node (ref "FPC2") (pin "11") (pinfunction "11_11") (pintype "passive"))
      (node (ref "U6") (pin "2") (pinfunction "HIN2_2") (pintype "passive"))
      (node (ref "U6") (pin "5") (pinfunction "LIN2#_5") (pintype "passive"))
    )
    (net (code "90") (name "/PWM4_3") (class "Default")
      (node (ref "FPC2") (pin "12") (pinfunction "12_12") (pintype "passive"))
      (node (ref "U6") (pin "3") (pinfunction "HIN3_3") (pintype "passive"))
      (node (ref "U6") (pin "6") (pinfunction "LIN3#_6") (pintype "passive"))
    )
    (net (code "91") (name "/PWM5_1") (class "Default")
      (node (ref "FPC2") (pin "13") (pinfunction "13_13") (pintype "passive"))
      (node (ref "U5") (pin "1") (pinfunction "HIN1_1") (pintype "passive"))
      (node (ref "U5") (pin "4") (pinfunction "LIN1#_4") (pintype "passive"))
    )
    (net (code "92") (name "/PWM5_2") (class "Default")
      (node (ref "FPC2") (pin "14") (pinfunction "14_14") (pintype "passive"))
      (node (ref "U5") (pin "2") (pinfunction "HIN2_2") (pintype "passive"))
      (node (ref "U5") (pin "5") (pinfunction "LIN2#_5") (pintype "passive"))
    )
    (net (code "93") (name "/PWM5_3") (class "Default")
      (node (ref "FPC2") (pin "15") (pinfunction "15_15") (pintype "passive"))
      (node (ref "U5") (pin "3") (pinfunction "HIN3_3") (pintype "passive"))
      (node (ref "U5") (pin "6") (pinfunction "LIN3#_6") (pintype "passive"))
    )
    (net (code "94") (name "/PWM6_1") (class "Default")
      (node (ref "FPC2") (pin "16") (pinfunction "16_16") (pintype "passive"))
      (node (ref "U4") (pin "1") (pinfunction "HIN1_1") (pintype "passive"))
      (node (ref "U4") (pin "4") (pinfunction "LIN1#_4") (pintype "passive"))
    )
    (net (code "95") (name "/PWM6_2") (class "Default")
      (node (ref "FPC2") (pin "17") (pinfunction "17_17") (pintype "passive"))
      (node (ref "U4") (pin "2") (pinfunction "HIN2_2") (pintype "passive"))
      (node (ref "U4") (pin "5") (pinfunction "LIN2#_5") (pintype "passive"))
    )
    (net (code "96") (name "/PWM6_3") (class "Default")
      (node (ref "FPC2") (pin "18") (pinfunction "18_18") (pintype "passive"))
      (node (ref "U4") (pin "3") (pinfunction "HIN3_3") (pintype "passive"))
      (node (ref "U4") (pin "6") (pinfunction "LIN3#_6") (pintype "passive"))
    )
    (net (code "97") (name "/PWM7_1") (class "Default")
      (node (ref "FPC2") (pin "19") (pinfunction "19_19") (pintype "passive"))
      (node (ref "U12") (pin "1") (pinfunction "HIN1_1") (pintype "passive"))
      (node (ref "U12") (pin "4") (pinfunction "LIN1#_4") (pintype "passive"))
    )
    (net (code "98") (name "/PWM7_2") (class "Default")
      (node (ref "FPC2") (pin "20") (pinfunction "20_20") (pintype "passive"))
      (node (ref "U12") (pin "2") (pinfunction "HIN2_2") (pintype "passive"))
      (node (ref "U12") (pin "5") (pinfunction "LIN2#_5") (pintype "passive"))
    )
    (net (code "99") (name "/PWM7_3") (class "Default")
      (node (ref "FPC2") (pin "21") (pinfunction "21_21") (pintype "passive"))
      (node (ref "U12") (pin "3") (pinfunction "HIN3_3") (pintype "passive"))
      (node (ref "U12") (pin "6") (pinfunction "LIN3#_6") (pintype "passive"))
    )
    (net (code "100") (name "/PWM8_1") (class "Default")
      (node (ref "FPC2") (pin "22") (pinfunction "22_22") (pintype "passive"))
      (node (ref "U11") (pin "1") (pinfunction "HIN1_1") (pintype "passive"))
      (node (ref "U11") (pin "4") (pinfunction "LIN1#_4") (pintype "passive"))
    )
    (net (code "101") (name "/PWM8_2") (class "Default")
      (node (ref "FPC2") (pin "23") (pinfunction "23_23") (pintype "passive"))
      (node (ref "U11") (pin "2") (pinfunction "HIN2_2") (pintype "passive"))
      (node (ref "U11") (pin "5") (pinfunction "LIN2#_5") (pintype "passive"))
    )
    (net (code "102") (name "/PWM8_3") (class "Default")
      (node (ref "FPC2") (pin "24") (pinfunction "24_24") (pintype "passive"))
      (node (ref "U11") (pin "3") (pinfunction "HIN3_3") (pintype "passive"))
      (node (ref "U11") (pin "6") (pinfunction "LIN3#_6") (pintype "passive"))
    )
    (net (code "103") (name "/PWM9_1") (class "Default")
      (node (ref "FPC2") (pin "25") (pinfunction "25_25") (pintype "passive"))
      (node (ref "U10") (pin "1") (pinfunction "HIN1_1") (pintype "passive"))
      (node (ref "U10") (pin "4") (pinfunction "LIN1#_4") (pintype "passive"))
    )
    (net (code "104") (name "/PWM9_2") (class "Default")
      (node (ref "FPC2") (pin "26") (pinfunction "26_26") (pintype "passive"))
      (node (ref "U10") (pin "2") (pinfunction "HIN2_2") (pintype "passive"))
      (node (ref "U10") (pin "5") (pinfunction "LIN2#_5") (pintype "passive"))
    )
    (net (code "105") (name "/PWM9_3") (class "Default")
      (node (ref "FPC2") (pin "27") (pinfunction "27_27") (pintype "passive"))
      (node (ref "U10") (pin "3") (pinfunction "HIN3_3") (pintype "passive"))
      (node (ref "U10") (pin "6") (pinfunction "LIN3#_6") (pintype "passive"))
    )
    (net (code "106") (name "/PWM10_1") (class "Default")
      (node (ref "FPC2") (pin "28") (pinfunction "28_28") (pintype "passive"))
      (node (ref "U7") (pin "1") (pinfunction "HIN1_1") (pintype "passive"))
      (node (ref "U7") (pin "4") (pinfunction "LIN1#_4") (pintype "passive"))
    )
    (net (code "107") (name "/PWM10_2") (class "Default")
      (node (ref "FPC2") (pin "29") (pinfunction "29_29") (pintype "passive"))
      (node (ref "U7") (pin "2") (pinfunction "HIN2_2") (pintype "passive"))
      (node (ref "U7") (pin "5") (pinfunction "LIN2#_5") (pintype "passive"))
    )
    (net (code "108") (name "/PWM10_3") (class "Default")
      (node (ref "FPC2") (pin "30") (pinfunction "30_30") (pintype "passive"))
      (node (ref "U7") (pin "3") (pinfunction "HIN3_3") (pintype "passive"))
      (node (ref "U7") (pin "6") (pinfunction "LIN3#_6") (pintype "passive"))
    )
    (net (code "109") (name "/PWM11_1") (class "Default")
      (node (ref "FPC2") (pin "31") (pinfunction "31_31") (pintype "passive"))
      (node (ref "U8") (pin "1") (pinfunction "HIN1_1") (pintype "passive"))
      (node (ref "U8") (pin "4") (pinfunction "LIN1#_4") (pintype "passive"))
    )
    (net (code "110") (name "/PWM11_2") (class "Default")
      (node (ref "FPC2") (pin "32") (pinfunction "32_32") (pintype "passive"))
      (node (ref "U8") (pin "2") (pinfunction "HIN2_2") (pintype "passive"))
      (node (ref "U8") (pin "5") (pinfunction "LIN2#_5") (pintype "passive"))
    )
    (net (code "111") (name "/PWM11_3") (class "Default")
      (node (ref "FPC2") (pin "33") (pinfunction "33_33") (pintype "passive"))
      (node (ref "U8") (pin "3") (pinfunction "HIN3_3") (pintype "passive"))
      (node (ref "U8") (pin "6") (pinfunction "LIN3#_6") (pintype "passive"))
    )
    (net (code "112") (name "/PWM12_1") (class "Default")
      (node (ref "FPC2") (pin "34") (pinfunction "34_34") (pintype "passive"))
      (node (ref "U9") (pin "1") (pinfunction "HIN1_1") (pintype "passive"))
      (node (ref "U9") (pin "4") (pinfunction "LIN1#_4") (pintype "passive"))
    )
    (net (code "113") (name "/PWM12_2") (class "Default")
      (node (ref "FPC2") (pin "35") (pinfunction "35_35") (pintype "passive"))
      (node (ref "U9") (pin "2") (pinfunction "HIN2_2") (pintype "passive"))
      (node (ref "U9") (pin "5") (pinfunction "LIN2#_5") (pintype "passive"))
    )
    (net (code "114") (name "/PWM12_3") (class "Default")
      (node (ref "FPC2") (pin "36") (pinfunction "36_36") (pintype "passive"))
      (node (ref "U9") (pin "3") (pinfunction "HIN3_3") (pintype "passive"))
      (node (ref "U9") (pin "6") (pinfunction "LIN3#_6") (pintype "passive"))
    )
    (net (code "115") (name "/PWM13_1") (class "Default")
      (node (ref "FPC2") (pin "37") (pinfunction "37_37") (pintype "passive"))
      (node (ref "U14") (pin "1") (pinfunction "HIN1_1") (pintype "passive"))
      (node (ref "U14") (pin "4") (pinfunction "LIN1#_4") (pintype "passive"))
    )
    (net (code "116") (name "/PWM13_2") (class "Default")
      (node (ref "FPC2") (pin "38") (pinfunction "38_38") (pintype "passive"))
      (node (ref "U14") (pin "2") (pinfunction "HIN2_2") (pintype "passive"))
      (node (ref "U14") (pin "5") (pinfunction "LIN2#_5") (pintype "passive"))
    )
    (net (code "117") (name "/PWM13_3") (class "Default")
      (node (ref "FPC2") (pin "39") (pinfunction "39_39") (pintype "passive"))
      (node (ref "U14") (pin "3") (pinfunction "HIN3_3") (pintype "passive"))
      (node (ref "U14") (pin "6") (pinfunction "LIN3#_6") (pintype "passive"))
    )
    (net (code "118") (name "/VB1_1") (class "Default")
      (node (ref "C2") (pin "1") (pinfunction "1_1") (pintype "passive"))
      (node (ref "D108") (pin "1") (pinfunction "K_1") (pintype "passive"))
      (node (ref "U1") (pin "20") (pinfunction "VB1_20") (pintype "passive"))
    )
    (net (code "119") (name "/VB1_2") (class "Default")
      (node (ref "C4") (pin "2") (pinfunction "2_2") (pintype "passive"))
      (node (ref "D109") (pin "1") (pinfunction "K_1") (pintype "passive"))
      (node (ref "U1") (pin "17") (pinfunction "VB2_17") (pintype "passive"))
    )
    (net (code "120") (name "/VB1_3") (class "Default")
      (node (ref "C3") (pin "1") (pinfunction "1_1") (pintype "passive"))
      (node (ref "D110") (pin "1") (pinfunction "K_1") (pintype "passive"))
      (node (ref "U1") (pin "14") (pinfunction "VB3_14") (pintype "passive"))
    )
    (net (code "121") (name "/VB2_1") (class "Default")
      (node (ref "C7") (pin "1") (pinfunction "1_1") (pintype "passive"))
      (node (ref "D93") (pin "1") (pinfunction "K_1") (pintype "passive"))
      (node (ref "U2") (pin "20") (pinfunction "VB1_20") (pintype "passive"))
    )
    (net (code "122") (name "/VB2_2") (class "Default")
      (node (ref "C5") (pin "2") (pinfunction "2_2") (pintype "passive"))
      (node (ref "D106") (pin "1") (pinfunction "K_1") (pintype "passive"))
      (node (ref "U2") (pin "17") (pinfunction "VB2_17") (pintype "passive"))
    )
    (net (code "123") (name "/VB2_3") (class "Default")
      (node (ref "C6") (pin "1") (pinfunction "1_1") (pintype "passive"))
      (node (ref "D107") (pin "1") (pinfunction "K_1") (pintype "passive"))
      (node (ref "U2") (pin "14") (pinfunction "VB3_14") (pintype "passive"))
    )
    (net (code "124") (name "/VB3_1") (class "Default")
      (node (ref "C11") (pin "1") (pinfunction "1_1") (pintype "passive"))
      (node (ref "D84") (pin "1") (pinfunction "K_1") (pintype "passive"))
      (node (ref "U3") (pin "20") (pinfunction "VB1_20") (pintype "passive"))
    )
    (net (code "125") (name "/VB3_2") (class "Default")
      (node (ref "C9") (pin "2") (pinfunction "2_2") (pintype "passive"))
      (node (ref "D91") (pin "1") (pinfunction "K_1") (pintype "passive"))
      (node (ref "U3") (pin "17") (pinfunction "VB2_17") (pintype "passive"))
    )
    (net (code "126") (name "/VB3_3") (class "Default")
      (node (ref "C10") (pin "1") (pinfunction "1_1") (pintype "passive"))
      (node (ref "D92") (pin "1") (pinfunction "K_1") (pintype "passive"))
      (node (ref "U3") (pin "14") (pinfunction "VB3_14") (pintype "passive"))
    )
    (net (code "127") (name "/VB4_1") (class "Default")
      (node (ref "C23") (pin "1") (pinfunction "1_1") (pintype "passive"))
      (node (ref "D118") (pin "1") (pinfunction "K_1") (pintype "passive"))
      (node (ref "U6") (pin "20") (pinfunction "VB1_20") (pintype "passive"))
    )
    (net (code "128") (name "/VB4_2") (class "Default")
      (node (ref "C21") (pin "2") (pinfunction "2_2") (pintype "passive"))
      (node (ref "D52") (pin "1") (pinfunction "K_1") (pintype "passive"))
      (node (ref "U6") (pin "17") (pinfunction "VB2_17") (pintype "passive"))
    )
    (net (code "129") (name "/VB4_3") (class "Default")
      (node (ref "C22") (pin "1") (pinfunction "1_1") (pintype "passive"))
      (node (ref "D53") (pin "1") (pinfunction "K_1") (pintype "passive"))
      (node (ref "U6") (pin "14") (pinfunction "VB3_14") (pintype "passive"))
    )
    (net (code "130") (name "/VB5_1") (class "Default")
      (node (ref "C18") (pin "1") (pinfunction "1_1") (pintype "passive"))
      (node (ref "D81") (pin "1") (pinfunction "K_1") (pintype "passive"))
      (node (ref "U5") (pin "20") (pinfunction "VB1_20") (pintype "passive"))
    )
    (net (code "131") (name "/VB5_2") (class "Default")
      (node (ref "C20") (pin "2") (pinfunction "2_2") (pintype "passive"))
      (node (ref "D82") (pin "1") (pinfunction "K_1") (pintype "passive"))
      (node (ref "U5") (pin "17") (pinfunction "VB2_17") (pintype "passive"))
    )
    (net (code "132") (name "/VB5_3") (class "Default")
      (node (ref "C19") (pin "1") (pinfunction "1_1") (pintype "passive"))
      (node (ref "D83") (pin "1") (pinfunction "K_1") (pintype "passive"))
      (node (ref "U5") (pin "14") (pinfunction "VB3_14") (pintype "passive"))
    )
    (net (code "133") (name "/VB6_1") (class "Default")
      (node (ref "C14") (pin "1") (pinfunction "1_1") (pintype "passive"))
      (node (ref "D72") (pin "1") (pinfunction "K_1") (pintype "passive"))
      (node (ref "U4") (pin "20") (pinfunction "VB1_20") (pintype "passive"))
    )
    (net (code "134") (name "/VB6_2") (class "Default")
      (node (ref "C16") (pin "2") (pinfunction "2_2") (pintype "passive"))
      (node (ref "D79") (pin "1") (pinfunction "K_1") (pintype "passive"))
      (node (ref "U4") (pin "17") (pinfunction "VB2_17") (pintype "passive"))
    )
    (net (code "135") (name "/VB6_3") (class "Default")
      (node (ref "C15") (pin "1") (pinfunction "1_1") (pintype "passive"))
      (node (ref "D80") (pin "1") (pinfunction "K_1") (pintype "passive"))
      (node (ref "U4") (pin "14") (pinfunction "VB3_14") (pintype "passive"))
    )
    (net (code "136") (name "/VB7_1") (class "Default")
      (node (ref "C47") (pin "1") (pinfunction "1_1") (pintype "passive"))
      (node (ref "D54") (pin "1") (pinfunction "K_1") (pintype "passive"))
      (node (ref "U12") (pin "20") (pinfunction "VB1_20") (pintype "passive"))
    )
    (net (code "137") (name "/VB7_2") (class "Default")
      (node (ref "C45") (pin "2") (pinfunction "2_2") (pintype "passive"))
      (node (ref "D55") (pin "1") (pinfunction "K_1") (pintype "passive"))
      (node (ref "U12") (pin "17") (pinfunction "VB2_17") (pintype "passive"))
    )
    (net (code "138") (name "/VB7_3") (class "Default")
      (node (ref "C46") (pin "1") (pinfunction "1_1") (pintype "passive"))
      (node (ref "D56") (pin "1") (pinfunction "K_1") (pintype "passive"))
      (node (ref "U12") (pin "14") (pinfunction "VB3_14") (pintype "passive"))
    )
    (net (code "139") (name "/VB8_1") (class "Default")
      (node (ref "C42") (pin "1") (pinfunction "1_1") (pintype "passive"))
      (node (ref "D37") (pin "1") (pinfunction "K_1") (pintype "passive"))
      (node (ref "U11") (pin "20") (pinfunction "VB1_20") (pintype "passive"))
    )
    (net (code "140") (name "/VB8_2") (class "Default")
      (node (ref "C44") (pin "2") (pinfunction "2_2") (pintype "passive"))
      (node (ref "D38") (pin "1") (pinfunction "K_1") (pintype "passive"))
      (node (ref "U11") (pin "17") (pinfunction "VB2_17") (pintype "passive"))
    )
    (net (code "141") (name "/VB8_3") (class "Default")
      (node (ref "C43") (pin "1") (pinfunction "1_1") (pintype "passive"))
      (node (ref "D39") (pin "1") (pinfunction "K_1") (pintype "passive"))
      (node (ref "U11") (pin "14") (pinfunction "VB3_14") (pintype "passive"))
    )
    (net (code "142") (name "/VB9_1") (class "Default")
      (node (ref "C38") (pin "1") (pinfunction "1_1") (pintype "passive"))
      (node (ref "D25") (pin "1") (pinfunction "K_1") (pintype "passive"))
      (node (ref "U10") (pin "20") (pinfunction "VB1_20") (pintype "passive"))
    )
    (net (code "143") (name "/VB9_2") (class "Default")
      (node (ref "C40") (pin "2") (pinfunction "2_2") (pintype "passive"))
      (node (ref "D26") (pin "1") (pinfunction "K_1") (pintype "passive"))
      (node (ref "U10") (pin "17") (pinfunction "VB2_17") (pintype "passive"))
    )
    (net (code "144") (name "/VB9_3") (class "Default")
      (node (ref "C39") (pin "1") (pinfunction "1_1") (pintype "passive"))
      (node (ref "D27") (pin "1") (pinfunction "K_1") (pintype "passive"))
      (node (ref "U10") (pin "14") (pinfunction "VB3_14") (pintype "passive"))
    )
    (net (code "145") (name "/VB10_1") (class "Default")
      (node (ref "C26") (pin "1") (pinfunction "1_1") (pintype "passive"))
      (node (ref "D57") (pin "1") (pinfunction "K_1") (pintype "passive"))
      (node (ref "U7") (pin "20") (pinfunction "VB1_20") (pintype "passive"))
    )
    (net (code "146") (name "/VB10_2") (class "Default")
      (node (ref "C28") (pin "2") (pinfunction "2_2") (pintype "passive"))
      (node (ref "D70") (pin "1") (pinfunction "K_1") (pintype "passive"))
      (node (ref "U7") (pin "17") (pinfunction "VB2_17") (pintype "passive"))
    )
    (net (code "147") (name "/VB10_3") (class "Default")
      (node (ref "C27") (pin "1") (pinfunction "1_1") (pintype "passive"))
      (node (ref "D71") (pin "1") (pinfunction "K_1") (pintype "passive"))
      (node (ref "U7") (pin "14") (pinfunction "VB3_14") (pintype "passive"))
    )
    (net (code "148") (name "/VB11_1") (class "Default")
      (node (ref "C31") (pin "1") (pinfunction "1_1") (pintype "passive"))
      (node (ref "D28") (pin "1") (pinfunction "K_1") (pintype "passive"))
      (node (ref "U8") (pin "20") (pinfunction "VB1_20") (pintype "passive"))
    )
    (net (code "149") (name "/VB11_2") (class "Default")
      (node (ref "C29") (pin "2") (pinfunction "2_2") (pintype "passive"))
      (node (ref "D29") (pin "1") (pinfunction "K_1") (pintype "passive"))
      (node (ref "U8") (pin "17") (pinfunction "VB2_17") (pintype "passive"))
    )
    (net (code "150") (name "/VB11_3") (class "Default")
      (node (ref "C30") (pin "1") (pinfunction "1_1") (pintype "passive"))
      (node (ref "D30") (pin "1") (pinfunction "K_1") (pintype "passive"))
      (node (ref "U8") (pin "14") (pinfunction "VB3_14") (pintype "passive"))
    )
    (net (code "151") (name "/VB12_1") (class "Default")
      (node (ref "C35") (pin "1") (pinfunction "1_1") (pintype "passive"))
      (node (ref "D16") (pin "1") (pinfunction "K_1") (pintype "passive"))
      (node (ref "U9") (pin "20") (pinfunction "VB1_20") (pintype "passive"))
    )
    (net (code "152") (name "/VB12_2") (class "Default")
      (node (ref "C33") (pin "2") (pinfunction "2_2") (pintype "passive"))
      (node (ref "D17") (pin "1") (pinfunction "K_1") (pintype "passive"))
      (node (ref "U9") (pin "17") (pinfunction "VB2_17") (pintype "passive"))
    )
    (net (code "153") (name "/VB12_3") (class "Default")
      (node (ref "C34") (pin "1") (pinfunction "1_1") (pintype "passive"))
      (node (ref "D18") (pin "1") (pinfunction "K_1") (pintype "passive"))
      (node (ref "U9") (pin "14") (pinfunction "VB3_14") (pintype "passive"))
    )
    (net (code "154") (name "/VB13_1") (class "Default")
      (node (ref "C50") (pin "1") (pinfunction "1_1") (pintype "passive"))
      (node (ref "D1") (pin "1") (pinfunction "K_1") (pintype "passive"))
      (node (ref "U14") (pin "20") (pinfunction "VB1_20") (pintype "passive"))
    )
    (net (code "155") (name "/VB13_2") (class "Default")
      (node (ref "C52") (pin "2") (pinfunction "2_2") (pintype "passive"))
      (node (ref "D2") (pin "1") (pinfunction "K_1") (pintype "passive"))
      (node (ref "U14") (pin "17") (pinfunction "VB2_17") (pintype "passive"))
    )
    (net (code "156") (name "/VB13_3") (class "Default")
      (node (ref "C51") (pin "1") (pinfunction "1_1") (pintype "passive"))
      (node (ref "D3") (pin "1") (pinfunction "K_1") (pintype "passive"))
      (node (ref "U14") (pin "14") (pinfunction "VB3_14") (pintype "passive"))
    )
    (net (code "157") (name "/VS1_1") (class "Default")
      (node (ref "C2") (pin "2") (pinfunction "2_2") (pintype "passive"))
      (node (ref "CN1") (pin "3") (pinfunction "3_3") (pintype "passive"))
      (node (ref "Q1") (pin "2") (pinfunction "S_2") (pintype "passive"))
      (node (ref "Q2") (pin "3") (pinfunction "D_3") (pintype "passive"))
      (node (ref "U1") (pin "18") (pinfunction "VS1_18") (pintype "passive"))
    )
    (net (code "158") (name "/VS1_2") (class "Default")
      (node (ref "C4") (pin "1") (pinfunction "1_1") (pintype "passive"))
      (node (ref "CN1") (pin "2") (pinfunction "2_2") (pintype "passive"))
      (node (ref "Q3") (pin "2") (pinfunction "S_2") (pintype "passive"))
      (node (ref "Q4") (pin "3") (pinfunction "D_3") (pintype "passive"))
      (node (ref "U1") (pin "15") (pinfunction "VS2_15") (pintype "passive"))
    )
    (net (code "159") (name "/VS1_3") (class "Default")
      (node (ref "C3") (pin "2") (pinfunction "2_2") (pintype "passive"))
      (node (ref "CN1") (pin "1") (pinfunction "1_1") (pintype "passive"))
      (node (ref "Q5") (pin "2") (pinfunction "S_2") (pintype "passive"))
      (node (ref "Q6") (pin "3") (pinfunction "D_3") (pintype "passive"))
      (node (ref "U1") (pin "12") (pinfunction "VS3_12") (pintype "passive"))
    )
    (net (code "160") (name "/VS2_1") (class "Default")
      (node (ref "C7") (pin "2") (pinfunction "2_2") (pintype "passive"))
      (node (ref "CN2") (pin "3") (pinfunction "3_3") (pintype "passive"))
      (node (ref "Q11") (pin "3") (pinfunction "D_3") (pintype "passive"))
      (node (ref "Q12") (pin "2") (pinfunction "S_2") (pintype "passive"))
      (node (ref "U2") (pin "18") (pinfunction "VS1_18") (pintype "passive"))
    )
    (net (code "161") (name "/VS2_2") (class "Default")
      (node (ref "C5") (pin "1") (pinfunction "1_1") (pintype "passive"))
      (node (ref "CN2") (pin "2") (pinfunction "2_2") (pintype "passive"))
      (node (ref "Q10") (pin "2") (pinfunction "S_2") (pintype "passive"))
      (node (ref "Q9") (pin "3") (pinfunction "D_3") (pintype "passive"))
      (node (ref "U2") (pin "15") (pinfunction "VS2_15") (pintype "passive"))
    )
    (net (code "162") (name "/VS2_3") (class "Default")
      (node (ref "C6") (pin "2") (pinfunction "2_2") (pintype "passive"))
      (node (ref "CN2") (pin "1") (pinfunction "1_1") (pintype "passive"))
      (node (ref "Q7") (pin "3") (pinfunction "D_3") (pintype "passive"))
      (node (ref "Q8") (pin "2") (pinfunction "S_2") (pintype "passive"))
      (node (ref "U2") (pin "12") (pinfunction "VS3_12") (pintype "passive"))
    )
    (net (code "163") (name "/VS3_1") (class "Default")
      (node (ref "C11") (pin "2") (pinfunction "2_2") (pintype "passive"))
      (node (ref "CN3") (pin "3") (pinfunction "3_3") (pintype "passive"))
      (node (ref "Q17") (pin "3") (pinfunction "D_3") (pintype "passive"))
      (node (ref "Q18") (pin "2") (pinfunction "S_2") (pintype "passive"))
      (node (ref "U3") (pin "18") (pinfunction "VS1_18") (pintype "passive"))
    )
    (net (code "164") (name "/VS3_2") (class "Default")
      (node (ref "C9") (pin "1") (pinfunction "1_1") (pintype "passive"))
      (node (ref "CN3") (pin "2") (pinfunction "2_2") (pintype "passive"))
      (node (ref "Q15") (pin "3") (pinfunction "D_3") (pintype "passive"))
      (node (ref "Q16") (pin "2") (pinfunction "S_2") (pintype "passive"))
      (node (ref "U3") (pin "15") (pinfunction "VS2_15") (pintype "passive"))
    )
    (net (code "165") (name "/VS3_3") (class "Default")
      (node (ref "C10") (pin "2") (pinfunction "2_2") (pintype "passive"))
      (node (ref "CN3") (pin "1") (pinfunction "1_1") (pintype "passive"))
      (node (ref "Q13") (pin "3") (pinfunction "D_3") (pintype "passive"))
      (node (ref "Q14") (pin "2") (pinfunction "S_2") (pintype "passive"))
      (node (ref "U3") (pin "12") (pinfunction "VS3_12") (pintype "passive"))
    )
    (net (code "166") (name "/VS4_1") (class "Default")
      (node (ref "C23") (pin "2") (pinfunction "2_2") (pintype "passive"))
      (node (ref "CN6") (pin "3") (pinfunction "3_3") (pintype "passive"))
      (node (ref "Q35") (pin "3") (pinfunction "D_3") (pintype "passive"))
      (node (ref "Q36") (pin "2") (pinfunction "S_2") (pintype "passive"))
      (node (ref "U6") (pin "18") (pinfunction "VS1_18") (pintype "passive"))
    )
    (net (code "167") (name "/VS4_2") (class "Default")
      (node (ref "C21") (pin "1") (pinfunction "1_1") (pintype "passive"))
      (node (ref "CN6") (pin "2") (pinfunction "2_2") (pintype "passive"))
      (node (ref "Q33") (pin "3") (pinfunction "D_3") (pintype "passive"))
      (node (ref "Q34") (pin "2") (pinfunction "S_2") (pintype "passive"))
      (node (ref "U6") (pin "15") (pinfunction "VS2_15") (pintype "passive"))
    )
    (net (code "168") (name "/VS4_3") (class "Default")
      (node (ref "C22") (pin "2") (pinfunction "2_2") (pintype "passive"))
      (node (ref "CN6") (pin "1") (pinfunction "1_1") (pintype "passive"))
      (node (ref "Q31") (pin "3") (pinfunction "D_3") (pintype "passive"))
      (node (ref "Q32") (pin "2") (pinfunction "S_2") (pintype "passive"))
      (node (ref "U6") (pin "12") (pinfunction "VS3_12") (pintype "passive"))
    )
    (net (code "169") (name "/VS5_1") (class "Default")
      (node (ref "C18") (pin "2") (pinfunction "2_2") (pintype "passive"))
      (node (ref "CN5") (pin "3") (pinfunction "3_3") (pintype "passive"))
      (node (ref "Q25") (pin "2") (pinfunction "S_2") (pintype "passive"))
      (node (ref "Q26") (pin "3") (pinfunction "D_3") (pintype "passive"))
      (node (ref "U5") (pin "18") (pinfunction "VS1_18") (pintype "passive"))
    )
    (net (code "170") (name "/VS5_2") (class "Default")
      (node (ref "C20") (pin "1") (pinfunction "1_1") (pintype "passive"))
      (node (ref "CN5") (pin "2") (pinfunction "2_2") (pintype "passive"))
      (node (ref "Q27") (pin "2") (pinfunction "S_2") (pintype "passive"))
      (node (ref "Q28") (pin "3") (pinfunction "D_3") (pintype "passive"))
      (node (ref "U5") (pin "15") (pinfunction "VS2_15") (pintype "passive"))
    )
    (net (code "171") (name "/VS5_3") (class "Default")
      (node (ref "C19") (pin "2") (pinfunction "2_2") (pintype "passive"))
      (node (ref "CN5") (pin "1") (pinfunction "1_1") (pintype "passive"))
      (node (ref "Q29") (pin "2") (pinfunction "S_2") (pintype "passive"))
      (node (ref "Q30") (pin "3") (pinfunction "D_3") (pintype "passive"))
      (node (ref "U5") (pin "12") (pinfunction "VS3_12") (pintype "passive"))
    )
    (net (code "172") (name "/VS6_1") (class "Default")
      (node (ref "C14") (pin "2") (pinfunction "2_2") (pintype "passive"))
      (node (ref "CN4") (pin "3") (pinfunction "3_3") (pintype "passive"))
      (node (ref "Q19") (pin "2") (pinfunction "S_2") (pintype "passive"))
      (node (ref "Q20") (pin "3") (pinfunction "D_3") (pintype "passive"))
      (node (ref "U4") (pin "18") (pinfunction "VS1_18") (pintype "passive"))
    )
    (net (code "173") (name "/VS6_2") (class "Default")
      (node (ref "C16") (pin "1") (pinfunction "1_1") (pintype "passive"))
      (node (ref "CN4") (pin "2") (pinfunction "2_2") (pintype "passive"))
      (node (ref "Q21") (pin "2") (pinfunction "S_2") (pintype "passive"))
      (node (ref "Q22") (pin "3") (pinfunction "D_3") (pintype "passive"))
      (node (ref "U4") (pin "15") (pinfunction "VS2_15") (pintype "passive"))
    )
    (net (code "174") (name "/VS6_3") (class "Default")
      (node (ref "C15") (pin "2") (pinfunction "2_2") (pintype "passive"))
      (node (ref "CN4") (pin "1") (pinfunction "1_1") (pintype "passive"))
      (node (ref "Q23") (pin "2") (pinfunction "S_2") (pintype "passive"))
      (node (ref "Q24") (pin "3") (pinfunction "D_3") (pintype "passive"))
      (node (ref "U4") (pin "12") (pinfunction "VS3_12") (pintype "passive"))
    )
    (net (code "175") (name "/VS7_1") (class "Default")
      (node (ref "C47") (pin "2") (pinfunction "2_2") (pintype "passive"))
      (node (ref "CN12") (pin "3") (pinfunction "3_3") (pintype "passive"))
      (node (ref "Q71") (pin "3") (pinfunction "D_3") (pintype "passive"))
      (node (ref "Q72") (pin "2") (pinfunction "S_2") (pintype "passive"))
      (node (ref "U12") (pin "18") (pinfunction "VS1_18") (pintype "passive"))
    )
    (net (code "176") (name "/VS7_2") (class "Default")
      (node (ref "C45") (pin "1") (pinfunction "1_1") (pintype "passive"))
      (node (ref "CN12") (pin "2") (pinfunction "2_2") (pintype "passive"))
      (node (ref "Q69") (pin "3") (pinfunction "D_3") (pintype "passive"))
      (node (ref "Q70") (pin "2") (pinfunction "S_2") (pintype "passive"))
      (node (ref "U12") (pin "15") (pinfunction "VS2_15") (pintype "passive"))
    )
    (net (code "177") (name "/VS7_3") (class "Default")
      (node (ref "C46") (pin "2") (pinfunction "2_2") (pintype "passive"))
      (node (ref "CN12") (pin "1") (pinfunction "1_1") (pintype "passive"))
      (node (ref "Q67") (pin "3") (pinfunction "D_3") (pintype "passive"))
      (node (ref "Q68") (pin "2") (pinfunction "S_2") (pintype "passive"))
      (node (ref "U12") (pin "12") (pinfunction "VS3_12") (pintype "passive"))
    )
    (net (code "178") (name "/VS8_1") (class "Default")
      (node (ref "C42") (pin "2") (pinfunction "2_2") (pintype "passive"))
      (node (ref "CN11") (pin "3") (pinfunction "3_3") (pintype "passive"))
      (node (ref "Q61") (pin "2") (pinfunction "S_2") (pintype "passive"))
      (node (ref "Q62") (pin "3") (pinfunction "D_3") (pintype "passive"))
      (node (ref "U11") (pin "18") (pinfunction "VS1_18") (pintype "passive"))
    )
    (net (code "179") (name "/VS8_2") (class "Default")
      (node (ref "C44") (pin "1") (pinfunction "1_1") (pintype "passive"))
      (node (ref "CN11") (pin "2") (pinfunction "2_2") (pintype "passive"))
      (node (ref "Q63") (pin "2") (pinfunction "S_2") (pintype "passive"))
      (node (ref "Q64") (pin "3") (pinfunction "D_3") (pintype "passive"))
      (node (ref "U11") (pin "15") (pinfunction "VS2_15") (pintype "passive"))
    )
    (net (code "180") (name "/VS8_3") (class "Default")
      (node (ref "C43") (pin "2") (pinfunction "2_2") (pintype "passive"))
      (node (ref "CN11") (pin "1") (pinfunction "1_1") (pintype "passive"))
      (node (ref "Q65") (pin "2") (pinfunction "S_2") (pintype "passive"))
      (node (ref "Q66") (pin "3") (pinfunction "D_3") (pintype "passive"))
      (node (ref "U11") (pin "12") (pinfunction "VS3_12") (pintype "passive"))
    )
    (net (code "181") (name "/VS9_1") (class "Default")
      (node (ref "C38") (pin "2") (pinfunction "2_2") (pintype "passive"))
      (node (ref "CN10") (pin "3") (pinfunction "3_3") (pintype "passive"))
      (node (ref "Q55") (pin "2") (pinfunction "S_2") (pintype "passive"))
      (node (ref "Q56") (pin "3") (pinfunction "D_3") (pintype "passive"))
      (node (ref "U10") (pin "18") (pinfunction "VS1_18") (pintype "passive"))
    )
    (net (code "182") (name "/VS9_2") (class "Default")
      (node (ref "C40") (pin "1") (pinfunction "1_1") (pintype "passive"))
      (node (ref "CN10") (pin "2") (pinfunction "2_2") (pintype "passive"))
      (node (ref "Q57") (pin "2") (pinfunction "S_2") (pintype "passive"))
      (node (ref "Q58") (pin "3") (pinfunction "D_3") (pintype "passive"))
      (node (ref "U10") (pin "15") (pinfunction "VS2_15") (pintype "passive"))
    )
    (net (code "183") (name "/VS9_3") (class "Default")
      (node (ref "C39") (pin "2") (pinfunction "2_2") (pintype "passive"))
      (node (ref "CN10") (pin "1") (pinfunction "1_1") (pintype "passive"))
      (node (ref "Q59") (pin "2") (pinfunction "S_2") (pintype "passive"))
      (node (ref "Q60") (pin "3") (pinfunction "D_3") (pintype "passive"))
      (node (ref "U10") (pin "12") (pinfunction "VS3_12") (pintype "passive"))
    )
    (net (code "184") (name "/VS10_1") (class "Default")
      (node (ref "C26") (pin "2") (pinfunction "2_2") (pintype "passive"))
      (node (ref "CN7") (pin "3") (pinfunction "3_3") (pintype "passive"))
      (node (ref "Q37") (pin "2") (pinfunction "S_2") (pintype "passive"))
      (node (ref "Q38") (pin "3") (pinfunction "D_3") (pintype "passive"))
      (node (ref "U7") (pin "18") (pinfunction "VS1_18") (pintype "passive"))
    )
    (net (code "185") (name "/VS10_2") (class "Default")
      (node (ref "C28") (pin "1") (pinfunction "1_1") (pintype "passive"))
      (node (ref "CN7") (pin "2") (pinfunction "2_2") (pintype "passive"))
      (node (ref "Q39") (pin "2") (pinfunction "S_2") (pintype "passive"))
      (node (ref "Q40") (pin "3") (pinfunction "D_3") (pintype "passive"))
      (node (ref "U7") (pin "15") (pinfunction "VS2_15") (pintype "passive"))
    )
    (net (code "186") (name "/VS10_3") (class "Default")
      (node (ref "C27") (pin "2") (pinfunction "2_2") (pintype "passive"))
      (node (ref "CN7") (pin "1") (pinfunction "1_1") (pintype "passive"))
      (node (ref "Q41") (pin "2") (pinfunction "S_2") (pintype "passive"))
      (node (ref "Q42") (pin "3") (pinfunction "D_3") (pintype "passive"))
      (node (ref "U7") (pin "12") (pinfunction "VS3_12") (pintype "passive"))
    )
    (net (code "187") (name "/VS11_1") (class "Default")
      (node (ref "C31") (pin "2") (pinfunction "2_2") (pintype "passive"))
      (node (ref "CN8") (pin "3") (pinfunction "3_3") (pintype "passive"))
      (node (ref "Q47") (pin "3") (pinfunction "D_3") (pintype "passive"))
      (node (ref "Q48") (pin "2") (pinfunction "S_2") (pintype "passive"))
      (node (ref "U8") (pin "18") (pinfunction "VS1_18") (pintype "passive"))
    )
    (net (code "188") (name "/VS11_2") (class "Default")
      (node (ref "C29") (pin "1") (pinfunction "1_1") (pintype "passive"))
      (node (ref "CN8") (pin "2") (pinfunction "2_2") (pintype "passive"))
      (node (ref "Q45") (pin "3") (pinfunction "D_3") (pintype "passive"))
      (node (ref "Q46") (pin "2") (pinfunction "S_2") (pintype "passive"))
      (node (ref "U8") (pin "15") (pinfunction "VS2_15") (pintype "passive"))
    )
    (net (code "189") (name "/VS11_3") (class "Default")
      (node (ref "C30") (pin "2") (pinfunction "2_2") (pintype "passive"))
      (node (ref "CN8") (pin "1") (pinfunction "1_1") (pintype "passive"))
      (node (ref "Q43") (pin "3") (pinfunction "D_3") (pintype "passive"))
      (node (ref "Q44") (pin "2") (pinfunction "S_2") (pintype "passive"))
      (node (ref "U8") (pin "12") (pinfunction "VS3_12") (pintype "passive"))
    )
    (net (code "190") (name "/VS12_1") (class "Default")
      (node (ref "C35") (pin "2") (pinfunction "2_2") (pintype "passive"))
      (node (ref "CN9") (pin "3") (pinfunction "3_3") (pintype "passive"))
      (node (ref "Q53") (pin "3") (pinfunction "D_3") (pintype "passive"))
      (node (ref "Q54") (pin "2") (pinfunction "S_2") (pintype "passive"))
      (node (ref "U9") (pin "18") (pinfunction "VS1_18") (pintype "passive"))
    )
    (net (code "191") (name "/VS12_2") (class "Default")
      (node (ref "C33") (pin "1") (pinfunction "1_1") (pintype "passive"))
      (node (ref "CN9") (pin "2") (pinfunction "2_2") (pintype "passive"))
      (node (ref "Q51") (pin "3") (pinfunction "D_3") (pintype "passive"))
      (node (ref "Q52") (pin "2") (pinfunction "S_2") (pintype "passive"))
      (node (ref "U9") (pin "15") (pinfunction "VS2_15") (pintype "passive"))
    )
    (net (code "192") (name "/VS12_3") (class "Default")
      (node (ref "C34") (pin "2") (pinfunction "2_2") (pintype "passive"))
      (node (ref "CN9") (pin "1") (pinfunction "1_1") (pintype "passive"))
      (node (ref "Q49") (pin "3") (pinfunction "D_3") (pintype "passive"))
      (node (ref "Q50") (pin "2") (pinfunction "S_2") (pintype "passive"))
      (node (ref "U9") (pin "12") (pinfunction "VS3_12") (pintype "passive"))
    )
    (net (code "193") (name "/VS13_1") (class "Default")
      (node (ref "C50") (pin "2") (pinfunction "2_2") (pintype "passive"))
      (node (ref "CN13") (pin "3") (pinfunction "3_3") (pintype "passive"))
      (node (ref "Q73") (pin "2") (pinfunction "S_2") (pintype "passive"))
      (node (ref "Q74") (pin "3") (pinfunction "D_3") (pintype "passive"))
      (node (ref "U14") (pin "18") (pinfunction "VS1_18") (pintype "passive"))
    )
    (net (code "194") (name "/VS13_2") (class "Default")
      (node (ref "C52") (pin "1") (pinfunction "1_1") (pintype "passive"))
      (node (ref "CN13") (pin "2") (pinfunction "2_2") (pintype "passive"))
      (node (ref "Q75") (pin "2") (pinfunction "S_2") (pintype "passive"))
      (node (ref "Q76") (pin "3") (pinfunction "D_3") (pintype "passive"))
      (node (ref "U14") (pin "15") (pinfunction "VS2_15") (pintype "passive"))
    )
    (net (code "195") (name "/VS13_3") (class "Default")
      (node (ref "C51") (pin "2") (pinfunction "2_2") (pintype "passive"))
      (node (ref "CN13") (pin "1") (pinfunction "1_1") (pintype "passive"))
      (node (ref "Q77") (pin "2") (pinfunction "S_2") (pintype "passive"))
      (node (ref "Q78") (pin "3") (pinfunction "D_3") (pintype "passive"))
      (node (ref "U14") (pin "12") (pinfunction "VS3_12") (pintype "passive"))
    )
    (net (code "196") (name "Net-(D4-A)") (class "Default")
      (node (ref "D4") (pin "2") (pinfunction "A_2") (pintype "passive"))
      (node (ref "Q2") (pin "1") (pinfunction "G_1") (pintype "passive"))
      (node (ref "R2") (pin "2") (pinfunction "2_2") (pintype "passive"))
    )
    (net (code "197") (name "Net-(D5-A)") (class "Default")
      (node (ref "D5") (pin "2") (pinfunction "A_2") (pintype "passive"))
      (node (ref "Q1") (pin "1") (pinfunction "G_1") (pintype "passive"))
      (node (ref "R1") (pin "2") (pinfunction "2_2") (pintype "passive"))
    )
    (net (code "198") (name "Net-(D6-A)") (class "Default")
      (node (ref "D6") (pin "2") (pinfunction "A_2") (pintype "passive"))
      (node (ref "Q4") (pin "1") (pinfunction "G_1") (pintype "passive"))
      (node (ref "R3") (pin "2") (pinfunction "2_2") (pintype "passive"))
    )
    (net (code "199") (name "Net-(D7-A)") (class "Default")
      (node (ref "D7") (pin "2") (pinfunction "A_2") (pintype "passive"))
      (node (ref "Q3") (pin "1") (pinfunction "G_1") (pintype "passive"))
      (node (ref "R4") (pin "2") (pinfunction "2_2") (pintype "passive"))
    )
    (net (code "200") (name "Net-(D8-A)") (class "Default")
      (node (ref "D8") (pin "2") (pinfunction "A_2") (pintype "passive"))
      (node (ref "Q6") (pin "1") (pinfunction "G_1") (pintype "passive"))
      (node (ref "R5") (pin "2") (pinfunction "2_2") (pintype "passive"))
    )
    (net (code "201") (name "Net-(D9-A)") (class "Default")
      (node (ref "D9") (pin "2") (pinfunction "A_2") (pintype "passive"))
      (node (ref "Q5") (pin "1") (pinfunction "G_1") (pintype "passive"))
      (node (ref "R6") (pin "2") (pinfunction "2_2") (pintype "passive"))
    )
    (net (code "202") (name "Net-(D10-A)") (class "Default")
      (node (ref "D10") (pin "2") (pinfunction "A_2") (pintype "passive"))
      (node (ref "Q8") (pin "1") (pinfunction "G_1") (pintype "passive"))
      (node (ref "R7") (pin "2") (pinfunction "2_2") (pintype "passive"))
    )
    (net (code "203") (name "Net-(D11-A)") (class "Default")
      (node (ref "D11") (pin "2") (pinfunction "A_2") (pintype "passive"))
      (node (ref "Q7") (pin "1") (pinfunction "G_1") (pintype "passive"))
      (node (ref "R8") (pin "2") (pinfunction "2_2") (pintype "passive"))
    )
    (net (code "204") (name "Net-(D12-A)") (class "Default")
      (node (ref "D12") (pin "2") (pinfunction "A_2") (pintype "passive"))
      (node (ref "Q10") (pin "1") (pinfunction "G_1") (pintype "passive"))
      (node (ref "R9") (pin "2") (pinfunction "2_2") (pintype "passive"))
    )
    (net (code "205") (name "Net-(D13-A)") (class "Default")
      (node (ref "D13") (pin "2") (pinfunction "A_2") (pintype "passive"))
      (node (ref "Q9") (pin "1") (pinfunction "G_1") (pintype "passive"))
      (node (ref "R10") (pin "2") (pinfunction "2_2") (pintype "passive"))
    )
    (net (code "206") (name "Net-(D14-A)") (class "Default")
      (node (ref "D14") (pin "2") (pinfunction "A_2") (pintype "passive"))
      (node (ref "Q11") (pin "1") (pinfunction "G_1") (pintype "passive"))
      (node (ref "R11") (pin "2") (pinfunction "2_2") (pintype "passive"))
    )
    (net (code "207") (name "Net-(D15-A)") (class "Default")
      (node (ref "D15") (pin "2") (pinfunction "A_2") (pintype "passive"))
      (node (ref "Q12") (pin "1") (pinfunction "G_1") (pintype "passive"))
      (node (ref "R12") (pin "2") (pinfunction "2_2") (pintype "passive"))
    )
    (net (code "208") (name "Net-(D19-A)") (class "Default")
      (node (ref "D19") (pin "2") (pinfunction "A_2") (pintype "passive"))
      (node (ref "Q14") (pin "1") (pinfunction "G_1") (pintype "passive"))
      (node (ref "R13") (pin "2") (pinfunction "2_2") (pintype "passive"))
    )
    (net (code "209") (name "Net-(D20-A)") (class "Default")
      (node (ref "D20") (pin "2") (pinfunction "A_2") (pintype "passive"))
      (node (ref "Q13") (pin "1") (pinfunction "G_1") (pintype "passive"))
      (node (ref "R14") (pin "2") (pinfunction "2_2") (pintype "passive"))
    )
    (net (code "210") (name "Net-(D21-A)") (class "Default")
      (node (ref "D21") (pin "2") (pinfunction "A_2") (pintype "passive"))
      (node (ref "Q16") (pin "1") (pinfunction "G_1") (pintype "passive"))
      (node (ref "R15") (pin "2") (pinfunction "2_2") (pintype "passive"))
    )
    (net (code "211") (name "Net-(D22-A)") (class "Default")
      (node (ref "D22") (pin "2") (pinfunction "A_2") (pintype "passive"))
      (node (ref "Q15") (pin "1") (pinfunction "G_1") (pintype "passive"))
      (node (ref "R16") (pin "2") (pinfunction "2_2") (pintype "passive"))
    )
    (net (code "212") (name "Net-(D23-A)") (class "Default")
      (node (ref "D23") (pin "2") (pinfunction "A_2") (pintype "passive"))
      (node (ref "Q17") (pin "1") (pinfunction "G_1") (pintype "passive"))
      (node (ref "R17") (pin "2") (pinfunction "2_2") (pintype "passive"))
    )
    (net (code "213") (name "Net-(D24-A)") (class "Default")
      (node (ref "D24") (pin "2") (pinfunction "A_2") (pintype "passive"))
      (node (ref "Q18") (pin "1") (pinfunction "G_1") (pintype "passive"))
      (node (ref "R18") (pin "2") (pinfunction "2_2") (pintype "passive"))
    )
    (net (code "214") (name "Net-(D31-A)") (class "Default")
      (node (ref "D31") (pin "2") (pinfunction "A_2") (pintype "passive"))
      (node (ref "Q19") (pin "1") (pinfunction "G_1") (pintype "passive"))
      (node (ref "R19") (pin "2") (pinfunction "2_2") (pintype "passive"))
    )
    (net (code "215") (name "Net-(D32-A)") (class "Default")
      (node (ref "D32") (pin "2") (pinfunction "A_2") (pintype "passive"))
      (node (ref "Q20") (pin "1") (pinfunction "G_1") (pintype "passive"))
      (node (ref "R20") (pin "2") (pinfunction "2_2") (pintype "passive"))
    )
    (net (code "216") (name "Net-(D33-A)") (class "Default")
      (node (ref "D33") (pin "2") (pinfunction "A_2") (pintype "passive"))
      (node (ref "Q22") (pin "1") (pinfunction "G_1") (pintype "passive"))
      (node (ref "R21") (pin "2") (pinfunction "2_2") (pintype "passive"))
    )
    (net (code "217") (name "Net-(D34-A)") (class "Default")
      (node (ref "D34") (pin "2") (pinfunction "A_2") (pintype "passive"))
      (node (ref "Q21") (pin "1") (pinfunction "G_1") (pintype "passive"))
      (node (ref "R22") (pin "2") (pinfunction "2_2") (pintype "passive"))
    )
    (net (code "218") (name "Net-(D35-A)") (class "Default")
      (node (ref "D35") (pin "2") (pinfunction "A_2") (pintype "passive"))
      (node (ref "Q24") (pin "1") (pinfunction "G_1") (pintype "passive"))
      (node (ref "R23") (pin "2") (pinfunction "2_2") (pintype "passive"))
    )
    (net (code "219") (name "Net-(D36-A)") (class "Default")
      (node (ref "D36") (pin "2") (pinfunction "A_2") (pintype "passive"))
      (node (ref "Q23") (pin "1") (pinfunction "G_1") (pintype "passive"))
      (node (ref "R24") (pin "2") (pinfunction "2_2") (pintype "passive"))
    )
    (net (code "220") (name "Net-(D40-A)") (class "Default")
      (node (ref "D40") (pin "2") (pinfunction "A_2") (pintype "passive"))
      (node (ref "Q25") (pin "1") (pinfunction "G_1") (pintype "passive"))
      (node (ref "R25") (pin "2") (pinfunction "2_2") (pintype "passive"))
    )
    (net (code "221") (name "Net-(D41-A)") (class "Default")
      (node (ref "D41") (pin "2") (pinfunction "A_2") (pintype "passive"))
      (node (ref "Q26") (pin "1") (pinfunction "G_1") (pintype "passive"))
      (node (ref "R26") (pin "2") (pinfunction "2_2") (pintype "passive"))
    )
    (net (code "222") (name "Net-(D42-A)") (class "Default")
      (node (ref "D42") (pin "2") (pinfunction "A_2") (pintype "passive"))
      (node (ref "Q28") (pin "1") (pinfunction "G_1") (pintype "passive"))
      (node (ref "R27") (pin "2") (pinfunction "2_2") (pintype "passive"))
    )
    (net (code "223") (name "Net-(D43-A)") (class "Default")
      (node (ref "D43") (pin "2") (pinfunction "A_2") (pintype "passive"))
      (node (ref "Q27") (pin "1") (pinfunction "G_1") (pintype "passive"))
      (node (ref "R28") (pin "2") (pinfunction "2_2") (pintype "passive"))
    )
    (net (code "224") (name "Net-(D44-A)") (class "Default")
      (node (ref "D44") (pin "2") (pinfunction "A_2") (pintype "passive"))
      (node (ref "Q30") (pin "1") (pinfunction "G_1") (pintype "passive"))
      (node (ref "R29") (pin "2") (pinfunction "2_2") (pintype "passive"))
    )
    (net (code "225") (name "Net-(D45-A)") (class "Default")
      (node (ref "D45") (pin "2") (pinfunction "A_2") (pintype "passive"))
      (node (ref "Q29") (pin "1") (pinfunction "G_1") (pintype "passive"))
      (node (ref "R30") (pin "2") (pinfunction "2_2") (pintype "passive"))
    )
    (net (code "226") (name "Net-(D46-A)") (class "Default")
      (node (ref "D46") (pin "2") (pinfunction "A_2") (pintype "passive"))
      (node (ref "Q32") (pin "1") (pinfunction "G_1") (pintype "passive"))
      (node (ref "R31") (pin "2") (pinfunction "2_2") (pintype "passive"))
    )
    (net (code "227") (name "Net-(D47-A)") (class "Default")
      (node (ref "D47") (pin "2") (pinfunction "A_2") (pintype "passive"))
      (node (ref "Q31") (pin "1") (pinfunction "G_1") (pintype "passive"))
      (node (ref "R32") (pin "2") (pinfunction "2_2") (pintype "passive"))
    )
    (net (code "228") (name "Net-(D48-A)") (class "Default")
      (node (ref "D48") (pin "2") (pinfunction "A_2") (pintype "passive"))
      (node (ref "Q34") (pin "1") (pinfunction "G_1") (pintype "passive"))
      (node (ref "R33") (pin "2") (pinfunction "2_2") (pintype "passive"))
    )
    (net (code "229") (name "Net-(D49-A)") (class "Default")
      (node (ref "D49") (pin "2") (pinfunction "A_2") (pintype "passive"))
      (node (ref "Q33") (pin "1") (pinfunction "G_1") (pintype "passive"))
      (node (ref "R34") (pin "2") (pinfunction "2_2") (pintype "passive"))
    )
    (net (code "230") (name "Net-(D50-A)") (class "Default")
      (node (ref "D50") (pin "2") (pinfunction "A_2") (pintype "passive"))
      (node (ref "Q35") (pin "1") (pinfunction "G_1") (pintype "passive"))
      (node (ref "R35") (pin "2") (pinfunction "2_2") (pintype "passive"))
    )
    (net (code "231") (name "Net-(D51-A)") (class "Default")
      (node (ref "D51") (pin "2") (pinfunction "A_2") (pintype "passive"))
      (node (ref "Q36") (pin "1") (pinfunction "G_1") (pintype "passive"))
      (node (ref "R36") (pin "2") (pinfunction "2_2") (pintype "passive"))
    )
    (net (code "232") (name "Net-(D58-A)") (class "Default")
      (node (ref "D58") (pin "2") (pinfunction "A_2") (pintype "passive"))
      (node (ref "Q37") (pin "1") (pinfunction "G_1") (pintype "passive"))
      (node (ref "R37") (pin "2") (pinfunction "2_2") (pintype "passive"))
    )
    (net (code "233") (name "Net-(D59-A)") (class "Default")
      (node (ref "D59") (pin "2") (pinfunction "A_2") (pintype "passive"))
      (node (ref "Q38") (pin "1") (pinfunction "G_1") (pintype "passive"))
      (node (ref "R38") (pin "2") (pinfunction "2_2") (pintype "passive"))
    )
    (net (code "234") (name "Net-(D60-A)") (class "Default")
      (node (ref "D60") (pin "2") (pinfunction "A_2") (pintype "passive"))
      (node (ref "Q40") (pin "1") (pinfunction "G_1") (pintype "passive"))
      (node (ref "R39") (pin "2") (pinfunction "2_2") (pintype "passive"))
    )
    (net (code "235") (name "Net-(D61-A)") (class "Default")
      (node (ref "D61") (pin "2") (pinfunction "A_2") (pintype "passive"))
      (node (ref "Q39") (pin "1") (pinfunction "G_1") (pintype "passive"))
      (node (ref "R40") (pin "2") (pinfunction "2_2") (pintype "passive"))
    )
    (net (code "236") (name "Net-(D62-A)") (class "Default")
      (node (ref "D62") (pin "2") (pinfunction "A_2") (pintype "passive"))
      (node (ref "Q42") (pin "1") (pinfunction "G_1") (pintype "passive"))
      (node (ref "R41") (pin "2") (pinfunction "2_2") (pintype "passive"))
    )
    (net (code "237") (name "Net-(D63-A)") (class "Default")
      (node (ref "D63") (pin "2") (pinfunction "A_2") (pintype "passive"))
      (node (ref "Q41") (pin "1") (pinfunction "G_1") (pintype "passive"))
      (node (ref "R42") (pin "2") (pinfunction "2_2") (pintype "passive"))
    )
    (net (code "238") (name "Net-(D64-A)") (class "Default")
      (node (ref "D64") (pin "2") (pinfunction "A_2") (pintype "passive"))
      (node (ref "Q44") (pin "1") (pinfunction "G_1") (pintype "passive"))
      (node (ref "R43") (pin "2") (pinfunction "2_2") (pintype "passive"))
    )
    (net (code "239") (name "Net-(D65-A)") (class "Default")
      (node (ref "D65") (pin "2") (pinfunction "A_2") (pintype "passive"))
      (node (ref "Q43") (pin "1") (pinfunction "G_1") (pintype "passive"))
      (node (ref "R44") (pin "2") (pinfunction "2_2") (pintype "passive"))
    )
    (net (code "240") (name "Net-(D66-A)") (class "Default")
      (node (ref "D66") (pin "2") (pinfunction "A_2") (pintype "passive"))
      (node (ref "Q46") (pin "1") (pinfunction "G_1") (pintype "passive"))
      (node (ref "R45") (pin "2") (pinfunction "2_2") (pintype "passive"))
    )
    (net (code "241") (name "Net-(D67-A)") (class "Default")
      (node (ref "D67") (pin "2") (pinfunction "A_2") (pintype "passive"))
      (node (ref "Q45") (pin "1") (pinfunction "G_1") (pintype "passive"))
      (node (ref "R46") (pin "2") (pinfunction "2_2") (pintype "passive"))
    )
    (net (code "242") (name "Net-(D68-A)") (class "Default")
      (node (ref "D68") (pin "2") (pinfunction "A_2") (pintype "passive"))
      (node (ref "Q47") (pin "1") (pinfunction "G_1") (pintype "passive"))
      (node (ref "R47") (pin "2") (pinfunction "2_2") (pintype "passive"))
    )
    (net (code "243") (name "Net-(D69-A)") (class "Default")
      (node (ref "D69") (pin "2") (pinfunction "A_2") (pintype "passive"))
      (node (ref "Q48") (pin "1") (pinfunction "G_1") (pintype "passive"))
      (node (ref "R48") (pin "2") (pinfunction "2_2") (pintype "passive"))
    )
    (net (code "244") (name "Net-(D73-A)") (class "Default")
      (node (ref "D73") (pin "2") (pinfunction "A_2") (pintype "passive"))
      (node (ref "Q50") (pin "1") (pinfunction "G_1") (pintype "passive"))
      (node (ref "R49") (pin "2") (pinfunction "2_2") (pintype "passive"))
    )
    (net (code "245") (name "Net-(D74-A)") (class "Default")
      (node (ref "D74") (pin "2") (pinfunction "A_2") (pintype "passive"))
      (node (ref "Q49") (pin "1") (pinfunction "G_1") (pintype "passive"))
      (node (ref "R50") (pin "2") (pinfunction "2_2") (pintype "passive"))
    )
    (net (code "246") (name "Net-(D75-A)") (class "Default")
      (node (ref "D75") (pin "2") (pinfunction "A_2") (pintype "passive"))
      (node (ref "Q52") (pin "1") (pinfunction "G_1") (pintype "passive"))
      (node (ref "R51") (pin "2") (pinfunction "2_2") (pintype "passive"))
    )
    (net (code "247") (name "Net-(D76-A)") (class "Default")
      (node (ref "D76") (pin "2") (pinfunction "A_2") (pintype "passive"))
      (node (ref "Q51") (pin "1") (pinfunction "G_1") (pintype "passive"))
      (node (ref "R52") (pin "2") (pinfunction "2_2") (pintype "passive"))
    )
    (net (code "248") (name "Net-(D77-A)") (class "Default")
      (node (ref "D77") (pin "2") (pinfunction "A_2") (pintype "passive"))
      (node (ref "Q53") (pin "1") (pinfunction "G_1") (pintype "passive"))
      (node (ref "R53") (pin "2") (pinfunction "2_2") (pintype "passive"))
    )
    (net (code "249") (name "Net-(D78-A)") (class "Default")
      (node (ref "D78") (pin "2") (pinfunction "A_2") (pintype "passive"))
      (node (ref "Q54") (pin "1") (pinfunction "G_1") (pintype "passive"))
      (node (ref "R54") (pin "2") (pinfunction "2_2") (pintype "passive"))
    )
    (net (code "250") (name "Net-(D85-A)") (class "Default")
      (node (ref "D85") (pin "2") (pinfunction "A_2") (pintype "passive"))
      (node (ref "Q55") (pin "1") (pinfunction "G_1") (pintype "passive"))
      (node (ref "R55") (pin "2") (pinfunction "2_2") (pintype "passive"))
    )
    (net (code "251") (name "Net-(D86-A)") (class "Default")
      (node (ref "D86") (pin "2") (pinfunction "A_2") (pintype "passive"))
      (node (ref "Q56") (pin "1") (pinfunction "G_1") (pintype "passive"))
      (node (ref "R56") (pin "2") (pinfunction "2_2") (pintype "passive"))
    )
    (net (code "252") (name "Net-(D87-A)") (class "Default")
      (node (ref "D87") (pin "2") (pinfunction "A_2") (pintype "passive"))
      (node (ref "Q58") (pin "1") (pinfunction "G_1") (pintype "passive"))
      (node (ref "R57") (pin "2") (pinfunction "2_2") (pintype "passive"))
    )
    (net (code "253") (name "Net-(D88-A)") (class "Default")
      (node (ref "D88") (pin "2") (pinfunction "A_2") (pintype "passive"))
      (node (ref "Q57") (pin "1") (pinfunction "G_1") (pintype "passive"))
      (node (ref "R58") (pin "2") (pinfunction "2_2") (pintype "passive"))
    )
    (net (code "254") (name "Net-(D89-A)") (class "Default")
      (node (ref "D89") (pin "2") (pinfunction "A_2") (pintype "passive"))
      (node (ref "Q60") (pin "1") (pinfunction "G_1") (pintype "passive"))
      (node (ref "R59") (pin "2") (pinfunction "2_2") (pintype "passive"))
    )
    (net (code "255") (name "Net-(D90-A)") (class "Default")
      (node (ref "D90") (pin "2") (pinfunction "A_2") (pintype "passive"))
      (node (ref "Q59") (pin "1") (pinfunction "G_1") (pintype "passive"))
      (node (ref "R60") (pin "2") (pinfunction "2_2") (pintype "passive"))
    )
    (net (code "256") (name "Net-(D94-A)") (class "Default")
      (node (ref "D94") (pin "2") (pinfunction "A_2") (pintype "passive"))
      (node (ref "Q61") (pin "1") (pinfunction "G_1") (pintype "passive"))
      (node (ref "R61") (pin "2") (pinfunction "2_2") (pintype "passive"))
    )
    (net (code "257") (name "Net-(D95-A)") (class "Default")
      (node (ref "D95") (pin "2") (pinfunction "A_2") (pintype "passive"))
      (node (ref "Q62") (pin "1") (pinfunction "G_1") (pintype "passive"))
      (node (ref "R62") (pin "2") (pinfunction "2_2") (pintype "passive"))
    )
    (net (code "258") (name "Net-(D96-A)") (class "Default")
      (node (ref "D96") (pin "2") (pinfunction "A_2") (pintype "passive"))
      (node (ref "Q64") (pin "1") (pinfunction "G_1") (pintype "passive"))
      (node (ref "R63") (pin "2") (pinfunction "2_2") (pintype "passive"))
    )
    (net (code "259") (name "Net-(D97-A)") (class "Default")
      (node (ref "D97") (pin "2") (pinfunction "A_2") (pintype "passive"))
      (node (ref "Q63") (pin "1") (pinfunction "G_1") (pintype "passive"))
      (node (ref "R64") (pin "2") (pinfunction "2_2") (pintype "passive"))
    )
    (net (code "260") (name "Net-(D98-A)") (class "Default")
      (node (ref "D98") (pin "2") (pinfunction "A_2") (pintype "passive"))
      (node (ref "Q66") (pin "1") (pinfunction "G_1") (pintype "passive"))
      (node (ref "R65") (pin "2") (pinfunction "2_2") (pintype "passive"))
    )
    (net (code "261") (name "Net-(D99-A)") (class "Default")
      (node (ref "D99") (pin "2") (pinfunction "A_2") (pintype "passive"))
      (node (ref "Q65") (pin "1") (pinfunction "G_1") (pintype "passive"))
      (node (ref "R66") (pin "2") (pinfunction "2_2") (pintype "passive"))
    )
    (net (code "262") (name "Net-(D100-A)") (class "Default")
      (node (ref "D100") (pin "2") (pinfunction "A_2") (pintype "passive"))
      (node (ref "Q68") (pin "1") (pinfunction "G_1") (pintype "passive"))
      (node (ref "R67") (pin "2") (pinfunction "2_2") (pintype "passive"))
    )
    (net (code "263") (name "Net-(D101-A)") (class "Default")
      (node (ref "D101") (pin "2") (pinfunction "A_2") (pintype "passive"))
      (node (ref "Q67") (pin "1") (pinfunction "G_1") (pintype "passive"))
      (node (ref "R68") (pin "2") (pinfunction "2_2") (pintype "passive"))
    )
    (net (code "264") (name "Net-(D102-A)") (class "Default")
      (node (ref "D102") (pin "2") (pinfunction "A_2") (pintype "passive"))
      (node (ref "Q70") (pin "1") (pinfunction "G_1") (pintype "passive"))
      (node (ref "R69") (pin "2") (pinfunction "2_2") (pintype "passive"))
    )
    (net (code "265") (name "Net-(D103-A)") (class "Default")
      (node (ref "D103") (pin "2") (pinfunction "A_2") (pintype "passive"))
      (node (ref "Q69") (pin "1") (pinfunction "G_1") (pintype "passive"))
      (node (ref "R70") (pin "2") (pinfunction "2_2") (pintype "passive"))
    )
    (net (code "266") (name "Net-(D104-A)") (class "Default")
      (node (ref "D104") (pin "2") (pinfunction "A_2") (pintype "passive"))
      (node (ref "Q71") (pin "1") (pinfunction "G_1") (pintype "passive"))
      (node (ref "R71") (pin "2") (pinfunction "2_2") (pintype "passive"))
    )
    (net (code "267") (name "Net-(D105-A)") (class "Default")
      (node (ref "D105") (pin "2") (pinfunction "A_2") (pintype "passive"))
      (node (ref "Q72") (pin "1") (pinfunction "G_1") (pintype "passive"))
      (node (ref "R72") (pin "2") (pinfunction "2_2") (pintype "passive"))
    )
    (net (code "268") (name "Net-(D112-A)") (class "Default")
      (node (ref "D112") (pin "2") (pinfunction "A_2") (pintype "passive"))
      (node (ref "Q73") (pin "1") (pinfunction "G_1") (pintype "passive"))
      (node (ref "R73") (pin "2") (pinfunction "2_2") (pintype "passive"))
    )
    (net (code "269") (name "Net-(D113-A)") (class "Default")
      (node (ref "D113") (pin "2") (pinfunction "A_2") (pintype "passive"))
      (node (ref "Q74") (pin "1") (pinfunction "G_1") (pintype "passive"))
      (node (ref "R74") (pin "2") (pinfunction "2_2") (pintype "passive"))
    )
    (net (code "270") (name "Net-(D114-A)") (class "Default")
      (node (ref "D114") (pin "2") (pinfunction "A_2") (pintype "passive"))
      (node (ref "Q76") (pin "1") (pinfunction "G_1") (pintype "passive"))
      (node (ref "R75") (pin "2") (pinfunction "2_2") (pintype "passive"))
    )
    (net (code "271") (name "Net-(D115-A)") (class "Default")
      (node (ref "D115") (pin "2") (pinfunction "A_2") (pintype "passive"))
      (node (ref "Q75") (pin "1") (pinfunction "G_1") (pintype "passive"))
      (node (ref "R76") (pin "2") (pinfunction "2_2") (pintype "passive"))
    )
    (net (code "272") (name "Net-(D116-A)") (class "Default")
      (node (ref "D116") (pin "2") (pinfunction "A_2") (pintype "passive"))
      (node (ref "Q78") (pin "1") (pinfunction "G_1") (pintype "passive"))
      (node (ref "R77") (pin "2") (pinfunction "2_2") (pintype "passive"))
    )
    (net (code "273") (name "Net-(D117-A)") (class "Default")
      (node (ref "D117") (pin "2") (pinfunction "A_2") (pintype "passive"))
      (node (ref "Q77") (pin "1") (pinfunction "G_1") (pintype "passive"))
      (node (ref "R78") (pin "2") (pinfunction "2_2") (pintype "passive"))
    )
    (net (code "274") (name "PGND") (class "Default")
      (node (ref "C1") (pin "1") (pinfunction "1_1") (pintype "passive"))
      (node (ref "C12") (pin "1") (pinfunction "1_1") (pintype "passive"))
      (node (ref "C13") (pin "1") (pinfunction "1_1") (pintype "passive"))
      (node (ref "C17") (pin "1") (pinfunction "1_1") (pintype "passive"))
      (node (ref "C24") (pin "1") (pinfunction "1_1") (pintype "passive"))
      (node (ref "C25") (pin "1") (pinfunction "1_1") (pintype "passive"))
      (node (ref "C32") (pin "1") (pinfunction "1_1") (pintype "passive"))
      (node (ref "C36") (pin "1") (pinfunction "1_1") (pintype "passive"))
      (node (ref "C37") (pin "1") (pinfunction "1_1") (pintype "passive"))
      (node (ref "C41") (pin "1") (pinfunction "1_1") (pintype "passive"))
      (node (ref "C48") (pin "1") (pinfunction "1_1") (pintype "passive"))
      (node (ref "C49") (pin "1") (pinfunction "1_1") (pintype "passive"))
      (node (ref "C8") (pin "1") (pinfunction "1_1") (pintype "passive"))
      (node (ref "Q11") (pin "2") (pinfunction "S_2") (pintype "passive"))
      (node (ref "Q13") (pin "2") (pinfunction "S_2") (pintype "passive"))
      (node (ref "Q15") (pin "2") (pinfunction "S_2") (pintype "passive"))
      (node (ref "Q17") (pin "2") (pinfunction "S_2") (pintype "passive"))
      (node (ref "Q2") (pin "2") (pinfunction "S_2") (pintype "passive"))
      (node (ref "Q20") (pin "2") (pinfunction "S_2") (pintype "passive"))
      (node (ref "Q22") (pin "2") (pinfunction "S_2") (pintype "passive"))
      (node (ref "Q24") (pin "2") (pinfunction "S_2") (pintype "passive"))
      (node (ref "Q26") (pin "2") (pinfunction "S_2") (pintype "passive"))
      (node (ref "Q28") (pin "2") (pinfunction "S_2") (pintype "passive"))
      (node (ref "Q30") (pin "2") (pinfunction "S_2") (pintype "passive"))
      (node (ref "Q31") (pin "2") (pinfunction "S_2") (pintype "passive"))
      (node (ref "Q33") (pin "2") (pinfunction "S_2") (pintype "passive"))
      (node (ref "Q35") (pin "2") (pinfunction "S_2") (pintype "passive"))
      (node (ref "Q38") (pin "2") (pinfunction "S_2") (pintype "passive"))
      (node (ref "Q4") (pin "2") (pinfunction "S_2") (pintype "passive"))
      (node (ref "Q40") (pin "2") (pinfunction "S_2") (pintype "passive"))
      (node (ref "Q42") (pin "2") (pinfunction "S_2") (pintype "passive"))
      (node (ref "Q43") (pin "2") (pinfunction "S_2") (pintype "passive"))
      (node (ref "Q45") (pin "2") (pinfunction "S_2") (pintype "passive"))
      (node (ref "Q47") (pin "2") (pinfunction "S_2") (pintype "passive"))
      (node (ref "Q49") (pin "2") (pinfunction "S_2") (pintype "passive"))
      (node (ref "Q51") (pin "2") (pinfunction "S_2") (pintype "passive"))
      (node (ref "Q53") (pin "2") (pinfunction "S_2") (pintype "passive"))
      (node (ref "Q56") (pin "2") (pinfunction "S_2") (pintype "passive"))
      (node (ref "Q58") (pin "2") (pinfunction "S_2") (pintype "passive"))
      (node (ref "Q6") (pin "2") (pinfunction "S_2") (pintype "passive"))
      (node (ref "Q60") (pin "2") (pinfunction "S_2") (pintype "passive"))
      (node (ref "Q62") (pin "2") (pinfunction "S_2") (pintype "passive"))
      (node (ref "Q64") (pin "2") (pinfunction "S_2") (pintype "passive"))
      (node (ref "Q66") (pin "2") (pinfunction "S_2") (pintype "passive"))
      (node (ref "Q67") (pin "2") (pinfunction "S_2") (pintype "passive"))
      (node (ref "Q69") (pin "2") (pinfunction "S_2") (pintype "passive"))
      (node (ref "Q7") (pin "2") (pinfunction "S_2") (pintype "passive"))
      (node (ref "Q71") (pin "2") (pinfunction "S_2") (pintype "passive"))
      (node (ref "Q74") (pin "2") (pinfunction "S_2") (pintype "passive"))
      (node (ref "Q76") (pin "2") (pinfunction "S_2") (pintype "passive"))
      (node (ref "Q78") (pin "2") (pinfunction "S_2") (pintype "passive"))
      (node (ref "Q9") (pin "2") (pinfunction "S_2") (pintype "passive"))
      (node (ref "U1") (pin "8") (pinfunction "GND_8") (pintype "passive"))
      (node (ref "U10") (pin "8") (pinfunction "GND_8") (pintype "passive"))
      (node (ref "U11") (pin "8") (pinfunction "GND_8") (pintype "passive"))
      (node (ref "U12") (pin "8") (pinfunction "GND_8") (pintype "passive"))
      (node (ref "U13") (pin "1") (pinfunction "1_1") (pintype "passive"))
      (node (ref "U14") (pin "8") (pinfunction "GND_8") (pintype "passive"))
      (node (ref "U2") (pin "8") (pinfunction "GND_8") (pintype "passive"))
      (node (ref "U3") (pin "8") (pinfunction "GND_8") (pintype "passive"))
      (node (ref "U4") (pin "8") (pinfunction "GND_8") (pintype "passive"))
      (node (ref "U5") (pin "8") (pinfunction "GND_8") (pintype "passive"))
      (node (ref "U6") (pin "8") (pinfunction "GND_8") (pintype "passive"))
      (node (ref "U7") (pin "8") (pinfunction "GND_8") (pintype "passive"))
      (node (ref "U8") (pin "8") (pinfunction "GND_8") (pintype "passive"))
      (node (ref "U9") (pin "8") (pinfunction "GND_8") (pintype "passive"))
    )
    (net (code "275") (name "VIN") (class "Default")
      (node (ref "C1") (pin "2") (pinfunction "2_2") (pintype "passive"))
      (node (ref "C12") (pin "2") (pinfunction "2_2") (pintype "passive"))
      (node (ref "C13") (pin "2") (pinfunction "2_2") (pintype "passive"))
      (node (ref "C17") (pin "2") (pinfunction "2_2") (pintype "passive"))
      (node (ref "C24") (pin "2") (pinfunction "2_2") (pintype "passive"))
      (node (ref "C25") (pin "2") (pinfunction "2_2") (pintype "passive"))
      (node (ref "C32") (pin "2") (pinfunction "2_2") (pintype "passive"))
      (node (ref "C36") (pin "2") (pinfunction "2_2") (pintype "passive"))
      (node (ref "C37") (pin "2") (pinfunction "2_2") (pintype "passive"))
      (node (ref "C41") (pin "2") (pinfunction "2_2") (pintype "passive"))
      (node (ref "C48") (pin "2") (pinfunction "2_2") (pintype "passive"))
      (node (ref "C49") (pin "2") (pinfunction "2_2") (pintype "passive"))
      (node (ref "C8") (pin "2") (pinfunction "2_2") (pintype "passive"))
      (node (ref "D1") (pin "2") (pinfunction "A_2") (pintype "passive"))
      (node (ref "D106") (pin "2") (pinfunction "A_2") (pintype "passive"))
      (node (ref "D107") (pin "2") (pinfunction "A_2") (pintype "passive"))
      (node (ref "D108") (pin "2") (pinfunction "A_2") (pintype "passive"))
      (node (ref "D109") (pin "2") (pinfunction "A_2") (pintype "passive"))
      (node (ref "D110") (pin "2") (pinfunction "A_2") (pintype "passive"))
      (node (ref "D118") (pin "2") (pinfunction "A_2") (pintype "passive"))
      (node (ref "D16") (pin "2") (pinfunction "A_2") (pintype "passive"))
      (node (ref "D17") (pin "2") (pinfunction "A_2") (pintype "passive"))
      (node (ref "D18") (pin "2") (pinfunction "A_2") (pintype "passive"))
      (node (ref "D2") (pin "2") (pinfunction "A_2") (pintype "passive"))
      (node (ref "D25") (pin "2") (pinfunction "A_2") (pintype "passive"))
      (node (ref "D26") (pin "2") (pinfunction "A_2") (pintype "passive"))
      (node (ref "D27") (pin "2") (pinfunction "A_2") (pintype "passive"))
      (node (ref "D28") (pin "2") (pinfunction "A_2") (pintype "passive"))
      (node (ref "D29") (pin "2") (pinfunction "A_2") (pintype "passive"))
      (node (ref "D3") (pin "2") (pinfunction "A_2") (pintype "passive"))
      (node (ref "D30") (pin "2") (pinfunction "A_2") (pintype "passive"))
      (node (ref "D37") (pin "2") (pinfunction "A_2") (pintype "passive"))
      (node (ref "D38") (pin "2") (pinfunction "A_2") (pintype "passive"))
      (node (ref "D39") (pin "2") (pinfunction "A_2") (pintype "passive"))
      (node (ref "D52") (pin "2") (pinfunction "A_2") (pintype "passive"))
      (node (ref "D53") (pin "2") (pinfunction "A_2") (pintype "passive"))
      (node (ref "D54") (pin "2") (pinfunction "A_2") (pintype "passive"))
      (node (ref "D55") (pin "2") (pinfunction "A_2") (pintype "passive"))
      (node (ref "D56") (pin "2") (pinfunction "A_2") (pintype "passive"))
      (node (ref "D57") (pin "2") (pinfunction "A_2") (pintype "passive"))
      (node (ref "D70") (pin "2") (pinfunction "A_2") (pintype "passive"))
      (node (ref "D71") (pin "2") (pinfunction "A_2") (pintype "passive"))
      (node (ref "D72") (pin "2") (pinfunction "A_2") (pintype "passive"))
      (node (ref "D79") (pin "2") (pinfunction "A_2") (pintype "passive"))
      (node (ref "D80") (pin "2") (pinfunction "A_2") (pintype "passive"))
      (node (ref "D81") (pin "2") (pinfunction "A_2") (pintype "passive"))
      (node (ref "D82") (pin "2") (pinfunction "A_2") (pintype "passive"))
      (node (ref "D83") (pin "2") (pinfunction "A_2") (pintype "passive"))
      (node (ref "D84") (pin "2") (pinfunction "A_2") (pintype "passive"))
      (node (ref "D91") (pin "2") (pinfunction "A_2") (pintype "passive"))
      (node (ref "D92") (pin "2") (pinfunction "A_2") (pintype "passive"))
      (node (ref "D93") (pin "2") (pinfunction "A_2") (pintype "passive"))
      (node (ref "Q1") (pin "3") (pinfunction "D_3") (pintype "passive"))
      (node (ref "Q10") (pin "3") (pinfunction "D_3") (pintype "passive"))
      (node (ref "Q12") (pin "3") (pinfunction "D_3") (pintype "passive"))
      (node (ref "Q14") (pin "3") (pinfunction "D_3") (pintype "passive"))
      (node (ref "Q16") (pin "3") (pinfunction "D_3") (pintype "passive"))
      (node (ref "Q18") (pin "3") (pinfunction "D_3") (pintype "passive"))
      (node (ref "Q19") (pin "3") (pinfunction "D_3") (pintype "passive"))
      (node (ref "Q21") (pin "3") (pinfunction "D_3") (pintype "passive"))
      (node (ref "Q23") (pin "3") (pinfunction "D_3") (pintype "passive"))
      (node (ref "Q25") (pin "3") (pinfunction "D_3") (pintype "passive"))
      (node (ref "Q27") (pin "3") (pinfunction "D_3") (pintype "passive"))
      (node (ref "Q29") (pin "3") (pinfunction "D_3") (pintype "passive"))
      (node (ref "Q3") (pin "3") (pinfunction "D_3") (pintype "passive"))
      (node (ref "Q32") (pin "3") (pinfunction "D_3") (pintype "passive"))
      (node (ref "Q34") (pin "3") (pinfunction "D_3") (pintype "passive"))
      (node (ref "Q36") (pin "3") (pinfunction "D_3") (pintype "passive"))
      (node (ref "Q37") (pin "3") (pinfunction "D_3") (pintype "passive"))
      (node (ref "Q39") (pin "3") (pinfunction "D_3") (pintype "passive"))
      (node (ref "Q41") (pin "3") (pinfunction "D_3") (pintype "passive"))
      (node (ref "Q44") (pin "3") (pinfunction "D_3") (pintype "passive"))
      (node (ref "Q46") (pin "3") (pinfunction "D_3") (pintype "passive"))
      (node (ref "Q48") (pin "3") (pinfunction "D_3") (pintype "passive"))
      (node (ref "Q5") (pin "3") (pinfunction "D_3") (pintype "passive"))
      (node (ref "Q50") (pin "3") (pinfunction "D_3") (pintype "passive"))
      (node (ref "Q52") (pin "3") (pinfunction "D_3") (pintype "passive"))
      (node (ref "Q54") (pin "3") (pinfunction "D_3") (pintype "passive"))
      (node (ref "Q55") (pin "3") (pinfunction "D_3") (pintype "passive"))
      (node (ref "Q57") (pin "3") (pinfunction "D_3") (pintype "passive"))
      (node (ref "Q59") (pin "3") (pinfunction "D_3") (pintype "passive"))
      (node (ref "Q61") (pin "3") (pinfunction "D_3") (pintype "passive"))
      (node (ref "Q63") (pin "3") (pinfunction "D_3") (pintype "passive"))
      (node (ref "Q65") (pin "3") (pinfunction "D_3") (pintype "passive"))
      (node (ref "Q68") (pin "3") (pinfunction "D_3") (pintype "passive"))
      (node (ref "Q70") (pin "3") (pinfunction "D_3") (pintype "passive"))
      (node (ref "Q72") (pin "3") (pinfunction "D_3") (pintype "passive"))
      (node (ref "Q73") (pin "3") (pinfunction "D_3") (pintype "passive"))
      (node (ref "Q75") (pin "3") (pinfunction "D_3") (pintype "passive"))
      (node (ref "Q77") (pin "3") (pinfunction "D_3") (pintype "passive"))
      (node (ref "Q8") (pin "3") (pinfunction "D_3") (pintype "passive"))
      (node (ref "U1") (pin "7") (pinfunction "VCC_7") (pintype "passive"))
      (node (ref "U10") (pin "7") (pinfunction "VCC_7") (pintype "passive"))
      (node (ref "U11") (pin "7") (pinfunction "VCC_7") (pintype "passive"))
      (node (ref "U12") (pin "7") (pinfunction "VCC_7") (pintype "passive"))
      (node (ref "U13") (pin "2") (pinfunction "2_2") (pintype "passive"))
      (node (ref "U14") (pin "7") (pinfunction "VCC_7") (pintype "passive"))
      (node (ref "U2") (pin "7") (pinfunction "VCC_7") (pintype "passive"))
      (node (ref "U3") (pin "7") (pinfunction "VCC_7") (pintype "passive"))
      (node (ref "U4") (pin "7") (pinfunction "VCC_7") (pintype "passive"))
      (node (ref "U5") (pin "7") (pinfunction "VCC_7") (pintype "passive"))
      (node (ref "U6") (pin "7") (pinfunction "VCC_7") (pintype "passive"))
      (node (ref "U7") (pin "7") (pinfunction "VCC_7") (pintype "passive"))
      (node (ref "U8") (pin "7") (pinfunction "VCC_7") (pintype "passive"))
      (node (ref "U9") (pin "7") (pinfunction "VCC_7") (pintype "passive"))
    )
    (net (code "276") (name "unconnected-(CN1-Pad4)") (class "Default")
      (node (ref "CN1") (pin "4") (pinfunction "4_4") (pintype "passive"))
    )
    (net (code "277") (name "unconnected-(CN1-Pad5)") (class "Default")
      (node (ref "CN1") (pin "5") (pinfunction "5_5") (pintype "passive"))
    )
    (net (code "278") (name "unconnected-(CN2-Pad4)") (class "Default")
      (node (ref "CN2") (pin "4") (pinfunction "4_4") (pintype "passive"))
    )
    (net (code "279") (name "unconnected-(CN2-Pad5)") (class "Default")
      (node (ref "CN2") (pin "5") (pinfunction "5_5") (pintype "passive"))
    )
    (net (code "280") (name "unconnected-(CN3-Pad4)") (class "Default")
      (node (ref "CN3") (pin "4") (pinfunction "4_4") (pintype "passive"))
    )
    (net (code "281") (name "unconnected-(CN3-Pad5)") (class "Default")
      (node (ref "CN3") (pin "5") (pinfunction "5_5") (pintype "passive"))
    )
    (net (code "282") (name "unconnected-(CN4-Pad4)") (class "Default")
      (node (ref "CN4") (pin "4") (pinfunction "4_4") (pintype "passive"))
    )
    (net (code "283") (name "unconnected-(CN4-Pad5)") (class "Default")
      (node (ref "CN4") (pin "5") (pinfunction "5_5") (pintype "passive"))
    )
    (net (code "284") (name "unconnected-(CN5-Pad4)") (class "Default")
      (node (ref "CN5") (pin "4") (pinfunction "4_4") (pintype "passive"))
    )
    (net (code "285") (name "unconnected-(CN5-Pad5)") (class "Default")
      (node (ref "CN5") (pin "5") (pinfunction "5_5") (pintype "passive"))
    )
    (net (code "286") (name "unconnected-(CN6-Pad4)") (class "Default")
      (node (ref "CN6") (pin "4") (pinfunction "4_4") (pintype "passive"))
    )
    (net (code "287") (name "unconnected-(CN6-Pad5)") (class "Default")
      (node (ref "CN6") (pin "5") (pinfunction "5_5") (pintype "passive"))
    )
    (net (code "288") (name "unconnected-(CN7-Pad4)") (class "Default")
      (node (ref "CN7") (pin "4") (pinfunction "4_4") (pintype "passive"))
    )
    (net (code "289") (name "unconnected-(CN7-Pad5)") (class "Default")
      (node (ref "CN7") (pin "5") (pinfunction "5_5") (pintype "passive"))
    )
    (net (code "290") (name "unconnected-(CN8-Pad4)") (class "Default")
      (node (ref "CN8") (pin "4") (pinfunction "4_4") (pintype "passive"))
    )
    (net (code "291") (name "unconnected-(CN8-Pad5)") (class "Default")
      (node (ref "CN8") (pin "5") (pinfunction "5_5") (pintype "passive"))
    )
    (net (code "292") (name "unconnected-(CN9-Pad4)") (class "Default")
      (node (ref "CN9") (pin "4") (pinfunction "4_4") (pintype "passive"))
    )
    (net (code "293") (name "unconnected-(CN9-Pad5)") (class "Default")
      (node (ref "CN9") (pin "5") (pinfunction "5_5") (pintype "passive"))
    )
    (net (code "294") (name "unconnected-(CN10-Pad4)") (class "Default")
      (node (ref "CN10") (pin "4") (pinfunction "4_4") (pintype "passive"))
    )
    (net (code "295") (name "unconnected-(CN10-Pad5)") (class "Default")
      (node (ref "CN10") (pin "5") (pinfunction "5_5") (pintype "passive"))
    )
    (net (code "296") (name "unconnected-(CN11-Pad4)") (class "Default")
      (node (ref "CN11") (pin "4") (pinfunction "4_4") (pintype "passive"))
    )
    (net (code "297") (name "unconnected-(CN11-Pad5)") (class "Default")
      (node (ref "CN11") (pin "5") (pinfunction "5_5") (pintype "passive"))
    )
    (net (code "298") (name "unconnected-(CN12-Pad4)") (class "Default")
      (node (ref "CN12") (pin "4") (pinfunction "4_4") (pintype "passive"))
    )
    (net (code "299") (name "unconnected-(CN12-Pad5)") (class "Default")
      (node (ref "CN12") (pin "5") (pinfunction "5_5") (pintype "passive"))
    )
    (net (code "300") (name "unconnected-(CN13-Pad4)") (class "Default")
      (node (ref "CN13") (pin "4") (pinfunction "4_4") (pintype "passive"))
    )
    (net (code "301") (name "unconnected-(CN13-Pad5)") (class "Default")
      (node (ref "CN13") (pin "5") (pinfunction "5_5") (pintype "passive"))
    )
    (net (code "302") (name "unconnected-(FPC2-Pad40)") (class "Default")
      (node (ref "FPC2") (pin "40") (pinfunction "40_40") (pintype "passive"))
    )
    (net (code "303") (name "unconnected-(FPC2-Pad41)") (class "Default")
      (node (ref "FPC2") (pin "41") (pinfunction "41_41") (pintype "passive"))
    )
    (net (code "304") (name "unconnected-(FPC2-Pad42)") (class "Default")
      (node (ref "FPC2") (pin "42") (pinfunction "42_42") (pintype "passive"))
    )
    (net (code "305") (name "unconnected-(U13-Pad3)") (class "Default")
      (node (ref "U13") (pin "3") (pinfunction "3_3") (pintype "passive"))
    )
    (net (code "306") (name "unconnected-(U13-Pad4)") (class "Default")
      (node (ref "U13") (pin "4") (pinfunction "4_4") (pintype "passive"))
    )
  )
)
